# module.net
KiCad netlist of a schematic drawn in Altium Designer
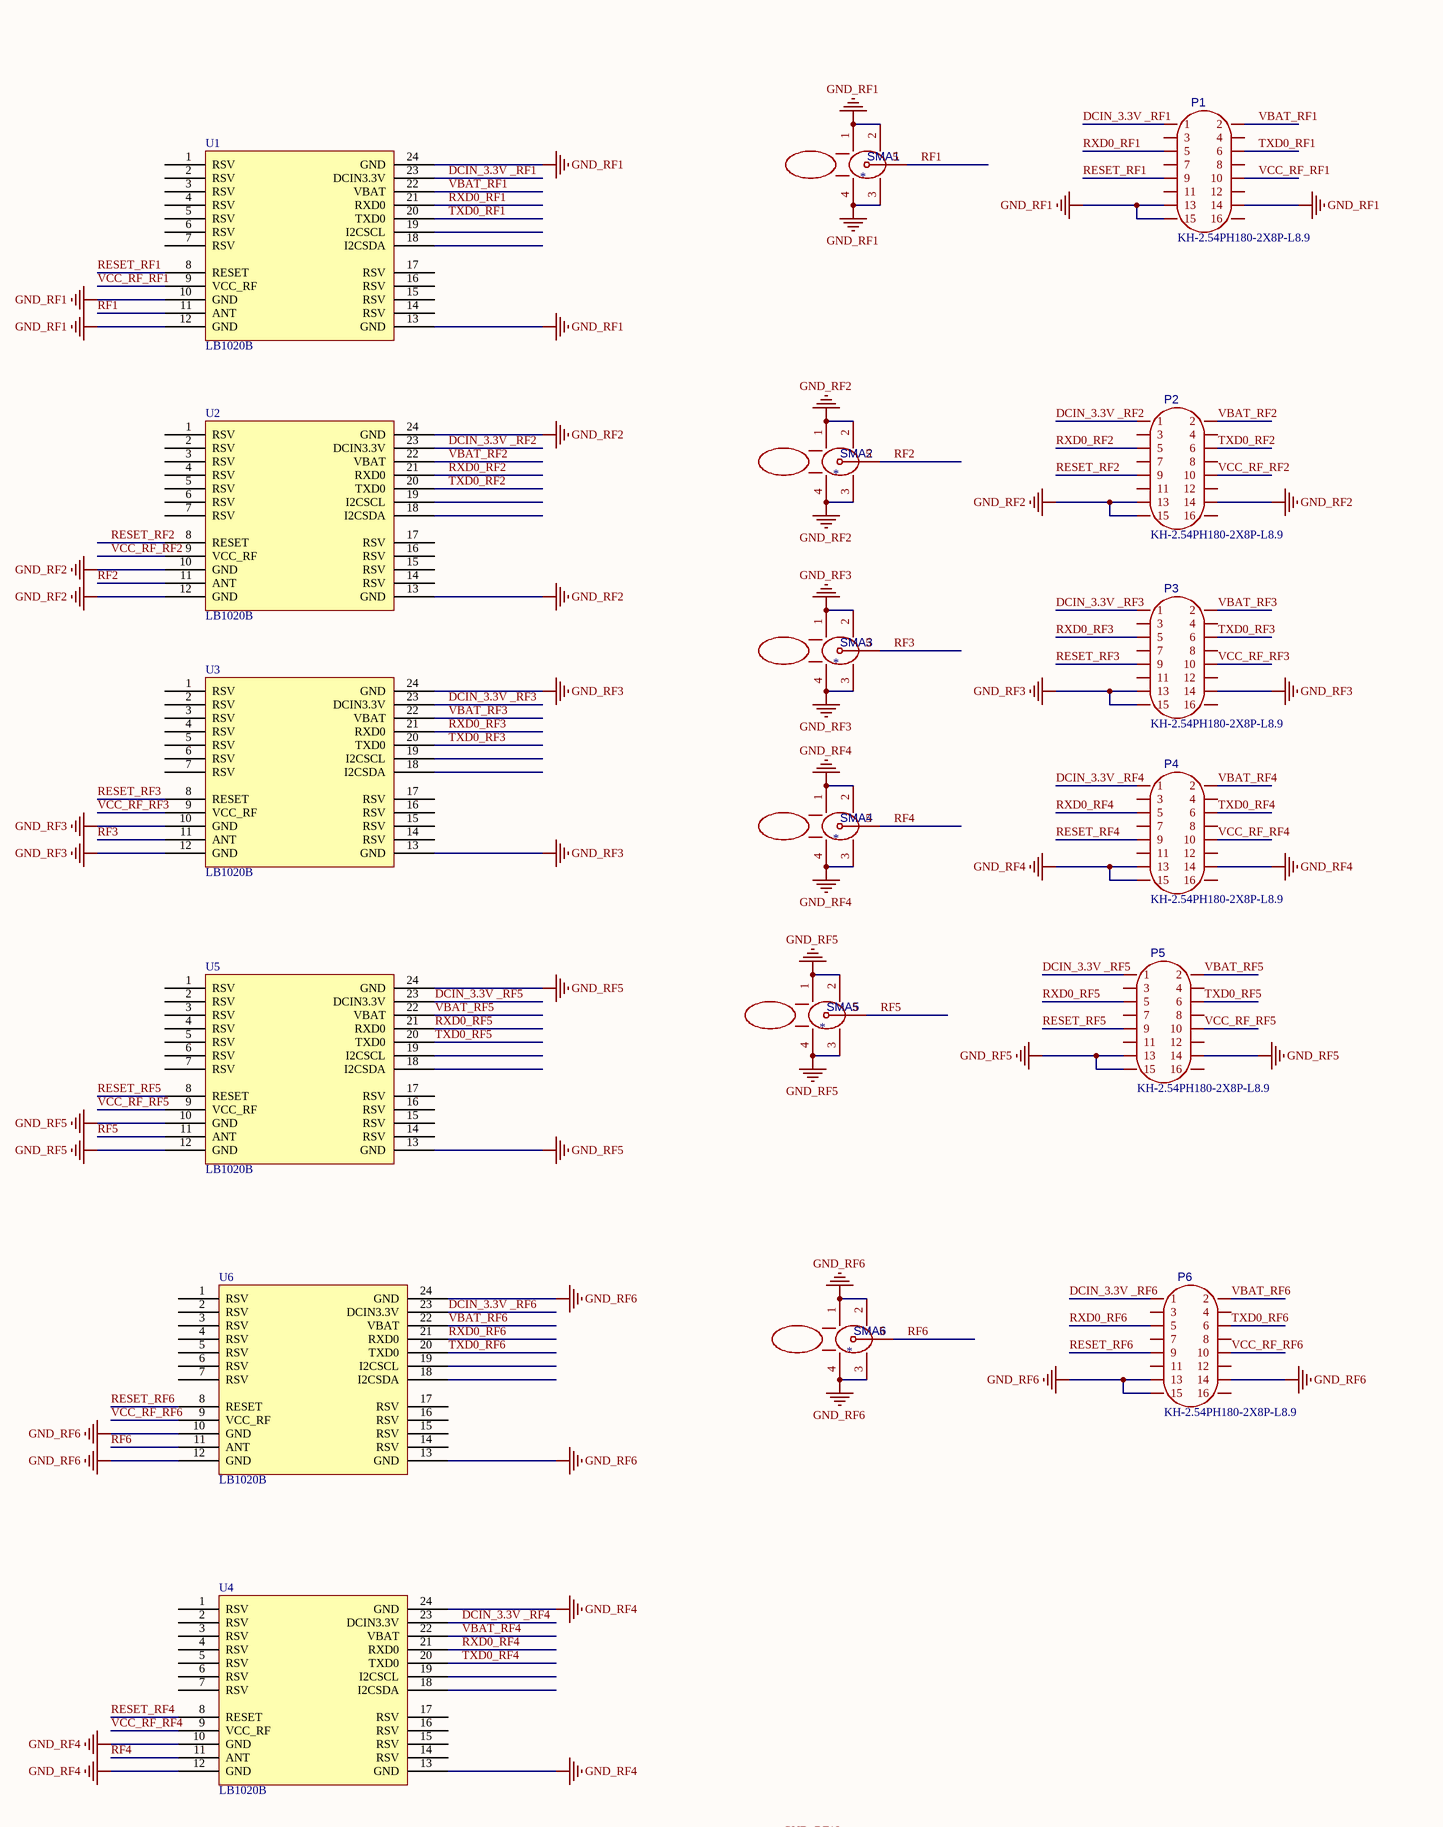
[diagram p0: module.SchDoc, top left]
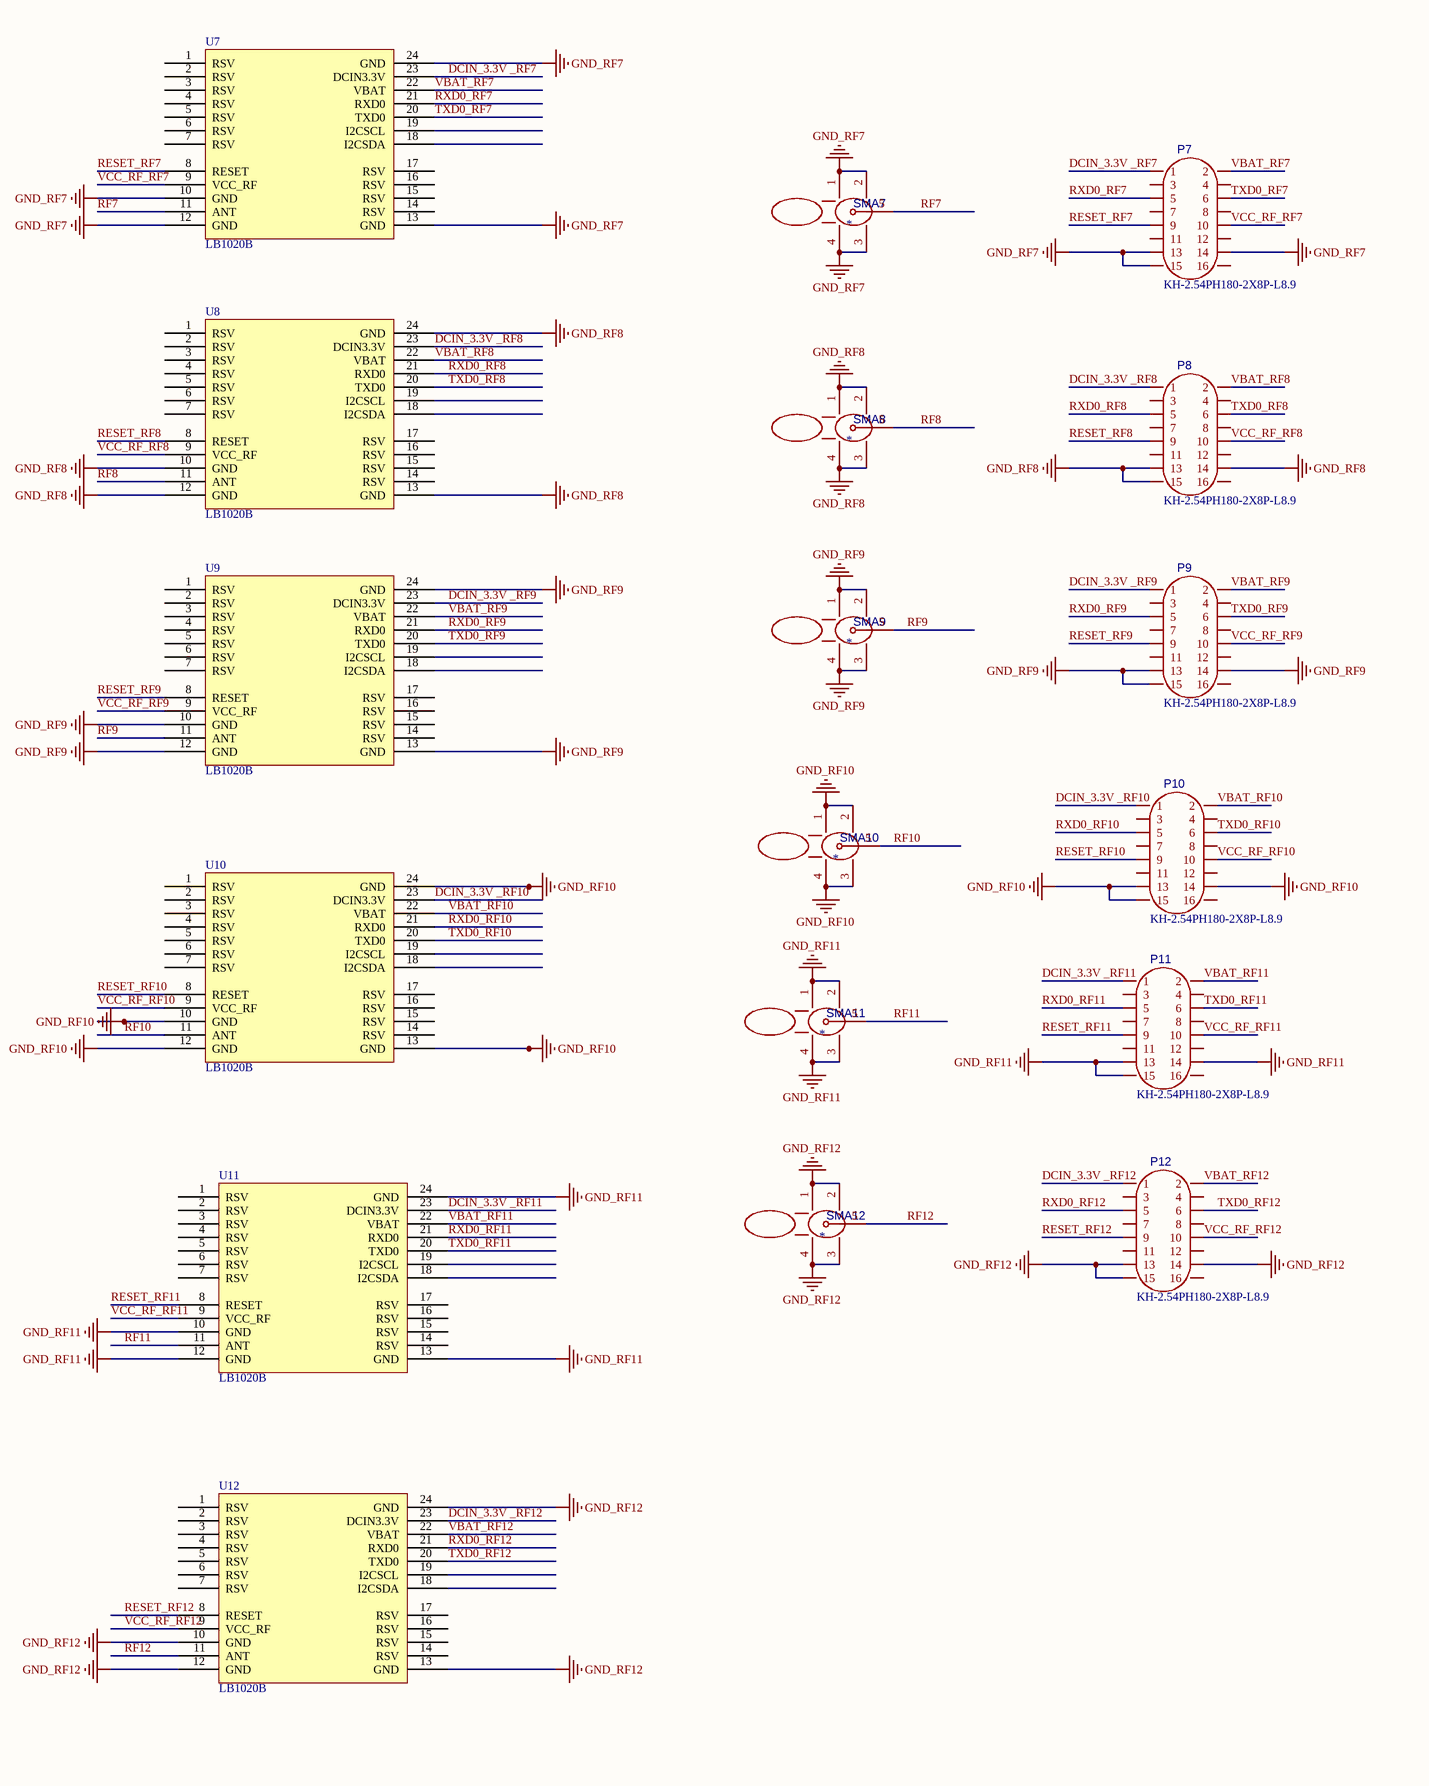
[diagram p1: module.SchDoc, top right]
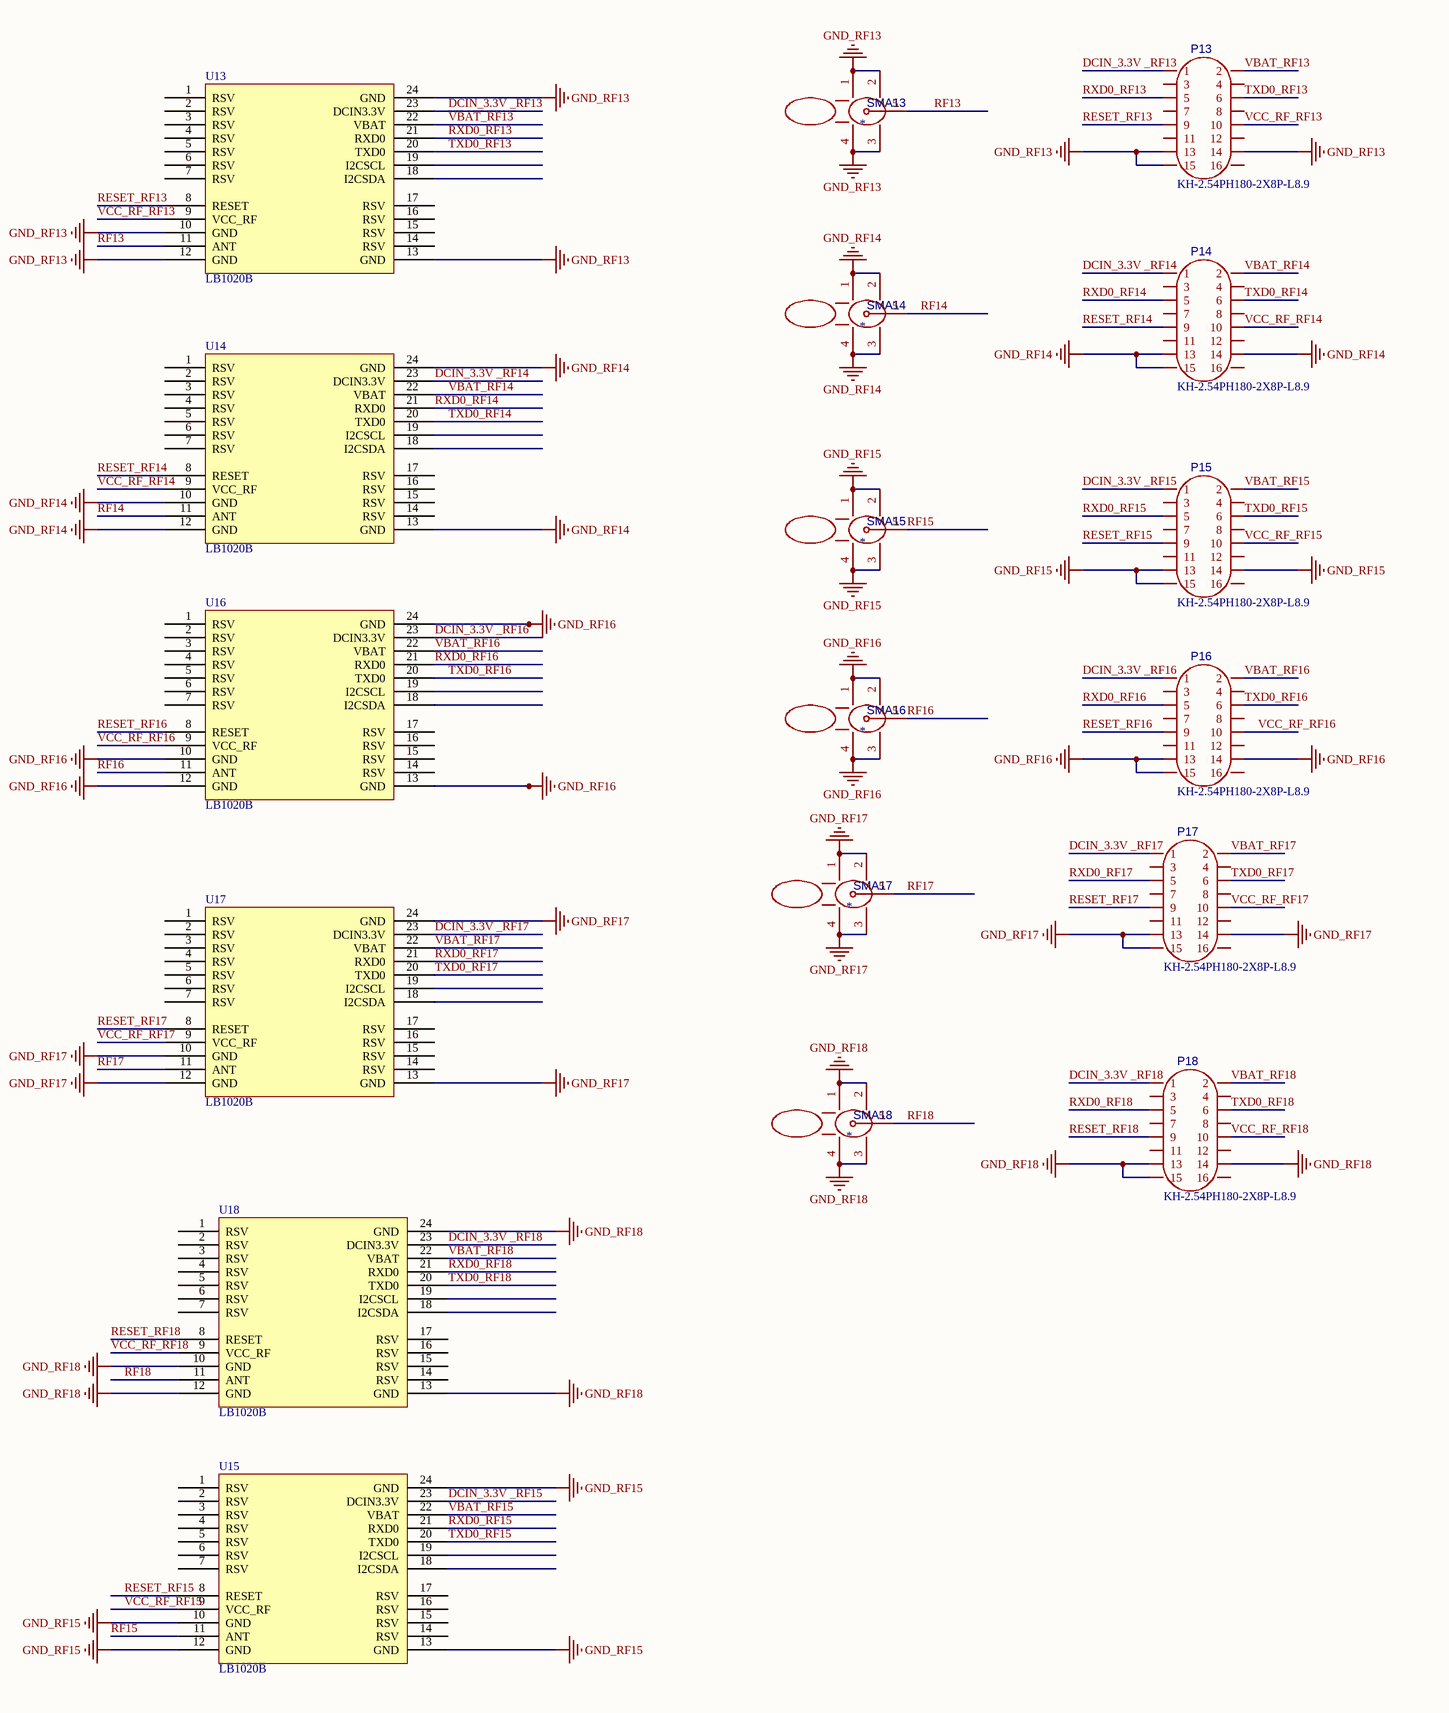
[diagram p2: module.SchDoc, bottom left]
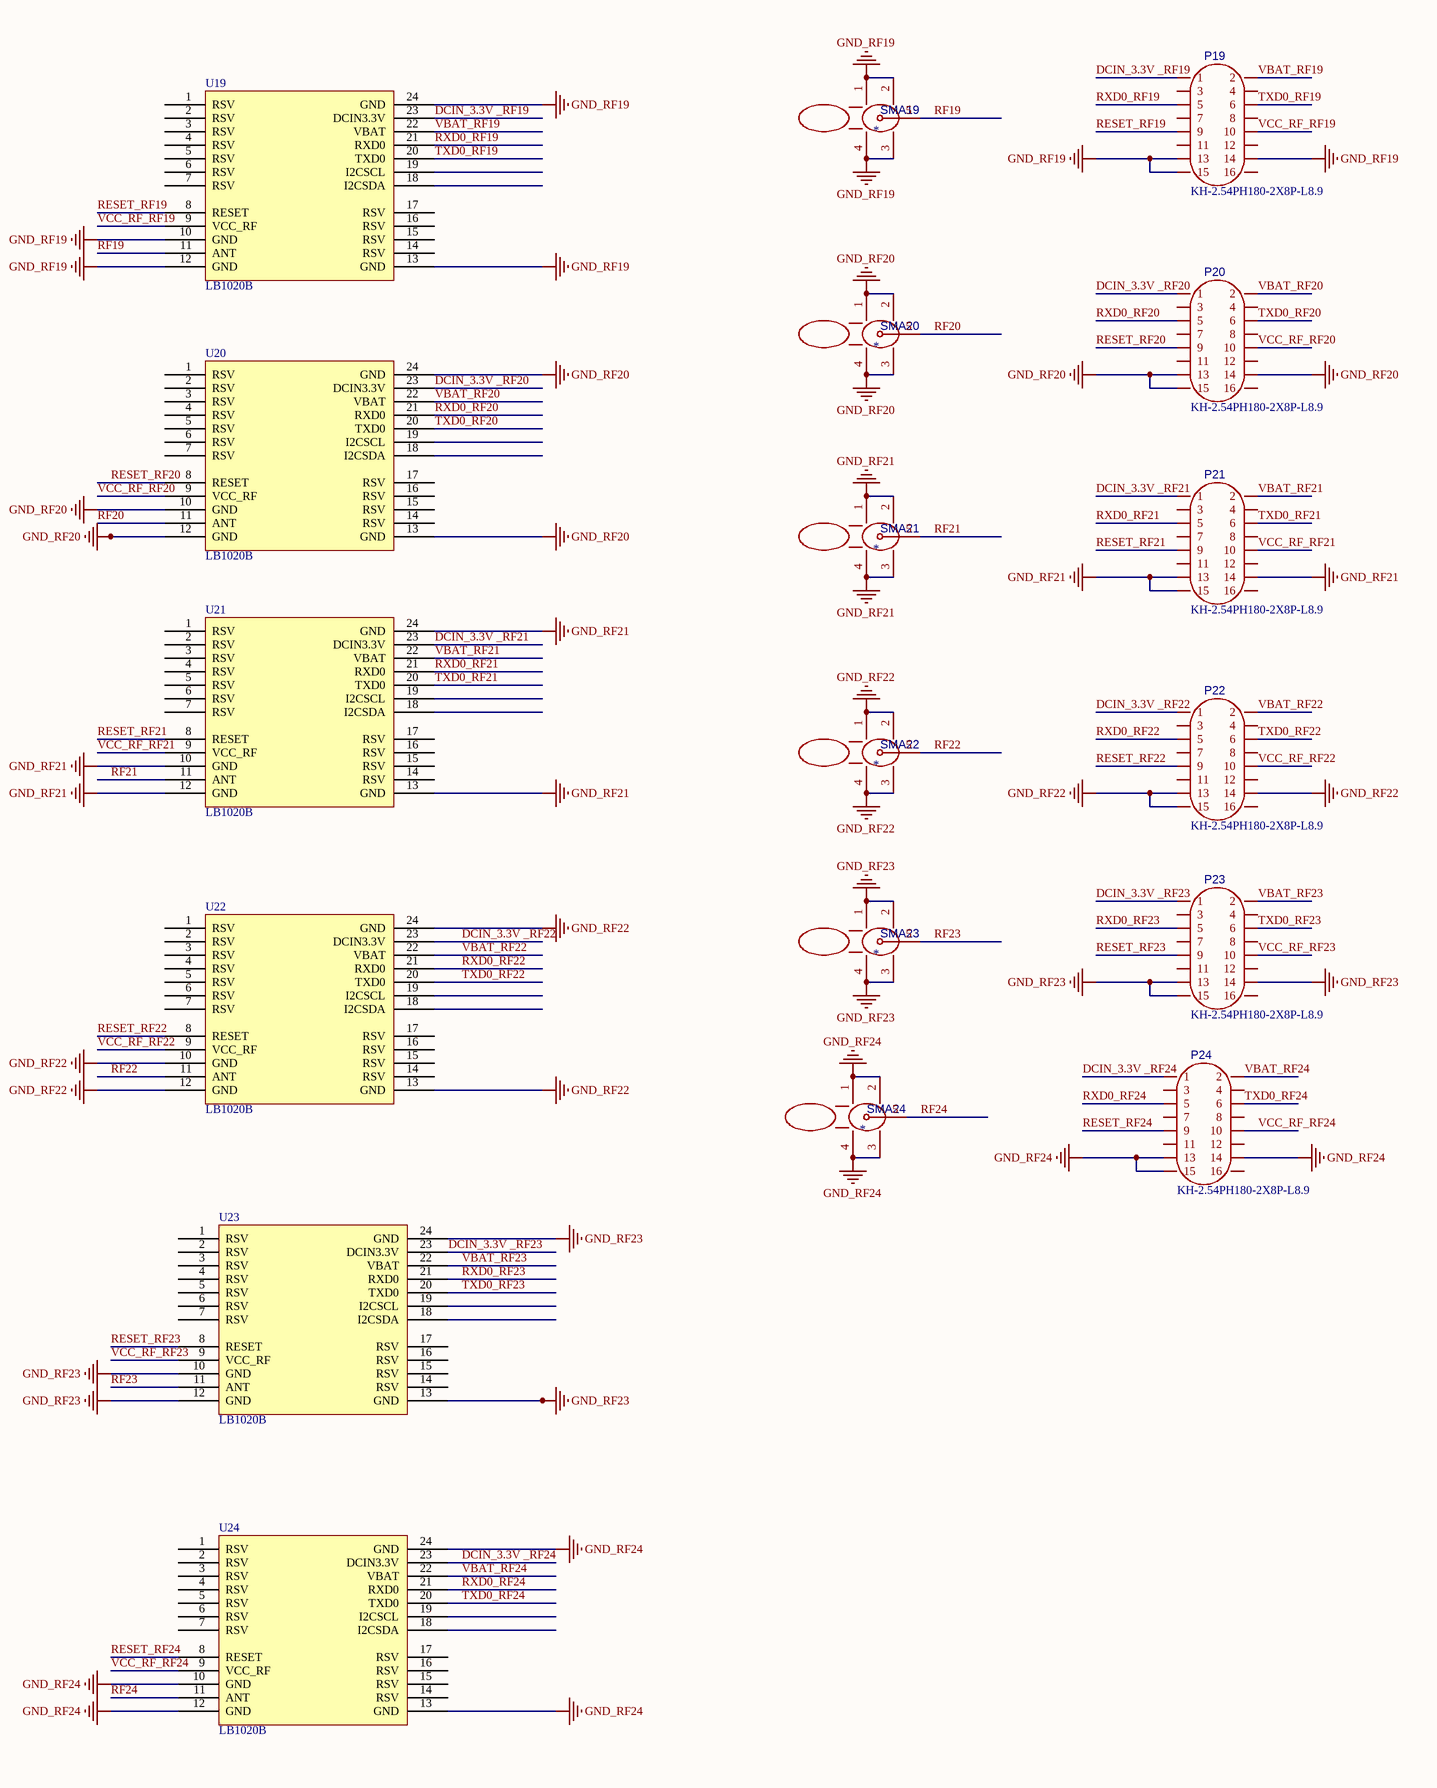
[diagram p3: module.SchDoc, bottom right]

(export (version "E")
  (design (tool "Eeschema 10.0.6"))
  (components
    (comp (ref "P1")
      (value "KH-2.54PH180-2X8P-L8.9")
      (footprint "IDC-TH_16P-P2.54_C3406:IDC-TH_16P-P2.54_C3406")
      (libsource (lib "altium-import") (part "root_0_HDR-IDC-2.54-2X8P_"))
    )
    (comp (ref "P2")
      (value "KH-2.54PH180-2X8P-L8.9")
      (footprint "IDC-TH_16P-P2.54_C3406:IDC-TH_16P-P2.54_C3406")
      (libsource (lib "altium-import") (part "root_0_HDR-IDC-2.54-2X8P_"))
    )
    (comp (ref "P3")
      (value "KH-2.54PH180-2X8P-L8.9")
      (footprint "IDC-TH_16P-P2.54_C3406:IDC-TH_16P-P2.54_C3406")
      (libsource (lib "altium-import") (part "root_0_HDR-IDC-2.54-2X8P_"))
    )
    (comp (ref "P4")
      (value "KH-2.54PH180-2X8P-L8.9")
      (footprint "IDC-TH_16P-P2.54_C3406:IDC-TH_16P-P2.54_C3406")
      (libsource (lib "altium-import") (part "root_0_HDR-IDC-2.54-2X8P_"))
    )
    (comp (ref "P5")
      (value "KH-2.54PH180-2X8P-L8.9")
      (footprint "IDC-TH_16P-P2.54_C3406:IDC-TH_16P-P2.54_C3406")
      (libsource (lib "altium-import") (part "root_0_HDR-IDC-2.54-2X8P_"))
    )
    (comp (ref "P6")
      (value "KH-2.54PH180-2X8P-L8.9")
      (footprint "IDC-TH_16P-P2.54_C3406:IDC-TH_16P-P2.54_C3406")
      (libsource (lib "altium-import") (part "root_0_HDR-IDC-2.54-2X8P_"))
    )
    (comp (ref "P7")
      (value "KH-2.54PH180-2X8P-L8.9")
      (footprint "IDC-TH_16P-P2.54_C3406:IDC-TH_16P-P2.54_C3406")
      (libsource (lib "altium-import") (part "root_0_HDR-IDC-2.54-2X8P_"))
    )
    (comp (ref "P8")
      (value "KH-2.54PH180-2X8P-L8.9")
      (footprint "IDC-TH_16P-P2.54_C3406:IDC-TH_16P-P2.54_C3406")
      (libsource (lib "altium-import") (part "root_0_HDR-IDC-2.54-2X8P_"))
    )
    (comp (ref "P9")
      (value "KH-2.54PH180-2X8P-L8.9")
      (footprint "IDC-TH_16P-P2.54_C3406:IDC-TH_16P-P2.54_C3406")
      (libsource (lib "altium-import") (part "root_0_HDR-IDC-2.54-2X8P_"))
    )
    (comp (ref "P10")
      (value "KH-2.54PH180-2X8P-L8.9")
      (footprint "IDC-TH_16P-P2.54_C3406:IDC-TH_16P-P2.54_C3406")
      (libsource (lib "altium-import") (part "root_0_HDR-IDC-2.54-2X8P_"))
    )
    (comp (ref "P11")
      (value "KH-2.54PH180-2X8P-L8.9")
      (footprint "IDC-TH_16P-P2.54_C3406:IDC-TH_16P-P2.54_C3406")
      (libsource (lib "altium-import") (part "root_0_HDR-IDC-2.54-2X8P_"))
    )
    (comp (ref "P12")
      (value "KH-2.54PH180-2X8P-L8.9")
      (footprint "IDC-TH_16P-P2.54_C3406:IDC-TH_16P-P2.54_C3406")
      (libsource (lib "altium-import") (part "root_0_HDR-IDC-2.54-2X8P_"))
    )
    (comp (ref "P13")
      (value "KH-2.54PH180-2X8P-L8.9")
      (footprint "IDC-TH_16P-P2.54_C3406:IDC-TH_16P-P2.54_C3406")
      (libsource (lib "altium-import") (part "root_0_HDR-IDC-2.54-2X8P_"))
    )
    (comp (ref "P14")
      (value "KH-2.54PH180-2X8P-L8.9")
      (footprint "IDC-TH_16P-P2.54_C3406:IDC-TH_16P-P2.54_C3406")
      (libsource (lib "altium-import") (part "root_0_HDR-IDC-2.54-2X8P_"))
    )
    (comp (ref "P15")
      (value "KH-2.54PH180-2X8P-L8.9")
      (footprint "IDC-TH_16P-P2.54_C3406:IDC-TH_16P-P2.54_C3406")
      (libsource (lib "altium-import") (part "root_0_HDR-IDC-2.54-2X8P_"))
    )
    (comp (ref "P16")
      (value "KH-2.54PH180-2X8P-L8.9")
      (footprint "IDC-TH_16P-P2.54_C3406:IDC-TH_16P-P2.54_C3406")
      (libsource (lib "altium-import") (part "root_0_HDR-IDC-2.54-2X8P_"))
    )
    (comp (ref "P17")
      (value "KH-2.54PH180-2X8P-L8.9")
      (footprint "IDC-TH_16P-P2.54_C3406:IDC-TH_16P-P2.54_C3406")
      (libsource (lib "altium-import") (part "root_0_HDR-IDC-2.54-2X8P_"))
    )
    (comp (ref "P18")
      (value "KH-2.54PH180-2X8P-L8.9")
      (footprint "IDC-TH_16P-P2.54_C3406:IDC-TH_16P-P2.54_C3406")
      (libsource (lib "altium-import") (part "root_0_HDR-IDC-2.54-2X8P_"))
    )
    (comp (ref "P19")
      (value "KH-2.54PH180-2X8P-L8.9")
      (footprint "IDC-TH_16P-P2.54_C3406:IDC-TH_16P-P2.54_C3406")
      (libsource (lib "altium-import") (part "root_0_HDR-IDC-2.54-2X8P_"))
    )
    (comp (ref "P20")
      (value "KH-2.54PH180-2X8P-L8.9")
      (footprint "IDC-TH_16P-P2.54_C3406:IDC-TH_16P-P2.54_C3406")
      (libsource (lib "altium-import") (part "root_0_HDR-IDC-2.54-2X8P_"))
    )
    (comp (ref "P21")
      (value "KH-2.54PH180-2X8P-L8.9")
      (footprint "IDC-TH_16P-P2.54_C3406:IDC-TH_16P-P2.54_C3406")
      (libsource (lib "altium-import") (part "root_0_HDR-IDC-2.54-2X8P_"))
    )
    (comp (ref "P22")
      (value "KH-2.54PH180-2X8P-L8.9")
      (footprint "IDC-TH_16P-P2.54_C3406:IDC-TH_16P-P2.54_C3406")
      (libsource (lib "altium-import") (part "root_0_HDR-IDC-2.54-2X8P_"))
    )
    (comp (ref "P23")
      (value "KH-2.54PH180-2X8P-L8.9")
      (footprint "IDC-TH_16P-P2.54_C3406:IDC-TH_16P-P2.54_C3406")
      (libsource (lib "altium-import") (part "root_0_HDR-IDC-2.54-2X8P_"))
    )
    (comp (ref "P24")
      (value "KH-2.54PH180-2X8P-L8.9")
      (footprint "IDC-TH_16P-P2.54_C3406:IDC-TH_16P-P2.54_C3406")
      (libsource (lib "altium-import") (part "root_0_HDR-IDC-2.54-2X8P_"))
    )
    (comp (ref "SMA1")
      (value "*")
      (footprint "SMA-TH_HL-SMA-KHD4:SMA-TH_HL-SMA-KHD4")
      (libsource (lib "altium-import") (part "root_0_HL-SMA-KHD4_"))
    )
    (comp (ref "SMA2")
      (value "*")
      (footprint "SMA-TH_HL-SMA-KHD4:SMA-TH_HL-SMA-KHD4")
      (libsource (lib "altium-import") (part "root_0_HL-SMA-KHD4_"))
    )
    (comp (ref "SMA3")
      (value "*")
      (footprint "SMA-TH_HL-SMA-KHD4:SMA-TH_HL-SMA-KHD4")
      (libsource (lib "altium-import") (part "root_0_HL-SMA-KHD4_"))
    )
    (comp (ref "SMA4")
      (value "*")
      (footprint "SMA-TH_HL-SMA-KHD4:SMA-TH_HL-SMA-KHD4")
      (libsource (lib "altium-import") (part "root_0_HL-SMA-KHD4_"))
    )
    (comp (ref "SMA5")
      (value "*")
      (footprint "SMA-TH_HL-SMA-KHD4:SMA-TH_HL-SMA-KHD4")
      (libsource (lib "altium-import") (part "root_0_HL-SMA-KHD4_"))
    )
    (comp (ref "SMA6")
      (value "*")
      (footprint "SMA-TH_HL-SMA-KHD4:SMA-TH_HL-SMA-KHD4")
      (libsource (lib "altium-import") (part "root_0_HL-SMA-KHD4_"))
    )
    (comp (ref "SMA7")
      (value "*")
      (footprint "SMA-TH_HL-SMA-KHD4:SMA-TH_HL-SMA-KHD4")
      (libsource (lib "altium-import") (part "root_0_HL-SMA-KHD4_"))
    )
    (comp (ref "SMA8")
      (value "*")
      (footprint "SMA-TH_HL-SMA-KHD4:SMA-TH_HL-SMA-KHD4")
      (libsource (lib "altium-import") (part "root_0_HL-SMA-KHD4_"))
    )
    (comp (ref "SMA9")
      (value "*")
      (footprint "SMA-TH_HL-SMA-KHD4:SMA-TH_HL-SMA-KHD4")
      (libsource (lib "altium-import") (part "root_0_HL-SMA-KHD4_"))
    )
    (comp (ref "SMA10")
      (value "*")
      (footprint "SMA-TH_HL-SMA-KHD4:SMA-TH_HL-SMA-KHD4")
      (libsource (lib "altium-import") (part "root_0_HL-SMA-KHD4_"))
    )
    (comp (ref "SMA11")
      (value "*")
      (footprint "SMA-TH_HL-SMA-KHD4:SMA-TH_HL-SMA-KHD4")
      (libsource (lib "altium-import") (part "root_0_HL-SMA-KHD4_"))
    )
    (comp (ref "SMA12")
      (value "*")
      (footprint "SMA-TH_HL-SMA-KHD4:SMA-TH_HL-SMA-KHD4")
      (libsource (lib "altium-import") (part "root_0_HL-SMA-KHD4_"))
    )
    (comp (ref "SMA13")
      (value "*")
      (footprint "SMA-TH_HL-SMA-KHD4:SMA-TH_HL-SMA-KHD4")
      (libsource (lib "altium-import") (part "root_0_HL-SMA-KHD4_"))
    )
    (comp (ref "SMA14")
      (value "*")
      (footprint "SMA-TH_HL-SMA-KHD4:SMA-TH_HL-SMA-KHD4")
      (libsource (lib "altium-import") (part "root_0_HL-SMA-KHD4_"))
    )
    (comp (ref "SMA15")
      (value "*")
      (footprint "SMA-TH_HL-SMA-KHD4:SMA-TH_HL-SMA-KHD4")
      (libsource (lib "altium-import") (part "root_0_HL-SMA-KHD4_"))
    )
    (comp (ref "SMA16")
      (value "*")
      (footprint "SMA-TH_HL-SMA-KHD4:SMA-TH_HL-SMA-KHD4")
      (libsource (lib "altium-import") (part "root_0_HL-SMA-KHD4_"))
    )
    (comp (ref "SMA17")
      (value "*")
      (footprint "SMA-TH_HL-SMA-KHD4:SMA-TH_HL-SMA-KHD4")
      (libsource (lib "altium-import") (part "root_0_HL-SMA-KHD4_"))
    )
    (comp (ref "SMA18")
      (value "*")
      (footprint "SMA-TH_HL-SMA-KHD4:SMA-TH_HL-SMA-KHD4")
      (libsource (lib "altium-import") (part "root_0_HL-SMA-KHD4_"))
    )
    (comp (ref "SMA19")
      (value "*")
      (footprint "SMA-TH_HL-SMA-KHD4:SMA-TH_HL-SMA-KHD4")
      (libsource (lib "altium-import") (part "root_0_HL-SMA-KHD4_"))
    )
    (comp (ref "SMA20")
      (value "*")
      (footprint "SMA-TH_HL-SMA-KHD4:SMA-TH_HL-SMA-KHD4")
      (libsource (lib "altium-import") (part "root_0_HL-SMA-KHD4_"))
    )
    (comp (ref "SMA21")
      (value "*")
      (footprint "SMA-TH_HL-SMA-KHD4:SMA-TH_HL-SMA-KHD4")
      (libsource (lib "altium-import") (part "root_0_HL-SMA-KHD4_"))
    )
    (comp (ref "SMA22")
      (value "*")
      (footprint "SMA-TH_HL-SMA-KHD4:SMA-TH_HL-SMA-KHD4")
      (libsource (lib "altium-import") (part "root_0_HL-SMA-KHD4_"))
    )
    (comp (ref "SMA23")
      (value "*")
      (footprint "SMA-TH_HL-SMA-KHD4:SMA-TH_HL-SMA-KHD4")
      (libsource (lib "altium-import") (part "root_0_HL-SMA-KHD4_"))
    )
    (comp (ref "SMA24")
      (value "*")
      (footprint "SMA-TH_HL-SMA-KHD4:SMA-TH_HL-SMA-KHD4")
      (libsource (lib "altium-import") (part "root_0_HL-SMA-KHD4_"))
    )
    (comp (ref "U1")
      (value "LB1020B")
      (footprint "LB1020B")
      (libsource (lib "Schlib_20110825") (part "LB1020B"))
    )
    (comp (ref "U2")
      (value "LB1020B")
      (footprint "LB1020B")
      (libsource (lib "Schlib_20110825") (part "LB1020B"))
    )
    (comp (ref "U3")
      (value "LB1020B")
      (footprint "LB1020B")
      (libsource (lib "Schlib_20110825") (part "LB1020B"))
    )
    (comp (ref "U4")
      (value "LB1020B")
      (footprint "LB1020B")
      (libsource (lib "Schlib_20110825") (part "LB1020B"))
    )
    (comp (ref "U5")
      (value "LB1020B")
      (footprint "LB1020B")
      (libsource (lib "Schlib_20110825") (part "LB1020B"))
    )
    (comp (ref "U6")
      (value "LB1020B")
      (footprint "LB1020B")
      (libsource (lib "Schlib_20110825") (part "LB1020B"))
    )
    (comp (ref "U7")
      (value "LB1020B")
      (footprint "LB1020B")
      (libsource (lib "Schlib_20110825") (part "LB1020B"))
    )
    (comp (ref "U8")
      (value "LB1020B")
      (footprint "LB1020B")
      (libsource (lib "Schlib_20110825") (part "LB1020B"))
    )
    (comp (ref "U9")
      (value "LB1020B")
      (footprint "LB1020B")
      (libsource (lib "Schlib_20110825") (part "LB1020B"))
    )
    (comp (ref "U10")
      (value "LB1020B")
      (footprint "LB1020B")
      (libsource (lib "Schlib_20110825") (part "LB1020B"))
    )
    (comp (ref "U11")
      (value "LB1020B")
      (footprint "LB1020B")
      (libsource (lib "Schlib_20110825") (part "LB1020B"))
    )
    (comp (ref "U12")
      (value "LB1020B")
      (footprint "LB1020B")
      (libsource (lib "Schlib_20110825") (part "LB1020B"))
    )
    (comp (ref "U13")
      (value "LB1020B")
      (footprint "LB1020B")
      (libsource (lib "Schlib_20110825") (part "LB1020B"))
    )
    (comp (ref "U14")
      (value "LB1020B")
      (footprint "LB1020B")
      (libsource (lib "Schlib_20110825") (part "LB1020B"))
    )
    (comp (ref "U15")
      (value "LB1020B")
      (footprint "LB1020B")
      (libsource (lib "Schlib_20110825") (part "LB1020B"))
    )
    (comp (ref "U16")
      (value "LB1020B")
      (footprint "LB1020B")
      (libsource (lib "Schlib_20110825") (part "LB1020B"))
    )
    (comp (ref "U17")
      (value "LB1020B")
      (footprint "LB1020B")
      (libsource (lib "Schlib_20110825") (part "LB1020B"))
    )
    (comp (ref "U18")
      (value "LB1020B")
      (footprint "LB1020B")
      (libsource (lib "Schlib_20110825") (part "LB1020B"))
    )
    (comp (ref "U19")
      (value "LB1020B")
      (footprint "LB1020B")
      (libsource (lib "Schlib_20110825") (part "LB1020B"))
    )
    (comp (ref "U20")
      (value "LB1020B")
      (footprint "LB1020B")
      (libsource (lib "Schlib_20110825") (part "LB1020B"))
    )
    (comp (ref "U21")
      (value "LB1020B")
      (footprint "LB1020B")
      (libsource (lib "Schlib_20110825") (part "LB1020B"))
    )
    (comp (ref "U22")
      (value "LB1020B")
      (footprint "LB1020B")
      (libsource (lib "Schlib_20110825") (part "LB1020B"))
    )
    (comp (ref "U23")
      (value "LB1020B")
      (footprint "LB1020B")
      (libsource (lib "Schlib_20110825") (part "LB1020B"))
    )
    (comp (ref "U24")
      (value "LB1020B")
      (footprint "LB1020B")
      (libsource (lib "Schlib_20110825") (part "LB1020B"))
    )
  )
  (nets
    (net (code "1") (name "/DCIN_3.3V _RF1") (class "Default")
      (node (ref "P1") (pin "1") (pinfunction "1_1") (pintype "passive"))
      (node (ref "U1") (pin "23") (pinfunction "DCIN3.3V_23") (pintype "passive"))
    )
    (net (code "2") (name "/DCIN_3.3V _RF2") (class "Default")
      (node (ref "P2") (pin "1") (pinfunction "1_1") (pintype "passive"))
      (node (ref "U2") (pin "23") (pinfunction "DCIN3.3V_23") (pintype "passive"))
    )
    (net (code "3") (name "/DCIN_3.3V _RF3") (class "Default")
      (node (ref "P3") (pin "1") (pinfunction "1_1") (pintype "passive"))
      (node (ref "U3") (pin "23") (pinfunction "DCIN3.3V_23") (pintype "passive"))
    )
    (net (code "4") (name "/DCIN_3.3V _RF4") (class "Default")
      (node (ref "P4") (pin "1") (pinfunction "1_1") (pintype "passive"))
      (node (ref "U4") (pin "23") (pinfunction "DCIN3.3V_23") (pintype "passive"))
    )
    (net (code "5") (name "/DCIN_3.3V _RF5") (class "Default")
      (node (ref "P5") (pin "1") (pinfunction "1_1") (pintype "passive"))
      (node (ref "U5") (pin "23") (pinfunction "DCIN3.3V_23") (pintype "passive"))
    )
    (net (code "6") (name "/DCIN_3.3V _RF6") (class "Default")
      (node (ref "P6") (pin "1") (pinfunction "1_1") (pintype "passive"))
      (node (ref "U6") (pin "23") (pinfunction "DCIN3.3V_23") (pintype "passive"))
    )
    (net (code "7") (name "/DCIN_3.3V _RF7") (class "Default")
      (node (ref "P7") (pin "1") (pinfunction "1_1") (pintype "passive"))
      (node (ref "U7") (pin "23") (pinfunction "DCIN3.3V_23") (pintype "passive"))
    )
    (net (code "8") (name "/DCIN_3.3V _RF8") (class "Default")
      (node (ref "P8") (pin "1") (pinfunction "1_1") (pintype "passive"))
      (node (ref "U8") (pin "23") (pinfunction "DCIN3.3V_23") (pintype "passive"))
    )
    (net (code "9") (name "/DCIN_3.3V _RF9") (class "Default")
      (node (ref "P9") (pin "1") (pinfunction "1_1") (pintype "passive"))
      (node (ref "U9") (pin "23") (pinfunction "DCIN3.3V_23") (pintype "passive"))
    )
    (net (code "10") (name "/DCIN_3.3V _RF10") (class "Default")
      (node (ref "P10") (pin "1") (pinfunction "1_1") (pintype "passive"))
      (node (ref "U10") (pin "23") (pinfunction "DCIN3.3V_23") (pintype "passive"))
    )
    (net (code "11") (name "/DCIN_3.3V _RF11") (class "Default")
      (node (ref "P11") (pin "1") (pinfunction "1_1") (pintype "passive"))
      (node (ref "U11") (pin "23") (pinfunction "DCIN3.3V_23") (pintype "passive"))
    )
    (net (code "12") (name "/DCIN_3.3V _RF12") (class "Default")
      (node (ref "P12") (pin "1") (pinfunction "1_1") (pintype "passive"))
      (node (ref "U12") (pin "23") (pinfunction "DCIN3.3V_23") (pintype "passive"))
    )
    (net (code "13") (name "/DCIN_3.3V _RF13") (class "Default")
      (node (ref "P13") (pin "1") (pinfunction "1_1") (pintype "passive"))
      (node (ref "U13") (pin "23") (pinfunction "DCIN3.3V_23") (pintype "passive"))
    )
    (net (code "14") (name "/DCIN_3.3V _RF14") (class "Default")
      (node (ref "P14") (pin "1") (pinfunction "1_1") (pintype "passive"))
      (node (ref "U14") (pin "23") (pinfunction "DCIN3.3V_23") (pintype "passive"))
    )
    (net (code "15") (name "/DCIN_3.3V _RF15") (class "Default")
      (node (ref "P15") (pin "1") (pinfunction "1_1") (pintype "passive"))
      (node (ref "U15") (pin "23") (pinfunction "DCIN3.3V_23") (pintype "passive"))
    )
    (net (code "16") (name "/DCIN_3.3V _RF16") (class "Default")
      (node (ref "P16") (pin "1") (pinfunction "1_1") (pintype "passive"))
      (node (ref "U16") (pin "23") (pinfunction "DCIN3.3V_23") (pintype "passive"))
    )
    (net (code "17") (name "/DCIN_3.3V _RF17") (class "Default")
      (node (ref "P17") (pin "1") (pinfunction "1_1") (pintype "passive"))
      (node (ref "U17") (pin "23") (pinfunction "DCIN3.3V_23") (pintype "passive"))
    )
    (net (code "18") (name "/DCIN_3.3V _RF18") (class "Default")
      (node (ref "P18") (pin "1") (pinfunction "1_1") (pintype "passive"))
      (node (ref "U18") (pin "23") (pinfunction "DCIN3.3V_23") (pintype "passive"))
    )
    (net (code "19") (name "/DCIN_3.3V _RF19") (class "Default")
      (node (ref "P19") (pin "1") (pinfunction "1_1") (pintype "passive"))
      (node (ref "U19") (pin "23") (pinfunction "DCIN3.3V_23") (pintype "passive"))
    )
    (net (code "20") (name "/DCIN_3.3V _RF20") (class "Default")
      (node (ref "P20") (pin "1") (pinfunction "1_1") (pintype "passive"))
      (node (ref "U20") (pin "23") (pinfunction "DCIN3.3V_23") (pintype "passive"))
    )
    (net (code "21") (name "/DCIN_3.3V _RF21") (class "Default")
      (node (ref "P21") (pin "1") (pinfunction "1_1") (pintype "passive"))
      (node (ref "U21") (pin "23") (pinfunction "DCIN3.3V_23") (pintype "passive"))
    )
    (net (code "22") (name "/DCIN_3.3V _RF22") (class "Default")
      (node (ref "P22") (pin "1") (pinfunction "1_1") (pintype "passive"))
      (node (ref "U22") (pin "23") (pinfunction "DCIN3.3V_23") (pintype "passive"))
    )
    (net (code "23") (name "/DCIN_3.3V _RF23") (class "Default")
      (node (ref "P23") (pin "1") (pinfunction "1_1") (pintype "passive"))
      (node (ref "U23") (pin "23") (pinfunction "DCIN3.3V_23") (pintype "passive"))
    )
    (net (code "24") (name "/DCIN_3.3V _RF24") (class "Default")
      (node (ref "P24") (pin "1") (pinfunction "1_1") (pintype "passive"))
      (node (ref "U24") (pin "23") (pinfunction "DCIN3.3V_23") (pintype "passive"))
    )
    (net (code "25") (name "/RESET_RF1") (class "Default")
      (node (ref "P1") (pin "9") (pinfunction "9_9") (pintype "passive"))
      (node (ref "U1") (pin "8") (pinfunction "RESET_8") (pintype "passive"))
    )
    (net (code "26") (name "/RESET_RF2") (class "Default")
      (node (ref "P2") (pin "9") (pinfunction "9_9") (pintype "passive"))
      (node (ref "U2") (pin "8") (pinfunction "RESET_8") (pintype "passive"))
    )
    (net (code "27") (name "/RESET_RF3") (class "Default")
      (node (ref "P3") (pin "9") (pinfunction "9_9") (pintype "passive"))
      (node (ref "U3") (pin "8") (pinfunction "RESET_8") (pintype "passive"))
    )
    (net (code "28") (name "/RESET_RF4") (class "Default")
      (node (ref "P4") (pin "9") (pinfunction "9_9") (pintype "passive"))
      (node (ref "U4") (pin "8") (pinfunction "RESET_8") (pintype "passive"))
    )
    (net (code "29") (name "/RESET_RF5") (class "Default")
      (node (ref "P5") (pin "9") (pinfunction "9_9") (pintype "passive"))
      (node (ref "U5") (pin "8") (pinfunction "RESET_8") (pintype "passive"))
    )
    (net (code "30") (name "/RESET_RF6") (class "Default")
      (node (ref "P6") (pin "9") (pinfunction "9_9") (pintype "passive"))
      (node (ref "U6") (pin "8") (pinfunction "RESET_8") (pintype "passive"))
    )
    (net (code "31") (name "/RESET_RF7") (class "Default")
      (node (ref "P7") (pin "9") (pinfunction "9_9") (pintype "passive"))
      (node (ref "U7") (pin "8") (pinfunction "RESET_8") (pintype "passive"))
    )
    (net (code "32") (name "/RESET_RF8") (class "Default")
      (node (ref "P8") (pin "9") (pinfunction "9_9") (pintype "passive"))
      (node (ref "U8") (pin "8") (pinfunction "RESET_8") (pintype "passive"))
    )
    (net (code "33") (name "/RESET_RF9") (class "Default")
      (node (ref "P9") (pin "9") (pinfunction "9_9") (pintype "passive"))
      (node (ref "U9") (pin "8") (pinfunction "RESET_8") (pintype "passive"))
    )
    (net (code "34") (name "/RESET_RF10") (class "Default")
      (node (ref "P10") (pin "9") (pinfunction "9_9") (pintype "passive"))
      (node (ref "U10") (pin "8") (pinfunction "RESET_8") (pintype "passive"))
    )
    (net (code "35") (name "/RESET_RF11") (class "Default")
      (node (ref "P11") (pin "9") (pinfunction "9_9") (pintype "passive"))
      (node (ref "U11") (pin "8") (pinfunction "RESET_8") (pintype "passive"))
    )
    (net (code "36") (name "/RESET_RF12") (class "Default")
      (node (ref "P12") (pin "9") (pinfunction "9_9") (pintype "passive"))
      (node (ref "U12") (pin "8") (pinfunction "RESET_8") (pintype "passive"))
    )
    (net (code "37") (name "/RESET_RF13") (class "Default")
      (node (ref "P13") (pin "9") (pinfunction "9_9") (pintype "passive"))
      (node (ref "U13") (pin "8") (pinfunction "RESET_8") (pintype "passive"))
    )
    (net (code "38") (name "/RESET_RF14") (class "Default")
      (node (ref "P14") (pin "9") (pinfunction "9_9") (pintype "passive"))
      (node (ref "U14") (pin "8") (pinfunction "RESET_8") (pintype "passive"))
    )
    (net (code "39") (name "/RESET_RF15") (class "Default")
      (node (ref "P15") (pin "9") (pinfunction "9_9") (pintype "passive"))
      (node (ref "U15") (pin "8") (pinfunction "RESET_8") (pintype "passive"))
    )
    (net (code "40") (name "/RESET_RF16") (class "Default")
      (node (ref "P16") (pin "9") (pinfunction "9_9") (pintype "passive"))
      (node (ref "U16") (pin "8") (pinfunction "RESET_8") (pintype "passive"))
    )
    (net (code "41") (name "/RESET_RF17") (class "Default")
      (node (ref "P17") (pin "9") (pinfunction "9_9") (pintype "passive"))
      (node (ref "U17") (pin "8") (pinfunction "RESET_8") (pintype "passive"))
    )
    (net (code "42") (name "/RESET_RF18") (class "Default")
      (node (ref "P18") (pin "9") (pinfunction "9_9") (pintype "passive"))
      (node (ref "U18") (pin "8") (pinfunction "RESET_8") (pintype "passive"))
    )
    (net (code "43") (name "/RESET_RF19") (class "Default")
      (node (ref "P19") (pin "9") (pinfunction "9_9") (pintype "passive"))
      (node (ref "U19") (pin "8") (pinfunction "RESET_8") (pintype "passive"))
    )
    (net (code "44") (name "/RESET_RF20") (class "Default")
      (node (ref "P20") (pin "9") (pinfunction "9_9") (pintype "passive"))
      (node (ref "U20") (pin "8") (pinfunction "RESET_8") (pintype "passive"))
    )
    (net (code "45") (name "/RESET_RF21") (class "Default")
      (node (ref "P21") (pin "9") (pinfunction "9_9") (pintype "passive"))
      (node (ref "U21") (pin "8") (pinfunction "RESET_8") (pintype "passive"))
    )
    (net (code "46") (name "/RESET_RF22") (class "Default")
      (node (ref "P22") (pin "9") (pinfunction "9_9") (pintype "passive"))
      (node (ref "U22") (pin "8") (pinfunction "RESET_8") (pintype "passive"))
    )
    (net (code "47") (name "/RESET_RF23") (class "Default")
      (node (ref "P23") (pin "9") (pinfunction "9_9") (pintype "passive"))
      (node (ref "U23") (pin "8") (pinfunction "RESET_8") (pintype "passive"))
    )
    (net (code "48") (name "/RESET_RF24") (class "Default")
      (node (ref "P24") (pin "9") (pinfunction "9_9") (pintype "passive"))
      (node (ref "U24") (pin "8") (pinfunction "RESET_8") (pintype "passive"))
    )
    (net (code "49") (name "/RF1") (class "Default")
      (node (ref "SMA1") (pin "5") (pinfunction "5_5") (pintype "passive"))
      (node (ref "U1") (pin "11") (pinfunction "ANT_11") (pintype "passive"))
    )
    (net (code "50") (name "/RF2") (class "Default")
      (node (ref "SMA2") (pin "5") (pinfunction "5_5") (pintype "passive"))
      (node (ref "U2") (pin "11") (pinfunction "ANT_11") (pintype "passive"))
    )
    (net (code "51") (name "/RF3") (class "Default")
      (node (ref "SMA3") (pin "5") (pinfunction "5_5") (pintype "passive"))
      (node (ref "U3") (pin "11") (pinfunction "ANT_11") (pintype "passive"))
    )
    (net (code "52") (name "/RF4") (class "Default")
      (node (ref "SMA4") (pin "5") (pinfunction "5_5") (pintype "passive"))
      (node (ref "U4") (pin "11") (pinfunction "ANT_11") (pintype "passive"))
    )
    (net (code "53") (name "/RF5") (class "Default")
      (node (ref "SMA5") (pin "5") (pinfunction "5_5") (pintype "passive"))
      (node (ref "U5") (pin "11") (pinfunction "ANT_11") (pintype "passive"))
    )
    (net (code "54") (name "/RF6") (class "Default")
      (node (ref "SMA6") (pin "5") (pinfunction "5_5") (pintype "passive"))
      (node (ref "U6") (pin "11") (pinfunction "ANT_11") (pintype "passive"))
    )
    (net (code "55") (name "/RF7") (class "Default")
      (node (ref "SMA7") (pin "5") (pinfunction "5_5") (pintype "passive"))
      (node (ref "U7") (pin "11") (pinfunction "ANT_11") (pintype "passive"))
    )
    (net (code "56") (name "/RF8") (class "Default")
      (node (ref "SMA8") (pin "5") (pinfunction "5_5") (pintype "passive"))
      (node (ref "U8") (pin "11") (pinfunction "ANT_11") (pintype "passive"))
    )
    (net (code "57") (name "/RF9") (class "Default")
      (node (ref "SMA9") (pin "5") (pinfunction "5_5") (pintype "passive"))
      (node (ref "U9") (pin "11") (pinfunction "ANT_11") (pintype "passive"))
    )
    (net (code "58") (name "/RF10") (class "Default")
      (node (ref "SMA10") (pin "5") (pinfunction "5_5") (pintype "passive"))
      (node (ref "U10") (pin "11") (pinfunction "ANT_11") (pintype "passive"))
    )
    (net (code "59") (name "/RF11") (class "Default")
      (node (ref "SMA11") (pin "5") (pinfunction "5_5") (pintype "passive"))
      (node (ref "U11") (pin "11") (pinfunction "ANT_11") (pintype "passive"))
    )
    (net (code "60") (name "/RF12") (class "Default")
      (node (ref "SMA12") (pin "5") (pinfunction "5_5") (pintype "passive"))
      (node (ref "U12") (pin "11") (pinfunction "ANT_11") (pintype "passive"))
    )
    (net (code "61") (name "/RF13") (class "Default")
      (node (ref "SMA13") (pin "5") (pinfunction "5_5") (pintype "passive"))
      (node (ref "U13") (pin "11") (pinfunction "ANT_11") (pintype "passive"))
    )
    (net (code "62") (name "/RF14") (class "Default")
      (node (ref "SMA14") (pin "5") (pinfunction "5_5") (pintype "passive"))
      (node (ref "U14") (pin "11") (pinfunction "ANT_11") (pintype "passive"))
    )
    (net (code "63") (name "/RF15") (class "Default")
      (node (ref "SMA15") (pin "5") (pinfunction "5_5") (pintype "passive"))
      (node (ref "U15") (pin "11") (pinfunction "ANT_11") (pintype "passive"))
    )
    (net (code "64") (name "/RF16") (class "Default")
      (node (ref "SMA16") (pin "5") (pinfunction "5_5") (pintype "passive"))
      (node (ref "U16") (pin "11") (pinfunction "ANT_11") (pintype "passive"))
    )
    (net (code "65") (name "/RF17") (class "Default")
      (node (ref "SMA17") (pin "5") (pinfunction "5_5") (pintype "passive"))
      (node (ref "U17") (pin "11") (pinfunction "ANT_11") (pintype "passive"))
    )
    (net (code "66") (name "/RF18") (class "Default")
      (node (ref "SMA18") (pin "5") (pinfunction "5_5") (pintype "passive"))
      (node (ref "U18") (pin "11") (pinfunction "ANT_11") (pintype "passive"))
    )
    (net (code "67") (name "/RF19") (class "Default")
      (node (ref "SMA19") (pin "5") (pinfunction "5_5") (pintype "passive"))
      (node (ref "U19") (pin "11") (pinfunction "ANT_11") (pintype "passive"))
    )
    (net (code "68") (name "/RF20") (class "Default")
      (node (ref "SMA20") (pin "5") (pinfunction "5_5") (pintype "passive"))
      (node (ref "U20") (pin "11") (pinfunction "ANT_11") (pintype "passive"))
    )
    (net (code "69") (name "/RF21") (class "Default")
      (node (ref "SMA21") (pin "5") (pinfunction "5_5") (pintype "passive"))
      (node (ref "U21") (pin "11") (pinfunction "ANT_11") (pintype "passive"))
    )
    (net (code "70") (name "/RF22") (class "Default")
      (node (ref "SMA22") (pin "5") (pinfunction "5_5") (pintype "passive"))
      (node (ref "U22") (pin "11") (pinfunction "ANT_11") (pintype "passive"))
    )
    (net (code "71") (name "/RF23") (class "Default")
      (node (ref "SMA23") (pin "5") (pinfunction "5_5") (pintype "passive"))
      (node (ref "U23") (pin "11") (pinfunction "ANT_11") (pintype "passive"))
    )
    (net (code "72") (name "/RF24") (class "Default")
      (node (ref "SMA24") (pin "5") (pinfunction "5_5") (pintype "passive"))
      (node (ref "U24") (pin "11") (pinfunction "ANT_11") (pintype "passive"))
    )
    (net (code "73") (name "/RXD0_RF1") (class "Default")
      (node (ref "P1") (pin "5") (pinfunction "5_5") (pintype "passive"))
      (node (ref "U1") (pin "21") (pinfunction "RXD0_21") (pintype "passive"))
    )
    (net (code "74") (name "/RXD0_RF2") (class "Default")
      (node (ref "P2") (pin "5") (pinfunction "5_5") (pintype "passive"))
      (node (ref "U2") (pin "21") (pinfunction "RXD0_21") (pintype "passive"))
    )
    (net (code "75") (name "/RXD0_RF3") (class "Default")
      (node (ref "P3") (pin "5") (pinfunction "5_5") (pintype "passive"))
      (node (ref "U3") (pin "21") (pinfunction "RXD0_21") (pintype "passive"))
    )
    (net (code "76") (name "/RXD0_RF4") (class "Default")
      (node (ref "P4") (pin "5") (pinfunction "5_5") (pintype "passive"))
      (node (ref "U4") (pin "21") (pinfunction "RXD0_21") (pintype "passive"))
    )
    (net (code "77") (name "/RXD0_RF5") (class "Default")
      (node (ref "P5") (pin "5") (pinfunction "5_5") (pintype "passive"))
      (node (ref "U5") (pin "21") (pinfunction "RXD0_21") (pintype "passive"))
    )
    (net (code "78") (name "/RXD0_RF6") (class "Default")
      (node (ref "P6") (pin "5") (pinfunction "5_5") (pintype "passive"))
      (node (ref "U6") (pin "21") (pinfunction "RXD0_21") (pintype "passive"))
    )
    (net (code "79") (name "/RXD0_RF7") (class "Default")
      (node (ref "P7") (pin "5") (pinfunction "5_5") (pintype "passive"))
      (node (ref "U7") (pin "21") (pinfunction "RXD0_21") (pintype "passive"))
    )
    (net (code "80") (name "/RXD0_RF8") (class "Default")
      (node (ref "P8") (pin "5") (pinfunction "5_5") (pintype "passive"))
      (node (ref "U8") (pin "21") (pinfunction "RXD0_21") (pintype "passive"))
    )
    (net (code "81") (name "/RXD0_RF9") (class "Default")
      (node (ref "P9") (pin "5") (pinfunction "5_5") (pintype "passive"))
      (node (ref "U9") (pin "21") (pinfunction "RXD0_21") (pintype "passive"))
    )
    (net (code "82") (name "/RXD0_RF10") (class "Default")
      (node (ref "P10") (pin "5") (pinfunction "5_5") (pintype "passive"))
      (node (ref "U10") (pin "21") (pinfunction "RXD0_21") (pintype "passive"))
    )
    (net (code "83") (name "/RXD0_RF11") (class "Default")
      (node (ref "P11") (pin "5") (pinfunction "5_5") (pintype "passive"))
      (node (ref "U11") (pin "21") (pinfunction "RXD0_21") (pintype "passive"))
    )
    (net (code "84") (name "/RXD0_RF12") (class "Default")
      (node (ref "P12") (pin "5") (pinfunction "5_5") (pintype "passive"))
      (node (ref "U12") (pin "21") (pinfunction "RXD0_21") (pintype "passive"))
    )
    (net (code "85") (name "/RXD0_RF13") (class "Default")
      (node (ref "P13") (pin "5") (pinfunction "5_5") (pintype "passive"))
      (node (ref "U13") (pin "21") (pinfunction "RXD0_21") (pintype "passive"))
    )
    (net (code "86") (name "/RXD0_RF14") (class "Default")
      (node (ref "P14") (pin "5") (pinfunction "5_5") (pintype "passive"))
      (node (ref "U14") (pin "21") (pinfunction "RXD0_21") (pintype "passive"))
    )
    (net (code "87") (name "/RXD0_RF15") (class "Default")
      (node (ref "P15") (pin "5") (pinfunction "5_5") (pintype "passive"))
      (node (ref "U15") (pin "21") (pinfunction "RXD0_21") (pintype "passive"))
    )
    (net (code "88") (name "/RXD0_RF16") (class "Default")
      (node (ref "P16") (pin "5") (pinfunction "5_5") (pintype "passive"))
      (node (ref "U16") (pin "21") (pinfunction "RXD0_21") (pintype "passive"))
    )
    (net (code "89") (name "/RXD0_RF17") (class "Default")
      (node (ref "P17") (pin "5") (pinfunction "5_5") (pintype "passive"))
      (node (ref "U17") (pin "21") (pinfunction "RXD0_21") (pintype "passive"))
    )
    (net (code "90") (name "/RXD0_RF18") (class "Default")
      (node (ref "P18") (pin "5") (pinfunction "5_5") (pintype "passive"))
      (node (ref "U18") (pin "21") (pinfunction "RXD0_21") (pintype "passive"))
    )
    (net (code "91") (name "/RXD0_RF19") (class "Default")
      (node (ref "P19") (pin "5") (pinfunction "5_5") (pintype "passive"))
      (node (ref "U19") (pin "21") (pinfunction "RXD0_21") (pintype "passive"))
    )
    (net (code "92") (name "/RXD0_RF20") (class "Default")
      (node (ref "P20") (pin "5") (pinfunction "5_5") (pintype "passive"))
      (node (ref "U20") (pin "21") (pinfunction "RXD0_21") (pintype "passive"))
    )
    (net (code "93") (name "/RXD0_RF21") (class "Default")
      (node (ref "P21") (pin "5") (pinfunction "5_5") (pintype "passive"))
      (node (ref "U21") (pin "21") (pinfunction "RXD0_21") (pintype "passive"))
    )
    (net (code "94") (name "/RXD0_RF22") (class "Default")
      (node (ref "P22") (pin "5") (pinfunction "5_5") (pintype "passive"))
      (node (ref "U22") (pin "21") (pinfunction "RXD0_21") (pintype "passive"))
    )
    (net (code "95") (name "/RXD0_RF23") (class "Default")
      (node (ref "P23") (pin "5") (pinfunction "5_5") (pintype "passive"))
      (node (ref "U23") (pin "21") (pinfunction "RXD0_21") (pintype "passive"))
    )
    (net (code "96") (name "/RXD0_RF24") (class "Default")
      (node (ref "P24") (pin "5") (pinfunction "5_5") (pintype "passive"))
      (node (ref "U24") (pin "21") (pinfunction "RXD0_21") (pintype "passive"))
    )
    (net (code "97") (name "/TXD0_RF1") (class "Default")
      (node (ref "P1") (pin "6") (pinfunction "6_6") (pintype "passive"))
      (node (ref "U1") (pin "20") (pinfunction "TXD0_20") (pintype "passive"))
    )
    (net (code "98") (name "/TXD0_RF2") (class "Default")
      (node (ref "P2") (pin "6") (pinfunction "6_6") (pintype "passive"))
      (node (ref "U2") (pin "20") (pinfunction "TXD0_20") (pintype "passive"))
    )
    (net (code "99") (name "/TXD0_RF3") (class "Default")
      (node (ref "P3") (pin "6") (pinfunction "6_6") (pintype "passive"))
      (node (ref "U3") (pin "20") (pinfunction "TXD0_20") (pintype "passive"))
    )
    (net (code "100") (name "/TXD0_RF4") (class "Default")
      (node (ref "P4") (pin "6") (pinfunction "6_6") (pintype "passive"))
      (node (ref "U4") (pin "20") (pinfunction "TXD0_20") (pintype "passive"))
    )
    (net (code "101") (name "/TXD0_RF5") (class "Default")
      (node (ref "P5") (pin "6") (pinfunction "6_6") (pintype "passive"))
      (node (ref "U5") (pin "20") (pinfunction "TXD0_20") (pintype "passive"))
    )
    (net (code "102") (name "/TXD0_RF6") (class "Default")
      (node (ref "P6") (pin "6") (pinfunction "6_6") (pintype "passive"))
      (node (ref "U6") (pin "20") (pinfunction "TXD0_20") (pintype "passive"))
    )
    (net (code "103") (name "/TXD0_RF7") (class "Default")
      (node (ref "P7") (pin "6") (pinfunction "6_6") (pintype "passive"))
      (node (ref "U7") (pin "20") (pinfunction "TXD0_20") (pintype "passive"))
    )
    (net (code "104") (name "/TXD0_RF8") (class "Default")
      (node (ref "P8") (pin "6") (pinfunction "6_6") (pintype "passive"))
      (node (ref "U8") (pin "20") (pinfunction "TXD0_20") (pintype "passive"))
    )
    (net (code "105") (name "/TXD0_RF9") (class "Default")
      (node (ref "P9") (pin "6") (pinfunction "6_6") (pintype "passive"))
      (node (ref "U9") (pin "20") (pinfunction "TXD0_20") (pintype "passive"))
    )
    (net (code "106") (name "/TXD0_RF10") (class "Default")
      (node (ref "P10") (pin "6") (pinfunction "6_6") (pintype "passive"))
      (node (ref "U10") (pin "20") (pinfunction "TXD0_20") (pintype "passive"))
    )
    (net (code "107") (name "/TXD0_RF11") (class "Default")
      (node (ref "P11") (pin "6") (pinfunction "6_6") (pintype "passive"))
      (node (ref "U11") (pin "20") (pinfunction "TXD0_20") (pintype "passive"))
    )
    (net (code "108") (name "/TXD0_RF12") (class "Default")
      (node (ref "P12") (pin "6") (pinfunction "6_6") (pintype "passive"))
      (node (ref "U12") (pin "20") (pinfunction "TXD0_20") (pintype "passive"))
    )
    (net (code "109") (name "/TXD0_RF13") (class "Default")
      (node (ref "P13") (pin "6") (pinfunction "6_6") (pintype "passive"))
      (node (ref "U13") (pin "20") (pinfunction "TXD0_20") (pintype "passive"))
    )
    (net (code "110") (name "/TXD0_RF14") (class "Default")
      (node (ref "P14") (pin "6") (pinfunction "6_6") (pintype "passive"))
      (node (ref "U14") (pin "20") (pinfunction "TXD0_20") (pintype "passive"))
    )
    (net (code "111") (name "/TXD0_RF15") (class "Default")
      (node (ref "P15") (pin "6") (pinfunction "6_6") (pintype "passive"))
      (node (ref "U15") (pin "20") (pinfunction "TXD0_20") (pintype "passive"))
    )
    (net (code "112") (name "/TXD0_RF16") (class "Default")
      (node (ref "P16") (pin "6") (pinfunction "6_6") (pintype "passive"))
      (node (ref "U16") (pin "20") (pinfunction "TXD0_20") (pintype "passive"))
    )
    (net (code "113") (name "/TXD0_RF17") (class "Default")
      (node (ref "P17") (pin "6") (pinfunction "6_6") (pintype "passive"))
      (node (ref "U17") (pin "20") (pinfunction "TXD0_20") (pintype "passive"))
    )
    (net (code "114") (name "/TXD0_RF18") (class "Default")
      (node (ref "P18") (pin "6") (pinfunction "6_6") (pintype "passive"))
      (node (ref "U18") (pin "20") (pinfunction "TXD0_20") (pintype "passive"))
    )
    (net (code "115") (name "/TXD0_RF19") (class "Default")
      (node (ref "P19") (pin "6") (pinfunction "6_6") (pintype "passive"))
      (node (ref "U19") (pin "20") (pinfunction "TXD0_20") (pintype "passive"))
    )
    (net (code "116") (name "/TXD0_RF20") (class "Default")
      (node (ref "P20") (pin "6") (pinfunction "6_6") (pintype "passive"))
      (node (ref "U20") (pin "20") (pinfunction "TXD0_20") (pintype "passive"))
    )
    (net (code "117") (name "/TXD0_RF21") (class "Default")
      (node (ref "P21") (pin "6") (pinfunction "6_6") (pintype "passive"))
      (node (ref "U21") (pin "20") (pinfunction "TXD0_20") (pintype "passive"))
    )
    (net (code "118") (name "/TXD0_RF22") (class "Default")
      (node (ref "P22") (pin "6") (pinfunction "6_6") (pintype "passive"))
      (node (ref "U22") (pin "20") (pinfunction "TXD0_20") (pintype "passive"))
    )
    (net (code "119") (name "/TXD0_RF23") (class "Default")
      (node (ref "P23") (pin "6") (pinfunction "6_6") (pintype "passive"))
      (node (ref "U23") (pin "20") (pinfunction "TXD0_20") (pintype "passive"))
    )
    (net (code "120") (name "/TXD0_RF24") (class "Default")
      (node (ref "P24") (pin "6") (pinfunction "6_6") (pintype "passive"))
      (node (ref "U24") (pin "20") (pinfunction "TXD0_20") (pintype "passive"))
    )
    (net (code "121") (name "/VBAT_RF1") (class "Default")
      (node (ref "P1") (pin "2") (pinfunction "2_2") (pintype "passive"))
      (node (ref "U1") (pin "22") (pinfunction "VBAT_22") (pintype "passive"))
    )
    (net (code "122") (name "/VBAT_RF2") (class "Default")
      (node (ref "P2") (pin "2") (pinfunction "2_2") (pintype "passive"))
      (node (ref "U2") (pin "22") (pinfunction "VBAT_22") (pintype "passive"))
    )
    (net (code "123") (name "/VBAT_RF3") (class "Default")
      (node (ref "P3") (pin "2") (pinfunction "2_2") (pintype "passive"))
      (node (ref "U3") (pin "22") (pinfunction "VBAT_22") (pintype "passive"))
    )
    (net (code "124") (name "/VBAT_RF4") (class "Default")
      (node (ref "P4") (pin "2") (pinfunction "2_2") (pintype "passive"))
      (node (ref "U4") (pin "22") (pinfunction "VBAT_22") (pintype "passive"))
    )
    (net (code "125") (name "/VBAT_RF5") (class "Default")
      (node (ref "P5") (pin "2") (pinfunction "2_2") (pintype "passive"))
      (node (ref "U5") (pin "22") (pinfunction "VBAT_22") (pintype "passive"))
    )
    (net (code "126") (name "/VBAT_RF6") (class "Default")
      (node (ref "P6") (pin "2") (pinfunction "2_2") (pintype "passive"))
      (node (ref "U6") (pin "22") (pinfunction "VBAT_22") (pintype "passive"))
    )
    (net (code "127") (name "/VBAT_RF7") (class "Default")
      (node (ref "P7") (pin "2") (pinfunction "2_2") (pintype "passive"))
      (node (ref "U7") (pin "22") (pinfunction "VBAT_22") (pintype "passive"))
    )
    (net (code "128") (name "/VBAT_RF8") (class "Default")
      (node (ref "P8") (pin "2") (pinfunction "2_2") (pintype "passive"))
      (node (ref "U8") (pin "22") (pinfunction "VBAT_22") (pintype "passive"))
    )
    (net (code "129") (name "/VBAT_RF9") (class "Default")
      (node (ref "P9") (pin "2") (pinfunction "2_2") (pintype "passive"))
      (node (ref "U9") (pin "22") (pinfunction "VBAT_22") (pintype "passive"))
    )
    (net (code "130") (name "/VBAT_RF10") (class "Default")
      (node (ref "P10") (pin "2") (pinfunction "2_2") (pintype "passive"))
      (node (ref "U10") (pin "22") (pinfunction "VBAT_22") (pintype "passive"))
    )
    (net (code "131") (name "/VBAT_RF11") (class "Default")
      (node (ref "P11") (pin "2") (pinfunction "2_2") (pintype "passive"))
      (node (ref "U11") (pin "22") (pinfunction "VBAT_22") (pintype "passive"))
    )
    (net (code "132") (name "/VBAT_RF12") (class "Default")
      (node (ref "P12") (pin "2") (pinfunction "2_2") (pintype "passive"))
      (node (ref "U12") (pin "22") (pinfunction "VBAT_22") (pintype "passive"))
    )
    (net (code "133") (name "/VBAT_RF13") (class "Default")
      (node (ref "P13") (pin "2") (pinfunction "2_2") (pintype "passive"))
      (node (ref "U13") (pin "22") (pinfunction "VBAT_22") (pintype "passive"))
    )
    (net (code "134") (name "/VBAT_RF14") (class "Default")
      (node (ref "P14") (pin "2") (pinfunction "2_2") (pintype "passive"))
      (node (ref "U14") (pin "22") (pinfunction "VBAT_22") (pintype "passive"))
    )
    (net (code "135") (name "/VBAT_RF15") (class "Default")
      (node (ref "P15") (pin "2") (pinfunction "2_2") (pintype "passive"))
      (node (ref "U15") (pin "22") (pinfunction "VBAT_22") (pintype "passive"))
    )
    (net (code "136") (name "/VBAT_RF16") (class "Default")
      (node (ref "P16") (pin "2") (pinfunction "2_2") (pintype "passive"))
      (node (ref "U16") (pin "22") (pinfunction "VBAT_22") (pintype "passive"))
    )
    (net (code "137") (name "/VBAT_RF17") (class "Default")
      (node (ref "P17") (pin "2") (pinfunction "2_2") (pintype "passive"))
      (node (ref "U17") (pin "22") (pinfunction "VBAT_22") (pintype "passive"))
    )
    (net (code "138") (name "/VBAT_RF18") (class "Default")
      (node (ref "P18") (pin "2") (pinfunction "2_2") (pintype "passive"))
      (node (ref "U18") (pin "22") (pinfunction "VBAT_22") (pintype "passive"))
    )
    (net (code "139") (name "/VBAT_RF19") (class "Default")
      (node (ref "P19") (pin "2") (pinfunction "2_2") (pintype "passive"))
      (node (ref "U19") (pin "22") (pinfunction "VBAT_22") (pintype "passive"))
    )
    (net (code "140") (name "/VBAT_RF20") (class "Default")
      (node (ref "P20") (pin "2") (pinfunction "2_2") (pintype "passive"))
      (node (ref "U20") (pin "22") (pinfunction "VBAT_22") (pintype "passive"))
    )
    (net (code "141") (name "/VBAT_RF21") (class "Default")
      (node (ref "P21") (pin "2") (pinfunction "2_2") (pintype "passive"))
      (node (ref "U21") (pin "22") (pinfunction "VBAT_22") (pintype "passive"))
    )
    (net (code "142") (name "/VBAT_RF22") (class "Default")
      (node (ref "P22") (pin "2") (pinfunction "2_2") (pintype "passive"))
      (node (ref "U22") (pin "22") (pinfunction "VBAT_22") (pintype "passive"))
    )
    (net (code "143") (name "/VBAT_RF23") (class "Default")
      (node (ref "P23") (pin "2") (pinfunction "2_2") (pintype "passive"))
      (node (ref "U23") (pin "22") (pinfunction "VBAT_22") (pintype "passive"))
    )
    (net (code "144") (name "/VBAT_RF24") (class "Default")
      (node (ref "P24") (pin "2") (pinfunction "2_2") (pintype "passive"))
      (node (ref "U24") (pin "22") (pinfunction "VBAT_22") (pintype "passive"))
    )
    (net (code "145") (name "/VCC_RF_RF1") (class "Default")
      (node (ref "P1") (pin "10") (pinfunction "10_10") (pintype "passive"))
      (node (ref "U1") (pin "9") (pinfunction "VCC_RF_9") (pintype "passive"))
    )
    (net (code "146") (name "/VCC_RF_RF2") (class "Default")
      (node (ref "P2") (pin "10") (pinfunction "10_10") (pintype "passive"))
      (node (ref "U2") (pin "9") (pinfunction "VCC_RF_9") (pintype "passive"))
    )
    (net (code "147") (name "/VCC_RF_RF3") (class "Default")
      (node (ref "P3") (pin "10") (pinfunction "10_10") (pintype "passive"))
      (node (ref "U3") (pin "9") (pinfunction "VCC_RF_9") (pintype "passive"))
    )
    (net (code "148") (name "/VCC_RF_RF4") (class "Default")
      (node (ref "P4") (pin "10") (pinfunction "10_10") (pintype "passive"))
      (node (ref "U4") (pin "9") (pinfunction "VCC_RF_9") (pintype "passive"))
    )
    (net (code "149") (name "/VCC_RF_RF5") (class "Default")
      (node (ref "P5") (pin "10") (pinfunction "10_10") (pintype "passive"))
      (node (ref "U5") (pin "9") (pinfunction "VCC_RF_9") (pintype "passive"))
    )
    (net (code "150") (name "/VCC_RF_RF6") (class "Default")
      (node (ref "P6") (pin "10") (pinfunction "10_10") (pintype "passive"))
      (node (ref "U6") (pin "9") (pinfunction "VCC_RF_9") (pintype "passive"))
    )
    (net (code "151") (name "/VCC_RF_RF7") (class "Default")
      (node (ref "P7") (pin "10") (pinfunction "10_10") (pintype "passive"))
      (node (ref "U7") (pin "9") (pinfunction "VCC_RF_9") (pintype "passive"))
    )
    (net (code "152") (name "/VCC_RF_RF8") (class "Default")
      (node (ref "P8") (pin "10") (pinfunction "10_10") (pintype "passive"))
      (node (ref "U8") (pin "9") (pinfunction "VCC_RF_9") (pintype "passive"))
    )
    (net (code "153") (name "/VCC_RF_RF9") (class "Default")
      (node (ref "P9") (pin "10") (pinfunction "10_10") (pintype "passive"))
      (node (ref "U9") (pin "9") (pinfunction "VCC_RF_9") (pintype "passive"))
    )
    (net (code "154") (name "/VCC_RF_RF10") (class "Default")
      (node (ref "P10") (pin "10") (pinfunction "10_10") (pintype "passive"))
      (node (ref "U10") (pin "9") (pinfunction "VCC_RF_9") (pintype "passive"))
    )
    (net (code "155") (name "/VCC_RF_RF11") (class "Default")
      (node (ref "P11") (pin "10") (pinfunction "10_10") (pintype "passive"))
      (node (ref "U11") (pin "9") (pinfunction "VCC_RF_9") (pintype "passive"))
    )
    (net (code "156") (name "/VCC_RF_RF12") (class "Default")
      (node (ref "P12") (pin "10") (pinfunction "10_10") (pintype "passive"))
      (node (ref "U12") (pin "9") (pinfunction "VCC_RF_9") (pintype "passive"))
    )
    (net (code "157") (name "/VCC_RF_RF13") (class "Default")
      (node (ref "P13") (pin "10") (pinfunction "10_10") (pintype "passive"))
      (node (ref "U13") (pin "9") (pinfunction "VCC_RF_9") (pintype "passive"))
    )
    (net (code "158") (name "/VCC_RF_RF14") (class "Default")
      (node (ref "P14") (pin "10") (pinfunction "10_10") (pintype "passive"))
      (node (ref "U14") (pin "9") (pinfunction "VCC_RF_9") (pintype "passive"))
    )
    (net (code "159") (name "/VCC_RF_RF15") (class "Default")
      (node (ref "P15") (pin "10") (pinfunction "10_10") (pintype "passive"))
      (node (ref "U15") (pin "9") (pinfunction "VCC_RF_9") (pintype "passive"))
    )
    (net (code "160") (name "/VCC_RF_RF16") (class "Default")
      (node (ref "P16") (pin "10") (pinfunction "10_10") (pintype "passive"))
      (node (ref "U16") (pin "9") (pinfunction "VCC_RF_9") (pintype "passive"))
    )
    (net (code "161") (name "/VCC_RF_RF17") (class "Default")
      (node (ref "P17") (pin "10") (pinfunction "10_10") (pintype "passive"))
      (node (ref "U17") (pin "9") (pinfunction "VCC_RF_9") (pintype "passive"))
    )
    (net (code "162") (name "/VCC_RF_RF18") (class "Default")
      (node (ref "P18") (pin "10") (pinfunction "10_10") (pintype "passive"))
      (node (ref "U18") (pin "9") (pinfunction "VCC_RF_9") (pintype "passive"))
    )
    (net (code "163") (name "/VCC_RF_RF19") (class "Default")
      (node (ref "P19") (pin "10") (pinfunction "10_10") (pintype "passive"))
      (node (ref "U19") (pin "9") (pinfunction "VCC_RF_9") (pintype "passive"))
    )
    (net (code "164") (name "/VCC_RF_RF20") (class "Default")
      (node (ref "P20") (pin "10") (pinfunction "10_10") (pintype "passive"))
      (node (ref "U20") (pin "9") (pinfunction "VCC_RF_9") (pintype "passive"))
    )
    (net (code "165") (name "/VCC_RF_RF21") (class "Default")
      (node (ref "P21") (pin "10") (pinfunction "10_10") (pintype "passive"))
      (node (ref "U21") (pin "9") (pinfunction "VCC_RF_9") (pintype "passive"))
    )
    (net (code "166") (name "/VCC_RF_RF22") (class "Default")
      (node (ref "P22") (pin "10") (pinfunction "10_10") (pintype "passive"))
      (node (ref "U22") (pin "9") (pinfunction "VCC_RF_9") (pintype "passive"))
    )
    (net (code "167") (name "/VCC_RF_RF23") (class "Default")
      (node (ref "P23") (pin "10") (pinfunction "10_10") (pintype "passive"))
      (node (ref "U23") (pin "9") (pinfunction "VCC_RF_9") (pintype "passive"))
    )
    (net (code "168") (name "/VCC_RF_RF24") (class "Default")
      (node (ref "P24") (pin "10") (pinfunction "10_10") (pintype "passive"))
      (node (ref "U24") (pin "9") (pinfunction "VCC_RF_9") (pintype "passive"))
    )
    (net (code "169") (name "GND_RF1") (class "Default")
      (node (ref "P1") (pin "13") (pinfunction "13_13") (pintype "passive"))
      (node (ref "P1") (pin "14") (pinfunction "14_14") (pintype "passive"))
      (node (ref "P1") (pin "15") (pinfunction "15_15") (pintype "passive"))
      (node (ref "SMA1") (pin "1") (pinfunction "1_1") (pintype "passive"))
      (node (ref "SMA1") (pin "2") (pinfunction "2_2") (pintype "passive"))
      (node (ref "SMA1") (pin "3") (pinfunction "3_3") (pintype "passive"))
      (node (ref "SMA1") (pin "4") (pinfunction "4_4") (pintype "passive"))
      (node (ref "U1") (pin "10") (pinfunction "GND_10") (pintype "passive"))
      (node (ref "U1") (pin "12") (pinfunction "GND_12") (pintype "passive"))
      (node (ref "U1") (pin "13") (pinfunction "GND_13") (pintype "passive"))
      (node (ref "U1") (pin "24") (pinfunction "GND_24") (pintype "passive"))
    )
    (net (code "170") (name "GND_RF2") (class "Default")
      (node (ref "P2") (pin "13") (pinfunction "13_13") (pintype "passive"))
      (node (ref "P2") (pin "14") (pinfunction "14_14") (pintype "passive"))
      (node (ref "P2") (pin "15") (pinfunction "15_15") (pintype "passive"))
      (node (ref "SMA2") (pin "1") (pinfunction "1_1") (pintype "passive"))
      (node (ref "SMA2") (pin "2") (pinfunction "2_2") (pintype "passive"))
      (node (ref "SMA2") (pin "3") (pinfunction "3_3") (pintype "passive"))
      (node (ref "SMA2") (pin "4") (pinfunction "4_4") (pintype "passive"))
      (node (ref "U2") (pin "10") (pinfunction "GND_10") (pintype "passive"))
      (node (ref "U2") (pin "12") (pinfunction "GND_12") (pintype "passive"))
      (node (ref "U2") (pin "13") (pinfunction "GND_13") (pintype "passive"))
      (node (ref "U2") (pin "24") (pinfunction "GND_24") (pintype "passive"))
    )
    (net (code "171") (name "GND_RF3") (class "Default")
      (node (ref "P3") (pin "13") (pinfunction "13_13") (pintype "passive"))
      (node (ref "P3") (pin "14") (pinfunction "14_14") (pintype "passive"))
      (node (ref "P3") (pin "15") (pinfunction "15_15") (pintype "passive"))
      (node (ref "SMA3") (pin "1") (pinfunction "1_1") (pintype "passive"))
      (node (ref "SMA3") (pin "2") (pinfunction "2_2") (pintype "passive"))
      (node (ref "SMA3") (pin "3") (pinfunction "3_3") (pintype "passive"))
      (node (ref "SMA3") (pin "4") (pinfunction "4_4") (pintype "passive"))
      (node (ref "U3") (pin "10") (pinfunction "GND_10") (pintype "passive"))
      (node (ref "U3") (pin "12") (pinfunction "GND_12") (pintype "passive"))
      (node (ref "U3") (pin "13") (pinfunction "GND_13") (pintype "passive"))
      (node (ref "U3") (pin "24") (pinfunction "GND_24") (pintype "passive"))
    )
    (net (code "172") (name "GND_RF4") (class "Default")
      (node (ref "P4") (pin "13") (pinfunction "13_13") (pintype "passive"))
      (node (ref "P4") (pin "14") (pinfunction "14_14") (pintype "passive"))
      (node (ref "P4") (pin "15") (pinfunction "15_15") (pintype "passive"))
      (node (ref "SMA4") (pin "1") (pinfunction "1_1") (pintype "passive"))
      (node (ref "SMA4") (pin "2") (pinfunction "2_2") (pintype "passive"))
      (node (ref "SMA4") (pin "3") (pinfunction "3_3") (pintype "passive"))
      (node (ref "SMA4") (pin "4") (pinfunction "4_4") (pintype "passive"))
      (node (ref "U4") (pin "10") (pinfunction "GND_10") (pintype "passive"))
      (node (ref "U4") (pin "12") (pinfunction "GND_12") (pintype "passive"))
      (node (ref "U4") (pin "13") (pinfunction "GND_13") (pintype "passive"))
      (node (ref "U4") (pin "24") (pinfunction "GND_24") (pintype "passive"))
    )
    (net (code "173") (name "GND_RF5") (class "Default")
      (node (ref "P5") (pin "13") (pinfunction "13_13") (pintype "passive"))
      (node (ref "P5") (pin "14") (pinfunction "14_14") (pintype "passive"))
      (node (ref "P5") (pin "15") (pinfunction "15_15") (pintype "passive"))
      (node (ref "SMA5") (pin "1") (pinfunction "1_1") (pintype "passive"))
      (node (ref "SMA5") (pin "2") (pinfunction "2_2") (pintype "passive"))
      (node (ref "SMA5") (pin "3") (pinfunction "3_3") (pintype "passive"))
      (node (ref "SMA5") (pin "4") (pinfunction "4_4") (pintype "passive"))
      (node (ref "U5") (pin "10") (pinfunction "GND_10") (pintype "passive"))
      (node (ref "U5") (pin "12") (pinfunction "GND_12") (pintype "passive"))
      (node (ref "U5") (pin "13") (pinfunction "GND_13") (pintype "passive"))
      (node (ref "U5") (pin "24") (pinfunction "GND_24") (pintype "passive"))
    )
    (net (code "174") (name "GND_RF6") (class "Default")
      (node (ref "P6") (pin "13") (pinfunction "13_13") (pintype "passive"))
      (node (ref "P6") (pin "14") (pinfunction "14_14") (pintype "passive"))
      (node (ref "P6") (pin "15") (pinfunction "15_15") (pintype "passive"))
      (node (ref "SMA6") (pin "1") (pinfunction "1_1") (pintype "passive"))
      (node (ref "SMA6") (pin "2") (pinfunction "2_2") (pintype "passive"))
      (node (ref "SMA6") (pin "3") (pinfunction "3_3") (pintype "passive"))
      (node (ref "SMA6") (pin "4") (pinfunction "4_4") (pintype "passive"))
      (node (ref "U6") (pin "10") (pinfunction "GND_10") (pintype "passive"))
      (node (ref "U6") (pin "12") (pinfunction "GND_12") (pintype "passive"))
      (node (ref "U6") (pin "13") (pinfunction "GND_13") (pintype "passive"))
      (node (ref "U6") (pin "24") (pinfunction "GND_24") (pintype "passive"))
    )
    (net (code "175") (name "GND_RF7") (class "Default")
      (node (ref "P7") (pin "13") (pinfunction "13_13") (pintype "passive"))
      (node (ref "P7") (pin "14") (pinfunction "14_14") (pintype "passive"))
      (node (ref "P7") (pin "15") (pinfunction "15_15") (pintype "passive"))
      (node (ref "SMA7") (pin "1") (pinfunction "1_1") (pintype "passive"))
      (node (ref "SMA7") (pin "2") (pinfunction "2_2") (pintype "passive"))
      (node (ref "SMA7") (pin "3") (pinfunction "3_3") (pintype "passive"))
      (node (ref "SMA7") (pin "4") (pinfunction "4_4") (pintype "passive"))
      (node (ref "U7") (pin "10") (pinfunction "GND_10") (pintype "passive"))
      (node (ref "U7") (pin "12") (pinfunction "GND_12") (pintype "passive"))
      (node (ref "U7") (pin "13") (pinfunction "GND_13") (pintype "passive"))
      (node (ref "U7") (pin "24") (pinfunction "GND_24") (pintype "passive"))
    )
    (net (code "176") (name "GND_RF8") (class "Default")
      (node (ref "P8") (pin "13") (pinfunction "13_13") (pintype "passive"))
      (node (ref "P8") (pin "14") (pinfunction "14_14") (pintype "passive"))
      (node (ref "P8") (pin "15") (pinfunction "15_15") (pintype "passive"))
      (node (ref "SMA8") (pin "1") (pinfunction "1_1") (pintype "passive"))
      (node (ref "SMA8") (pin "2") (pinfunction "2_2") (pintype "passive"))
      (node (ref "SMA8") (pin "3") (pinfunction "3_3") (pintype "passive"))
      (node (ref "SMA8") (pin "4") (pinfunction "4_4") (pintype "passive"))
      (node (ref "U8") (pin "10") (pinfunction "GND_10") (pintype "passive"))
      (node (ref "U8") (pin "12") (pinfunction "GND_12") (pintype "passive"))
      (node (ref "U8") (pin "13") (pinfunction "GND_13") (pintype "passive"))
      (node (ref "U8") (pin "24") (pinfunction "GND_24") (pintype "passive"))
    )
    (net (code "177") (name "GND_RF9") (class "Default")
      (node (ref "P9") (pin "13") (pinfunction "13_13") (pintype "passive"))
      (node (ref "P9") (pin "14") (pinfunction "14_14") (pintype "passive"))
      (node (ref "P9") (pin "15") (pinfunction "15_15") (pintype "passive"))
      (node (ref "SMA9") (pin "1") (pinfunction "1_1") (pintype "passive"))
      (node (ref "SMA9") (pin "2") (pinfunction "2_2") (pintype "passive"))
      (node (ref "SMA9") (pin "3") (pinfunction "3_3") (pintype "passive"))
      (node (ref "SMA9") (pin "4") (pinfunction "4_4") (pintype "passive"))
      (node (ref "U9") (pin "10") (pinfunction "GND_10") (pintype "passive"))
      (node (ref "U9") (pin "12") (pinfunction "GND_12") (pintype "passive"))
      (node (ref "U9") (pin "13") (pinfunction "GND_13") (pintype "passive"))
      (node (ref "U9") (pin "24") (pinfunction "GND_24") (pintype "passive"))
    )
    (net (code "178") (name "GND_RF10") (class "Default")
      (node (ref "P10") (pin "13") (pinfunction "13_13") (pintype "passive"))
      (node (ref "P10") (pin "14") (pinfunction "14_14") (pintype "passive"))
      (node (ref "P10") (pin "15") (pinfunction "15_15") (pintype "passive"))
      (node (ref "SMA10") (pin "1") (pinfunction "1_1") (pintype "passive"))
      (node (ref "SMA10") (pin "2") (pinfunction "2_2") (pintype "passive"))
      (node (ref "SMA10") (pin "3") (pinfunction "3_3") (pintype "passive"))
      (node (ref "SMA10") (pin "4") (pinfunction "4_4") (pintype "passive"))
      (node (ref "U10") (pin "10") (pinfunction "GND_10") (pintype "passive"))
      (node (ref "U10") (pin "12") (pinfunction "GND_12") (pintype "passive"))
      (node (ref "U10") (pin "13") (pinfunction "GND_13") (pintype "passive"))
      (node (ref "U10") (pin "24") (pinfunction "GND_24") (pintype "passive"))
    )
    (net (code "179") (name "GND_RF11") (class "Default")
      (node (ref "P11") (pin "13") (pinfunction "13_13") (pintype "passive"))
      (node (ref "P11") (pin "14") (pinfunction "14_14") (pintype "passive"))
      (node (ref "P11") (pin "15") (pinfunction "15_15") (pintype "passive"))
      (node (ref "SMA11") (pin "1") (pinfunction "1_1") (pintype "passive"))
      (node (ref "SMA11") (pin "2") (pinfunction "2_2") (pintype "passive"))
      (node (ref "SMA11") (pin "3") (pinfunction "3_3") (pintype "passive"))
      (node (ref "SMA11") (pin "4") (pinfunction "4_4") (pintype "passive"))
      (node (ref "U11") (pin "10") (pinfunction "GND_10") (pintype "passive"))
      (node (ref "U11") (pin "12") (pinfunction "GND_12") (pintype "passive"))
      (node (ref "U11") (pin "13") (pinfunction "GND_13") (pintype "passive"))
      (node (ref "U11") (pin "24") (pinfunction "GND_24") (pintype "passive"))
    )
    (net (code "180") (name "GND_RF12") (class "Default")
      (node (ref "P12") (pin "13") (pinfunction "13_13") (pintype "passive"))
      (node (ref "P12") (pin "14") (pinfunction "14_14") (pintype "passive"))
      (node (ref "P12") (pin "15") (pinfunction "15_15") (pintype "passive"))
      (node (ref "SMA12") (pin "1") (pinfunction "1_1") (pintype "passive"))
      (node (ref "SMA12") (pin "2") (pinfunction "2_2") (pintype "passive"))
      (node (ref "SMA12") (pin "3") (pinfunction "3_3") (pintype "passive"))
      (node (ref "SMA12") (pin "4") (pinfunction "4_4") (pintype "passive"))
      (node (ref "U12") (pin "10") (pinfunction "GND_10") (pintype "passive"))
      (node (ref "U12") (pin "12") (pinfunction "GND_12") (pintype "passive"))
      (node (ref "U12") (pin "13") (pinfunction "GND_13") (pintype "passive"))
      (node (ref "U12") (pin "24") (pinfunction "GND_24") (pintype "passive"))
    )
    (net (code "181") (name "GND_RF13") (class "Default")
      (node (ref "P13") (pin "13") (pinfunction "13_13") (pintype "passive"))
      (node (ref "P13") (pin "14") (pinfunction "14_14") (pintype "passive"))
      (node (ref "P13") (pin "15") (pinfunction "15_15") (pintype "passive"))
      (node (ref "SMA13") (pin "1") (pinfunction "1_1") (pintype "passive"))
      (node (ref "SMA13") (pin "2") (pinfunction "2_2") (pintype "passive"))
      (node (ref "SMA13") (pin "3") (pinfunction "3_3") (pintype "passive"))
      (node (ref "SMA13") (pin "4") (pinfunction "4_4") (pintype "passive"))
      (node (ref "U13") (pin "10") (pinfunction "GND_10") (pintype "passive"))
      (node (ref "U13") (pin "12") (pinfunction "GND_12") (pintype "passive"))
      (node (ref "U13") (pin "13") (pinfunction "GND_13") (pintype "passive"))
      (node (ref "U13") (pin "24") (pinfunction "GND_24") (pintype "passive"))
    )
    (net (code "182") (name "GND_RF14") (class "Default")
      (node (ref "P14") (pin "13") (pinfunction "13_13") (pintype "passive"))
      (node (ref "P14") (pin "14") (pinfunction "14_14") (pintype "passive"))
      (node (ref "P14") (pin "15") (pinfunction "15_15") (pintype "passive"))
      (node (ref "SMA14") (pin "1") (pinfunction "1_1") (pintype "passive"))
      (node (ref "SMA14") (pin "2") (pinfunction "2_2") (pintype "passive"))
      (node (ref "SMA14") (pin "3") (pinfunction "3_3") (pintype "passive"))
      (node (ref "SMA14") (pin "4") (pinfunction "4_4") (pintype "passive"))
      (node (ref "U14") (pin "10") (pinfunction "GND_10") (pintype "passive"))
      (node (ref "U14") (pin "12") (pinfunction "GND_12") (pintype "passive"))
      (node (ref "U14") (pin "13") (pinfunction "GND_13") (pintype "passive"))
      (node (ref "U14") (pin "24") (pinfunction "GND_24") (pintype "passive"))
    )
    (net (code "183") (name "GND_RF15") (class "Default")
      (node (ref "P15") (pin "13") (pinfunction "13_13") (pintype "passive"))
      (node (ref "P15") (pin "14") (pinfunction "14_14") (pintype "passive"))
      (node (ref "P15") (pin "15") (pinfunction "15_15") (pintype "passive"))
      (node (ref "SMA15") (pin "1") (pinfunction "1_1") (pintype "passive"))
      (node (ref "SMA15") (pin "2") (pinfunction "2_2") (pintype "passive"))
      (node (ref "SMA15") (pin "3") (pinfunction "3_3") (pintype "passive"))
      (node (ref "SMA15") (pin "4") (pinfunction "4_4") (pintype "passive"))
      (node (ref "U15") (pin "10") (pinfunction "GND_10") (pintype "passive"))
      (node (ref "U15") (pin "12") (pinfunction "GND_12") (pintype "passive"))
      (node (ref "U15") (pin "13") (pinfunction "GND_13") (pintype "passive"))
      (node (ref "U15") (pin "24") (pinfunction "GND_24") (pintype "passive"))
    )
    (net (code "184") (name "GND_RF16") (class "Default")
      (node (ref "P16") (pin "13") (pinfunction "13_13") (pintype "passive"))
      (node (ref "P16") (pin "14") (pinfunction "14_14") (pintype "passive"))
      (node (ref "P16") (pin "15") (pinfunction "15_15") (pintype "passive"))
      (node (ref "SMA16") (pin "1") (pinfunction "1_1") (pintype "passive"))
      (node (ref "SMA16") (pin "2") (pinfunction "2_2") (pintype "passive"))
      (node (ref "SMA16") (pin "3") (pinfunction "3_3") (pintype "passive"))
      (node (ref "SMA16") (pin "4") (pinfunction "4_4") (pintype "passive"))
      (node (ref "U16") (pin "10") (pinfunction "GND_10") (pintype "passive"))
      (node (ref "U16") (pin "12") (pinfunction "GND_12") (pintype "passive"))
      (node (ref "U16") (pin "13") (pinfunction "GND_13") (pintype "passive"))
      (node (ref "U16") (pin "24") (pinfunction "GND_24") (pintype "passive"))
    )
    (net (code "185") (name "GND_RF17") (class "Default")
      (node (ref "P17") (pin "13") (pinfunction "13_13") (pintype "passive"))
      (node (ref "P17") (pin "14") (pinfunction "14_14") (pintype "passive"))
      (node (ref "P17") (pin "15") (pinfunction "15_15") (pintype "passive"))
      (node (ref "SMA17") (pin "1") (pinfunction "1_1") (pintype "passive"))
      (node (ref "SMA17") (pin "2") (pinfunction "2_2") (pintype "passive"))
      (node (ref "SMA17") (pin "3") (pinfunction "3_3") (pintype "passive"))
      (node (ref "SMA17") (pin "4") (pinfunction "4_4") (pintype "passive"))
      (node (ref "U17") (pin "10") (pinfunction "GND_10") (pintype "passive"))
      (node (ref "U17") (pin "12") (pinfunction "GND_12") (pintype "passive"))
      (node (ref "U17") (pin "13") (pinfunction "GND_13") (pintype "passive"))
      (node (ref "U17") (pin "24") (pinfunction "GND_24") (pintype "passive"))
    )
    (net (code "186") (name "GND_RF18") (class "Default")
      (node (ref "P18") (pin "13") (pinfunction "13_13") (pintype "passive"))
      (node (ref "P18") (pin "14") (pinfunction "14_14") (pintype "passive"))
      (node (ref "P18") (pin "15") (pinfunction "15_15") (pintype "passive"))
      (node (ref "SMA18") (pin "1") (pinfunction "1_1") (pintype "passive"))
      (node (ref "SMA18") (pin "2") (pinfunction "2_2") (pintype "passive"))
      (node (ref "SMA18") (pin "3") (pinfunction "3_3") (pintype "passive"))
      (node (ref "SMA18") (pin "4") (pinfunction "4_4") (pintype "passive"))
      (node (ref "U18") (pin "10") (pinfunction "GND_10") (pintype "passive"))
      (node (ref "U18") (pin "12") (pinfunction "GND_12") (pintype "passive"))
      (node (ref "U18") (pin "13") (pinfunction "GND_13") (pintype "passive"))
      (node (ref "U18") (pin "24") (pinfunction "GND_24") (pintype "passive"))
    )
    (net (code "187") (name "GND_RF19") (class "Default")
      (node (ref "P19") (pin "13") (pinfunction "13_13") (pintype "passive"))
      (node (ref "P19") (pin "14") (pinfunction "14_14") (pintype "passive"))
      (node (ref "P19") (pin "15") (pinfunction "15_15") (pintype "passive"))
      (node (ref "SMA19") (pin "1") (pinfunction "1_1") (pintype "passive"))
      (node (ref "SMA19") (pin "2") (pinfunction "2_2") (pintype "passive"))
      (node (ref "SMA19") (pin "3") (pinfunction "3_3") (pintype "passive"))
      (node (ref "SMA19") (pin "4") (pinfunction "4_4") (pintype "passive"))
      (node (ref "U19") (pin "10") (pinfunction "GND_10") (pintype "passive"))
      (node (ref "U19") (pin "12") (pinfunction "GND_12") (pintype "passive"))
      (node (ref "U19") (pin "13") (pinfunction "GND_13") (pintype "passive"))
      (node (ref "U19") (pin "24") (pinfunction "GND_24") (pintype "passive"))
    )
    (net (code "188") (name "GND_RF20") (class "Default")
      (node (ref "P20") (pin "13") (pinfunction "13_13") (pintype "passive"))
      (node (ref "P20") (pin "14") (pinfunction "14_14") (pintype "passive"))
      (node (ref "P20") (pin "15") (pinfunction "15_15") (pintype "passive"))
      (node (ref "SMA20") (pin "1") (pinfunction "1_1") (pintype "passive"))
      (node (ref "SMA20") (pin "2") (pinfunction "2_2") (pintype "passive"))
      (node (ref "SMA20") (pin "3") (pinfunction "3_3") (pintype "passive"))
      (node (ref "SMA20") (pin "4") (pinfunction "4_4") (pintype "passive"))
      (node (ref "U20") (pin "10") (pinfunction "GND_10") (pintype "passive"))
      (node (ref "U20") (pin "12") (pinfunction "GND_12") (pintype "passive"))
      (node (ref "U20") (pin "13") (pinfunction "GND_13") (pintype "passive"))
      (node (ref "U20") (pin "24") (pinfunction "GND_24") (pintype "passive"))
    )
    (net (code "189") (name "GND_RF21") (class "Default")
      (node (ref "P21") (pin "13") (pinfunction "13_13") (pintype "passive"))
      (node (ref "P21") (pin "14") (pinfunction "14_14") (pintype "passive"))
      (node (ref "P21") (pin "15") (pinfunction "15_15") (pintype "passive"))
      (node (ref "SMA21") (pin "1") (pinfunction "1_1") (pintype "passive"))
      (node (ref "SMA21") (pin "2") (pinfunction "2_2") (pintype "passive"))
      (node (ref "SMA21") (pin "3") (pinfunction "3_3") (pintype "passive"))
      (node (ref "SMA21") (pin "4") (pinfunction "4_4") (pintype "passive"))
      (node (ref "U21") (pin "10") (pinfunction "GND_10") (pintype "passive"))
      (node (ref "U21") (pin "12") (pinfunction "GND_12") (pintype "passive"))
      (node (ref "U21") (pin "13") (pinfunction "GND_13") (pintype "passive"))
      (node (ref "U21") (pin "24") (pinfunction "GND_24") (pintype "passive"))
    )
    (net (code "190") (name "GND_RF22") (class "Default")
      (node (ref "P22") (pin "13") (pinfunction "13_13") (pintype "passive"))
      (node (ref "P22") (pin "14") (pinfunction "14_14") (pintype "passive"))
      (node (ref "P22") (pin "15") (pinfunction "15_15") (pintype "passive"))
      (node (ref "SMA22") (pin "1") (pinfunction "1_1") (pintype "passive"))
      (node (ref "SMA22") (pin "2") (pinfunction "2_2") (pintype "passive"))
      (node (ref "SMA22") (pin "3") (pinfunction "3_3") (pintype "passive"))
      (node (ref "SMA22") (pin "4") (pinfunction "4_4") (pintype "passive"))
      (node (ref "U22") (pin "10") (pinfunction "GND_10") (pintype "passive"))
      (node (ref "U22") (pin "12") (pinfunction "GND_12") (pintype "passive"))
      (node (ref "U22") (pin "13") (pinfunction "GND_13") (pintype "passive"))
      (node (ref "U22") (pin "24") (pinfunction "GND_24") (pintype "passive"))
    )
    (net (code "191") (name "GND_RF23") (class "Default")
      (node (ref "P23") (pin "13") (pinfunction "13_13") (pintype "passive"))
      (node (ref "P23") (pin "14") (pinfunction "14_14") (pintype "passive"))
      (node (ref "P23") (pin "15") (pinfunction "15_15") (pintype "passive"))
      (node (ref "SMA23") (pin "1") (pinfunction "1_1") (pintype "passive"))
      (node (ref "SMA23") (pin "2") (pinfunction "2_2") (pintype "passive"))
      (node (ref "SMA23") (pin "3") (pinfunction "3_3") (pintype "passive"))
      (node (ref "SMA23") (pin "4") (pinfunction "4_4") (pintype "passive"))
      (node (ref "U23") (pin "10") (pinfunction "GND_10") (pintype "passive"))
      (node (ref "U23") (pin "12") (pinfunction "GND_12") (pintype "passive"))
      (node (ref "U23") (pin "13") (pinfunction "GND_13") (pintype "passive"))
      (node (ref "U23") (pin "24") (pinfunction "GND_24") (pintype "passive"))
    )
    (net (code "192") (name "GND_RF24") (class "Default")
      (node (ref "P24") (pin "13") (pinfunction "13_13") (pintype "passive"))
      (node (ref "P24") (pin "14") (pinfunction "14_14") (pintype "passive"))
      (node (ref "P24") (pin "15") (pinfunction "15_15") (pintype "passive"))
      (node (ref "SMA24") (pin "1") (pinfunction "1_1") (pintype "passive"))
      (node (ref "SMA24") (pin "2") (pinfunction "2_2") (pintype "passive"))
      (node (ref "SMA24") (pin "3") (pinfunction "3_3") (pintype "passive"))
      (node (ref "SMA24") (pin "4") (pinfunction "4_4") (pintype "passive"))
      (node (ref "U24") (pin "10") (pinfunction "GND_10") (pintype "passive"))
      (node (ref "U24") (pin "12") (pinfunction "GND_12") (pintype "passive"))
      (node (ref "U24") (pin "13") (pinfunction "GND_13") (pintype "passive"))
      (node (ref "U24") (pin "24") (pinfunction "GND_24") (pintype "passive"))
    )
    (net (code "193") (name "unconnected-(P1-Pad3)") (class "Default")
      (node (ref "P1") (pin "3") (pinfunction "3_3") (pintype "passive"))
    )
    (net (code "194") (name "unconnected-(P1-Pad4)") (class "Default")
      (node (ref "P1") (pin "4") (pinfunction "4_4") (pintype "passive"))
    )
    (net (code "195") (name "unconnected-(P1-Pad7)") (class "Default")
      (node (ref "P1") (pin "7") (pinfunction "7_7") (pintype "passive"))
    )
    (net (code "196") (name "unconnected-(P1-Pad8)") (class "Default")
      (node (ref "P1") (pin "8") (pinfunction "8_8") (pintype "passive"))
    )
    (net (code "197") (name "unconnected-(P1-Pad11)") (class "Default")
      (node (ref "P1") (pin "11") (pinfunction "11_11") (pintype "passive"))
    )
    (net (code "198") (name "unconnected-(P1-Pad12)") (class "Default")
      (node (ref "P1") (pin "12") (pinfunction "12_12") (pintype "passive"))
    )
    (net (code "199") (name "unconnected-(P1-Pad16)") (class "Default")
      (node (ref "P1") (pin "16") (pinfunction "16_16") (pintype "passive"))
    )
    (net (code "200") (name "unconnected-(P2-Pad3)") (class "Default")
      (node (ref "P2") (pin "3") (pinfunction "3_3") (pintype "passive"))
    )
    (net (code "201") (name "unconnected-(P2-Pad4)") (class "Default")
      (node (ref "P2") (pin "4") (pinfunction "4_4") (pintype "passive"))
    )
    (net (code "202") (name "unconnected-(P2-Pad7)") (class "Default")
      (node (ref "P2") (pin "7") (pinfunction "7_7") (pintype "passive"))
    )
    (net (code "203") (name "unconnected-(P2-Pad8)") (class "Default")
      (node (ref "P2") (pin "8") (pinfunction "8_8") (pintype "passive"))
    )
    (net (code "204") (name "unconnected-(P2-Pad11)") (class "Default")
      (node (ref "P2") (pin "11") (pinfunction "11_11") (pintype "passive"))
    )
    (net (code "205") (name "unconnected-(P2-Pad12)") (class "Default")
      (node (ref "P2") (pin "12") (pinfunction "12_12") (pintype "passive"))
    )
    (net (code "206") (name "unconnected-(P2-Pad16)") (class "Default")
      (node (ref "P2") (pin "16") (pinfunction "16_16") (pintype "passive"))
    )
    (net (code "207") (name "unconnected-(P3-Pad3)") (class "Default")
      (node (ref "P3") (pin "3") (pinfunction "3_3") (pintype "passive"))
    )
    (net (code "208") (name "unconnected-(P3-Pad4)") (class "Default")
      (node (ref "P3") (pin "4") (pinfunction "4_4") (pintype "passive"))
    )
    (net (code "209") (name "unconnected-(P3-Pad7)") (class "Default")
      (node (ref "P3") (pin "7") (pinfunction "7_7") (pintype "passive"))
    )
    (net (code "210") (name "unconnected-(P3-Pad8)") (class "Default")
      (node (ref "P3") (pin "8") (pinfunction "8_8") (pintype "passive"))
    )
    (net (code "211") (name "unconnected-(P3-Pad11)") (class "Default")
      (node (ref "P3") (pin "11") (pinfunction "11_11") (pintype "passive"))
    )
    (net (code "212") (name "unconnected-(P3-Pad12)") (class "Default")
      (node (ref "P3") (pin "12") (pinfunction "12_12") (pintype "passive"))
    )
    (net (code "213") (name "unconnected-(P3-Pad16)") (class "Default")
      (node (ref "P3") (pin "16") (pinfunction "16_16") (pintype "passive"))
    )
    (net (code "214") (name "unconnected-(P4-Pad3)") (class "Default")
      (node (ref "P4") (pin "3") (pinfunction "3_3") (pintype "passive"))
    )
    (net (code "215") (name "unconnected-(P4-Pad4)") (class "Default")
      (node (ref "P4") (pin "4") (pinfunction "4_4") (pintype "passive"))
    )
    (net (code "216") (name "unconnected-(P4-Pad7)") (class "Default")
      (node (ref "P4") (pin "7") (pinfunction "7_7") (pintype "passive"))
    )
    (net (code "217") (name "unconnected-(P4-Pad8)") (class "Default")
      (node (ref "P4") (pin "8") (pinfunction "8_8") (pintype "passive"))
    )
    (net (code "218") (name "unconnected-(P4-Pad11)") (class "Default")
      (node (ref "P4") (pin "11") (pinfunction "11_11") (pintype "passive"))
    )
    (net (code "219") (name "unconnected-(P4-Pad12)") (class "Default")
      (node (ref "P4") (pin "12") (pinfunction "12_12") (pintype "passive"))
    )
    (net (code "220") (name "unconnected-(P4-Pad16)") (class "Default")
      (node (ref "P4") (pin "16") (pinfunction "16_16") (pintype "passive"))
    )
    (net (code "221") (name "unconnected-(P5-Pad3)") (class "Default")
      (node (ref "P5") (pin "3") (pinfunction "3_3") (pintype "passive"))
    )
    (net (code "222") (name "unconnected-(P5-Pad4)") (class "Default")
      (node (ref "P5") (pin "4") (pinfunction "4_4") (pintype "passive"))
    )
    (net (code "223") (name "unconnected-(P5-Pad7)") (class "Default")
      (node (ref "P5") (pin "7") (pinfunction "7_7") (pintype "passive"))
    )
    (net (code "224") (name "unconnected-(P5-Pad8)") (class "Default")
      (node (ref "P5") (pin "8") (pinfunction "8_8") (pintype "passive"))
    )
    (net (code "225") (name "unconnected-(P5-Pad11)") (class "Default")
      (node (ref "P5") (pin "11") (pinfunction "11_11") (pintype "passive"))
    )
    (net (code "226") (name "unconnected-(P5-Pad12)") (class "Default")
      (node (ref "P5") (pin "12") (pinfunction "12_12") (pintype "passive"))
    )
    (net (code "227") (name "unconnected-(P5-Pad16)") (class "Default")
      (node (ref "P5") (pin "16") (pinfunction "16_16") (pintype "passive"))
    )
    (net (code "228") (name "unconnected-(P6-Pad3)") (class "Default")
      (node (ref "P6") (pin "3") (pinfunction "3_3") (pintype "passive"))
    )
    (net (code "229") (name "unconnected-(P6-Pad4)") (class "Default")
      (node (ref "P6") (pin "4") (pinfunction "4_4") (pintype "passive"))
    )
    (net (code "230") (name "unconnected-(P6-Pad7)") (class "Default")
      (node (ref "P6") (pin "7") (pinfunction "7_7") (pintype "passive"))
    )
    (net (code "231") (name "unconnected-(P6-Pad8)") (class "Default")
      (node (ref "P6") (pin "8") (pinfunction "8_8") (pintype "passive"))
    )
    (net (code "232") (name "unconnected-(P6-Pad11)") (class "Default")
      (node (ref "P6") (pin "11") (pinfunction "11_11") (pintype "passive"))
    )
    (net (code "233") (name "unconnected-(P6-Pad12)") (class "Default")
      (node (ref "P6") (pin "12") (pinfunction "12_12") (pintype "passive"))
    )
    (net (code "234") (name "unconnected-(P6-Pad16)") (class "Default")
      (node (ref "P6") (pin "16") (pinfunction "16_16") (pintype "passive"))
    )
    (net (code "235") (name "unconnected-(P7-Pad3)") (class "Default")
      (node (ref "P7") (pin "3") (pinfunction "3_3") (pintype "passive"))
    )
    (net (code "236") (name "unconnected-(P7-Pad4)") (class "Default")
      (node (ref "P7") (pin "4") (pinfunction "4_4") (pintype "passive"))
    )
    (net (code "237") (name "unconnected-(P7-Pad7)") (class "Default")
      (node (ref "P7") (pin "7") (pinfunction "7_7") (pintype "passive"))
    )
    (net (code "238") (name "unconnected-(P7-Pad8)") (class "Default")
      (node (ref "P7") (pin "8") (pinfunction "8_8") (pintype "passive"))
    )
    (net (code "239") (name "unconnected-(P7-Pad11)") (class "Default")
      (node (ref "P7") (pin "11") (pinfunction "11_11") (pintype "passive"))
    )
    (net (code "240") (name "unconnected-(P7-Pad12)") (class "Default")
      (node (ref "P7") (pin "12") (pinfunction "12_12") (pintype "passive"))
    )
    (net (code "241") (name "unconnected-(P7-Pad16)") (class "Default")
      (node (ref "P7") (pin "16") (pinfunction "16_16") (pintype "passive"))
    )
    (net (code "242") (name "unconnected-(P8-Pad3)") (class "Default")
      (node (ref "P8") (pin "3") (pinfunction "3_3") (pintype "passive"))
    )
    (net (code "243") (name "unconnected-(P8-Pad4)") (class "Default")
      (node (ref "P8") (pin "4") (pinfunction "4_4") (pintype "passive"))
    )
    (net (code "244") (name "unconnected-(P8-Pad7)") (class "Default")
      (node (ref "P8") (pin "7") (pinfunction "7_7") (pintype "passive"))
    )
    (net (code "245") (name "unconnected-(P8-Pad8)") (class "Default")
      (node (ref "P8") (pin "8") (pinfunction "8_8") (pintype "passive"))
    )
    (net (code "246") (name "unconnected-(P8-Pad11)") (class "Default")
      (node (ref "P8") (pin "11") (pinfunction "11_11") (pintype "passive"))
    )
    (net (code "247") (name "unconnected-(P8-Pad12)") (class "Default")
      (node (ref "P8") (pin "12") (pinfunction "12_12") (pintype "passive"))
    )
    (net (code "248") (name "unconnected-(P8-Pad16)") (class "Default")
      (node (ref "P8") (pin "16") (pinfunction "16_16") (pintype "passive"))
    )
    (net (code "249") (name "unconnected-(P9-Pad3)") (class "Default")
      (node (ref "P9") (pin "3") (pinfunction "3_3") (pintype "passive"))
    )
    (net (code "250") (name "unconnected-(P9-Pad4)") (class "Default")
      (node (ref "P9") (pin "4") (pinfunction "4_4") (pintype "passive"))
    )
    (net (code "251") (name "unconnected-(P9-Pad7)") (class "Default")
      (node (ref "P9") (pin "7") (pinfunction "7_7") (pintype "passive"))
    )
    (net (code "252") (name "unconnected-(P9-Pad8)") (class "Default")
      (node (ref "P9") (pin "8") (pinfunction "8_8") (pintype "passive"))
    )
    (net (code "253") (name "unconnected-(P9-Pad11)") (class "Default")
      (node (ref "P9") (pin "11") (pinfunction "11_11") (pintype "passive"))
    )
    (net (code "254") (name "unconnected-(P9-Pad12)") (class "Default")
      (node (ref "P9") (pin "12") (pinfunction "12_12") (pintype "passive"))
    )
    (net (code "255") (name "unconnected-(P9-Pad16)") (class "Default")
      (node (ref "P9") (pin "16") (pinfunction "16_16") (pintype "passive"))
    )
    (net (code "256") (name "unconnected-(P10-Pad3)") (class "Default")
      (node (ref "P10") (pin "3") (pinfunction "3_3") (pintype "passive"))
    )
    (net (code "257") (name "unconnected-(P10-Pad4)") (class "Default")
      (node (ref "P10") (pin "4") (pinfunction "4_4") (pintype "passive"))
    )
    (net (code "258") (name "unconnected-(P10-Pad7)") (class "Default")
      (node (ref "P10") (pin "7") (pinfunction "7_7") (pintype "passive"))
    )
    (net (code "259") (name "unconnected-(P10-Pad8)") (class "Default")
      (node (ref "P10") (pin "8") (pinfunction "8_8") (pintype "passive"))
    )
    (net (code "260") (name "unconnected-(P10-Pad11)") (class "Default")
      (node (ref "P10") (pin "11") (pinfunction "11_11") (pintype "passive"))
    )
    (net (code "261") (name "unconnected-(P10-Pad12)") (class "Default")
      (node (ref "P10") (pin "12") (pinfunction "12_12") (pintype "passive"))
    )
    (net (code "262") (name "unconnected-(P10-Pad16)") (class "Default")
      (node (ref "P10") (pin "16") (pinfunction "16_16") (pintype "passive"))
    )
    (net (code "263") (name "unconnected-(P11-Pad3)") (class "Default")
      (node (ref "P11") (pin "3") (pinfunction "3_3") (pintype "passive"))
    )
    (net (code "264") (name "unconnected-(P11-Pad4)") (class "Default")
      (node (ref "P11") (pin "4") (pinfunction "4_4") (pintype "passive"))
    )
    (net (code "265") (name "unconnected-(P11-Pad7)") (class "Default")
      (node (ref "P11") (pin "7") (pinfunction "7_7") (pintype "passive"))
    )
    (net (code "266") (name "unconnected-(P11-Pad8)") (class "Default")
      (node (ref "P11") (pin "8") (pinfunction "8_8") (pintype "passive"))
    )
    (net (code "267") (name "unconnected-(P11-Pad11)") (class "Default")
      (node (ref "P11") (pin "11") (pinfunction "11_11") (pintype "passive"))
    )
    (net (code "268") (name "unconnected-(P11-Pad12)") (class "Default")
      (node (ref "P11") (pin "12") (pinfunction "12_12") (pintype "passive"))
    )
    (net (code "269") (name "unconnected-(P11-Pad16)") (class "Default")
      (node (ref "P11") (pin "16") (pinfunction "16_16") (pintype "passive"))
    )
    (net (code "270") (name "unconnected-(P12-Pad3)") (class "Default")
      (node (ref "P12") (pin "3") (pinfunction "3_3") (pintype "passive"))
    )
    (net (code "271") (name "unconnected-(P12-Pad4)") (class "Default")
      (node (ref "P12") (pin "4") (pinfunction "4_4") (pintype "passive"))
    )
    (net (code "272") (name "unconnected-(P12-Pad7)") (class "Default")
      (node (ref "P12") (pin "7") (pinfunction "7_7") (pintype "passive"))
    )
    (net (code "273") (name "unconnected-(P12-Pad8)") (class "Default")
      (node (ref "P12") (pin "8") (pinfunction "8_8") (pintype "passive"))
    )
    (net (code "274") (name "unconnected-(P12-Pad11)") (class "Default")
      (node (ref "P12") (pin "11") (pinfunction "11_11") (pintype "passive"))
    )
    (net (code "275") (name "unconnected-(P12-Pad12)") (class "Default")
      (node (ref "P12") (pin "12") (pinfunction "12_12") (pintype "passive"))
    )
    (net (code "276") (name "unconnected-(P12-Pad16)") (class "Default")
      (node (ref "P12") (pin "16") (pinfunction "16_16") (pintype "passive"))
    )
    (net (code "277") (name "unconnected-(P13-Pad3)") (class "Default")
      (node (ref "P13") (pin "3") (pinfunction "3_3") (pintype "passive"))
    )
    (net (code "278") (name "unconnected-(P13-Pad4)") (class "Default")
      (node (ref "P13") (pin "4") (pinfunction "4_4") (pintype "passive"))
    )
    (net (code "279") (name "unconnected-(P13-Pad7)") (class "Default")
      (node (ref "P13") (pin "7") (pinfunction "7_7") (pintype "passive"))
    )
    (net (code "280") (name "unconnected-(P13-Pad8)") (class "Default")
      (node (ref "P13") (pin "8") (pinfunction "8_8") (pintype "passive"))
    )
    (net (code "281") (name "unconnected-(P13-Pad11)") (class "Default")
      (node (ref "P13") (pin "11") (pinfunction "11_11") (pintype "passive"))
    )
    (net (code "282") (name "unconnected-(P13-Pad12)") (class "Default")
      (node (ref "P13") (pin "12") (pinfunction "12_12") (pintype "passive"))
    )
    (net (code "283") (name "unconnected-(P13-Pad16)") (class "Default")
      (node (ref "P13") (pin "16") (pinfunction "16_16") (pintype "passive"))
    )
    (net (code "284") (name "unconnected-(P14-Pad3)") (class "Default")
      (node (ref "P14") (pin "3") (pinfunction "3_3") (pintype "passive"))
    )
    (net (code "285") (name "unconnected-(P14-Pad4)") (class "Default")
      (node (ref "P14") (pin "4") (pinfunction "4_4") (pintype "passive"))
    )
    (net (code "286") (name "unconnected-(P14-Pad7)") (class "Default")
      (node (ref "P14") (pin "7") (pinfunction "7_7") (pintype "passive"))
    )
    (net (code "287") (name "unconnected-(P14-Pad8)") (class "Default")
      (node (ref "P14") (pin "8") (pinfunction "8_8") (pintype "passive"))
    )
    (net (code "288") (name "unconnected-(P14-Pad11)") (class "Default")
      (node (ref "P14") (pin "11") (pinfunction "11_11") (pintype "passive"))
    )
    (net (code "289") (name "unconnected-(P14-Pad12)") (class "Default")
      (node (ref "P14") (pin "12") (pinfunction "12_12") (pintype "passive"))
    )
    (net (code "290") (name "unconnected-(P14-Pad16)") (class "Default")
      (node (ref "P14") (pin "16") (pinfunction "16_16") (pintype "passive"))
    )
    (net (code "291") (name "unconnected-(P15-Pad3)") (class "Default")
      (node (ref "P15") (pin "3") (pinfunction "3_3") (pintype "passive"))
    )
    (net (code "292") (name "unconnected-(P15-Pad4)") (class "Default")
      (node (ref "P15") (pin "4") (pinfunction "4_4") (pintype "passive"))
    )
    (net (code "293") (name "unconnected-(P15-Pad7)") (class "Default")
      (node (ref "P15") (pin "7") (pinfunction "7_7") (pintype "passive"))
    )
    (net (code "294") (name "unconnected-(P15-Pad8)") (class "Default")
      (node (ref "P15") (pin "8") (pinfunction "8_8") (pintype "passive"))
    )
    (net (code "295") (name "unconnected-(P15-Pad11)") (class "Default")
      (node (ref "P15") (pin "11") (pinfunction "11_11") (pintype "passive"))
    )
    (net (code "296") (name "unconnected-(P15-Pad12)") (class "Default")
      (node (ref "P15") (pin "12") (pinfunction "12_12") (pintype "passive"))
    )
    (net (code "297") (name "unconnected-(P15-Pad16)") (class "Default")
      (node (ref "P15") (pin "16") (pinfunction "16_16") (pintype "passive"))
    )
    (net (code "298") (name "unconnected-(P16-Pad3)") (class "Default")
      (node (ref "P16") (pin "3") (pinfunction "3_3") (pintype "passive"))
    )
    (net (code "299") (name "unconnected-(P16-Pad4)") (class "Default")
      (node (ref "P16") (pin "4") (pinfunction "4_4") (pintype "passive"))
    )
    (net (code "300") (name "unconnected-(P16-Pad7)") (class "Default")
      (node (ref "P16") (pin "7") (pinfunction "7_7") (pintype "passive"))
    )
    (net (code "301") (name "unconnected-(P16-Pad8)") (class "Default")
      (node (ref "P16") (pin "8") (pinfunction "8_8") (pintype "passive"))
    )
    (net (code "302") (name "unconnected-(P16-Pad11)") (class "Default")
      (node (ref "P16") (pin "11") (pinfunction "11_11") (pintype "passive"))
    )
    (net (code "303") (name "unconnected-(P16-Pad12)") (class "Default")
      (node (ref "P16") (pin "12") (pinfunction "12_12") (pintype "passive"))
    )
    (net (code "304") (name "unconnected-(P16-Pad16)") (class "Default")
      (node (ref "P16") (pin "16") (pinfunction "16_16") (pintype "passive"))
    )
    (net (code "305") (name "unconnected-(P17-Pad3)") (class "Default")
      (node (ref "P17") (pin "3") (pinfunction "3_3") (pintype "passive"))
    )
    (net (code "306") (name "unconnected-(P17-Pad4)") (class "Default")
      (node (ref "P17") (pin "4") (pinfunction "4_4") (pintype "passive"))
    )
    (net (code "307") (name "unconnected-(P17-Pad7)") (class "Default")
      (node (ref "P17") (pin "7") (pinfunction "7_7") (pintype "passive"))
    )
    (net (code "308") (name "unconnected-(P17-Pad8)") (class "Default")
      (node (ref "P17") (pin "8") (pinfunction "8_8") (pintype "passive"))
    )
    (net (code "309") (name "unconnected-(P17-Pad11)") (class "Default")
      (node (ref "P17") (pin "11") (pinfunction "11_11") (pintype "passive"))
    )
    (net (code "310") (name "unconnected-(P17-Pad12)") (class "Default")
      (node (ref "P17") (pin "12") (pinfunction "12_12") (pintype "passive"))
    )
    (net (code "311") (name "unconnected-(P17-Pad16)") (class "Default")
      (node (ref "P17") (pin "16") (pinfunction "16_16") (pintype "passive"))
    )
    (net (code "312") (name "unconnected-(P18-Pad3)") (class "Default")
      (node (ref "P18") (pin "3") (pinfunction "3_3") (pintype "passive"))
    )
    (net (code "313") (name "unconnected-(P18-Pad4)") (class "Default")
      (node (ref "P18") (pin "4") (pinfunction "4_4") (pintype "passive"))
    )
    (net (code "314") (name "unconnected-(P18-Pad7)") (class "Default")
      (node (ref "P18") (pin "7") (pinfunction "7_7") (pintype "passive"))
    )
    (net (code "315") (name "unconnected-(P18-Pad8)") (class "Default")
      (node (ref "P18") (pin "8") (pinfunction "8_8") (pintype "passive"))
    )
    (net (code "316") (name "unconnected-(P18-Pad11)") (class "Default")
      (node (ref "P18") (pin "11") (pinfunction "11_11") (pintype "passive"))
    )
    (net (code "317") (name "unconnected-(P18-Pad12)") (class "Default")
      (node (ref "P18") (pin "12") (pinfunction "12_12") (pintype "passive"))
    )
    (net (code "318") (name "unconnected-(P18-Pad16)") (class "Default")
      (node (ref "P18") (pin "16") (pinfunction "16_16") (pintype "passive"))
    )
    (net (code "319") (name "unconnected-(P19-Pad3)") (class "Default")
      (node (ref "P19") (pin "3") (pinfunction "3_3") (pintype "passive"))
    )
    (net (code "320") (name "unconnected-(P19-Pad4)") (class "Default")
      (node (ref "P19") (pin "4") (pinfunction "4_4") (pintype "passive"))
    )
    (net (code "321") (name "unconnected-(P19-Pad7)") (class "Default")
      (node (ref "P19") (pin "7") (pinfunction "7_7") (pintype "passive"))
    )
    (net (code "322") (name "unconnected-(P19-Pad8)") (class "Default")
      (node (ref "P19") (pin "8") (pinfunction "8_8") (pintype "passive"))
    )
    (net (code "323") (name "unconnected-(P19-Pad11)") (class "Default")
      (node (ref "P19") (pin "11") (pinfunction "11_11") (pintype "passive"))
    )
    (net (code "324") (name "unconnected-(P19-Pad12)") (class "Default")
      (node (ref "P19") (pin "12") (pinfunction "12_12") (pintype "passive"))
    )
    (net (code "325") (name "unconnected-(P19-Pad16)") (class "Default")
      (node (ref "P19") (pin "16") (pinfunction "16_16") (pintype "passive"))
    )
    (net (code "326") (name "unconnected-(P20-Pad3)") (class "Default")
      (node (ref "P20") (pin "3") (pinfunction "3_3") (pintype "passive"))
    )
    (net (code "327") (name "unconnected-(P20-Pad4)") (class "Default")
      (node (ref "P20") (pin "4") (pinfunction "4_4") (pintype "passive"))
    )
    (net (code "328") (name "unconnected-(P20-Pad7)") (class "Default")
      (node (ref "P20") (pin "7") (pinfunction "7_7") (pintype "passive"))
    )
    (net (code "329") (name "unconnected-(P20-Pad8)") (class "Default")
      (node (ref "P20") (pin "8") (pinfunction "8_8") (pintype "passive"))
    )
    (net (code "330") (name "unconnected-(P20-Pad11)") (class "Default")
      (node (ref "P20") (pin "11") (pinfunction "11_11") (pintype "passive"))
    )
    (net (code "331") (name "unconnected-(P20-Pad12)") (class "Default")
      (node (ref "P20") (pin "12") (pinfunction "12_12") (pintype "passive"))
    )
    (net (code "332") (name "unconnected-(P20-Pad16)") (class "Default")
      (node (ref "P20") (pin "16") (pinfunction "16_16") (pintype "passive"))
    )
    (net (code "333") (name "unconnected-(P21-Pad3)") (class "Default")
      (node (ref "P21") (pin "3") (pinfunction "3_3") (pintype "passive"))
    )
    (net (code "334") (name "unconnected-(P21-Pad4)") (class "Default")
      (node (ref "P21") (pin "4") (pinfunction "4_4") (pintype "passive"))
    )
    (net (code "335") (name "unconnected-(P21-Pad7)") (class "Default")
      (node (ref "P21") (pin "7") (pinfunction "7_7") (pintype "passive"))
    )
    (net (code "336") (name "unconnected-(P21-Pad8)") (class "Default")
      (node (ref "P21") (pin "8") (pinfunction "8_8") (pintype "passive"))
    )
    (net (code "337") (name "unconnected-(P21-Pad11)") (class "Default")
      (node (ref "P21") (pin "11") (pinfunction "11_11") (pintype "passive"))
    )
    (net (code "338") (name "unconnected-(P21-Pad12)") (class "Default")
      (node (ref "P21") (pin "12") (pinfunction "12_12") (pintype "passive"))
    )
    (net (code "339") (name "unconnected-(P21-Pad16)") (class "Default")
      (node (ref "P21") (pin "16") (pinfunction "16_16") (pintype "passive"))
    )
    (net (code "340") (name "unconnected-(P22-Pad3)") (class "Default")
      (node (ref "P22") (pin "3") (pinfunction "3_3") (pintype "passive"))
    )
    (net (code "341") (name "unconnected-(P22-Pad4)") (class "Default")
      (node (ref "P22") (pin "4") (pinfunction "4_4") (pintype "passive"))
    )
    (net (code "342") (name "unconnected-(P22-Pad7)") (class "Default")
      (node (ref "P22") (pin "7") (pinfunction "7_7") (pintype "passive"))
    )
    (net (code "343") (name "unconnected-(P22-Pad8)") (class "Default")
      (node (ref "P22") (pin "8") (pinfunction "8_8") (pintype "passive"))
    )
    (net (code "344") (name "unconnected-(P22-Pad11)") (class "Default")
      (node (ref "P22") (pin "11") (pinfunction "11_11") (pintype "passive"))
    )
    (net (code "345") (name "unconnected-(P22-Pad12)") (class "Default")
      (node (ref "P22") (pin "12") (pinfunction "12_12") (pintype "passive"))
    )
    (net (code "346") (name "unconnected-(P22-Pad16)") (class "Default")
      (node (ref "P22") (pin "16") (pinfunction "16_16") (pintype "passive"))
    )
    (net (code "347") (name "unconnected-(P23-Pad3)") (class "Default")
      (node (ref "P23") (pin "3") (pinfunction "3_3") (pintype "passive"))
    )
    (net (code "348") (name "unconnected-(P23-Pad4)") (class "Default")
      (node (ref "P23") (pin "4") (pinfunction "4_4") (pintype "passive"))
    )
    (net (code "349") (name "unconnected-(P23-Pad7)") (class "Default")
      (node (ref "P23") (pin "7") (pinfunction "7_7") (pintype "passive"))
    )
    (net (code "350") (name "unconnected-(P23-Pad8)") (class "Default")
      (node (ref "P23") (pin "8") (pinfunction "8_8") (pintype "passive"))
    )
    (net (code "351") (name "unconnected-(P23-Pad11)") (class "Default")
      (node (ref "P23") (pin "11") (pinfunction "11_11") (pintype "passive"))
    )
    (net (code "352") (name "unconnected-(P23-Pad12)") (class "Default")
      (node (ref "P23") (pin "12") (pinfunction "12_12") (pintype "passive"))
    )
    (net (code "353") (name "unconnected-(P23-Pad16)") (class "Default")
      (node (ref "P23") (pin "16") (pinfunction "16_16") (pintype "passive"))
    )
    (net (code "354") (name "unconnected-(P24-Pad3)") (class "Default")
      (node (ref "P24") (pin "3") (pinfunction "3_3") (pintype "passive"))
    )
    (net (code "355") (name "unconnected-(P24-Pad4)") (class "Default")
      (node (ref "P24") (pin "4") (pinfunction "4_4") (pintype "passive"))
    )
    (net (code "356") (name "unconnected-(P24-Pad7)") (class "Default")
      (node (ref "P24") (pin "7") (pinfunction "7_7") (pintype "passive"))
    )
    (net (code "357") (name "unconnected-(P24-Pad8)") (class "Default")
      (node (ref "P24") (pin "8") (pinfunction "8_8") (pintype "passive"))
    )
    (net (code "358") (name "unconnected-(P24-Pad11)") (class "Default")
      (node (ref "P24") (pin "11") (pinfunction "11_11") (pintype "passive"))
    )
    (net (code "359") (name "unconnected-(P24-Pad12)") (class "Default")
      (node (ref "P24") (pin "12") (pinfunction "12_12") (pintype "passive"))
    )
    (net (code "360") (name "unconnected-(P24-Pad16)") (class "Default")
      (node (ref "P24") (pin "16") (pinfunction "16_16") (pintype "passive"))
    )
    (net (code "361") (name "unconnected-(U1-I2CSCL-Pad19)") (class "Default")
      (node (ref "U1") (pin "19") (pinfunction "I2CSCL_19") (pintype "passive"))
    )
    (net (code "362") (name "unconnected-(U1-I2CSDA-Pad18)") (class "Default")
      (node (ref "U1") (pin "18") (pinfunction "I2CSDA_18") (pintype "passive"))
    )
    (net (code "363") (name "unconnected-(U1-RSV-Pad1)") (class "Default")
      (node (ref "U1") (pin "1") (pinfunction "RSV_1") (pintype "passive"))
    )
    (net (code "364") (name "unconnected-(U1-RSV-Pad2)") (class "Default")
      (node (ref "U1") (pin "2") (pinfunction "RSV_2") (pintype "passive"))
    )
    (net (code "365") (name "unconnected-(U1-RSV-Pad3)") (class "Default")
      (node (ref "U1") (pin "3") (pinfunction "RSV_3") (pintype "passive"))
    )
    (net (code "366") (name "unconnected-(U1-RSV-Pad4)") (class "Default")
      (node (ref "U1") (pin "4") (pinfunction "RSV_4") (pintype "passive"))
    )
    (net (code "367") (name "unconnected-(U1-RSV-Pad5)") (class "Default")
      (node (ref "U1") (pin "5") (pinfunction "RSV_5") (pintype "passive"))
    )
    (net (code "368") (name "unconnected-(U1-RSV-Pad6)") (class "Default")
      (node (ref "U1") (pin "6") (pinfunction "RSV_6") (pintype "passive"))
    )
    (net (code "369") (name "unconnected-(U1-RSV-Pad7)") (class "Default")
      (node (ref "U1") (pin "7") (pinfunction "RSV_7") (pintype "passive"))
    )
    (net (code "370") (name "unconnected-(U1-RSV-Pad14)") (class "Default")
      (node (ref "U1") (pin "14") (pinfunction "RSV_14") (pintype "passive"))
    )
    (net (code "371") (name "unconnected-(U1-RSV-Pad15)") (class "Default")
      (node (ref "U1") (pin "15") (pinfunction "RSV_15") (pintype "passive"))
    )
    (net (code "372") (name "unconnected-(U1-RSV-Pad16)") (class "Default")
      (node (ref "U1") (pin "16") (pinfunction "RSV_16") (pintype "passive"))
    )
    (net (code "373") (name "unconnected-(U1-RSV-Pad17)") (class "Default")
      (node (ref "U1") (pin "17") (pinfunction "RSV_17") (pintype "passive"))
    )
    (net (code "374") (name "unconnected-(U2-I2CSCL-Pad19)") (class "Default")
      (node (ref "U2") (pin "19") (pinfunction "I2CSCL_19") (pintype "passive"))
    )
    (net (code "375") (name "unconnected-(U2-I2CSDA-Pad18)") (class "Default")
      (node (ref "U2") (pin "18") (pinfunction "I2CSDA_18") (pintype "passive"))
    )
    (net (code "376") (name "unconnected-(U2-RSV-Pad1)") (class "Default")
      (node (ref "U2") (pin "1") (pinfunction "RSV_1") (pintype "passive"))
    )
    (net (code "377") (name "unconnected-(U2-RSV-Pad2)") (class "Default")
      (node (ref "U2") (pin "2") (pinfunction "RSV_2") (pintype "passive"))
    )
    (net (code "378") (name "unconnected-(U2-RSV-Pad3)") (class "Default")
      (node (ref "U2") (pin "3") (pinfunction "RSV_3") (pintype "passive"))
    )
    (net (code "379") (name "unconnected-(U2-RSV-Pad4)") (class "Default")
      (node (ref "U2") (pin "4") (pinfunction "RSV_4") (pintype "passive"))
    )
    (net (code "380") (name "unconnected-(U2-RSV-Pad5)") (class "Default")
      (node (ref "U2") (pin "5") (pinfunction "RSV_5") (pintype "passive"))
    )
    (net (code "381") (name "unconnected-(U2-RSV-Pad6)") (class "Default")
      (node (ref "U2") (pin "6") (pinfunction "RSV_6") (pintype "passive"))
    )
    (net (code "382") (name "unconnected-(U2-RSV-Pad7)") (class "Default")
      (node (ref "U2") (pin "7") (pinfunction "RSV_7") (pintype "passive"))
    )
    (net (code "383") (name "unconnected-(U2-RSV-Pad14)") (class "Default")
      (node (ref "U2") (pin "14") (pinfunction "RSV_14") (pintype "passive"))
    )
    (net (code "384") (name "unconnected-(U2-RSV-Pad15)") (class "Default")
      (node (ref "U2") (pin "15") (pinfunction "RSV_15") (pintype "passive"))
    )
    (net (code "385") (name "unconnected-(U2-RSV-Pad16)") (class "Default")
      (node (ref "U2") (pin "16") (pinfunction "RSV_16") (pintype "passive"))
    )
    (net (code "386") (name "unconnected-(U2-RSV-Pad17)") (class "Default")
      (node (ref "U2") (pin "17") (pinfunction "RSV_17") (pintype "passive"))
    )
    (net (code "387") (name "unconnected-(U3-I2CSCL-Pad19)") (class "Default")
      (node (ref "U3") (pin "19") (pinfunction "I2CSCL_19") (pintype "passive"))
    )
    (net (code "388") (name "unconnected-(U3-I2CSDA-Pad18)") (class "Default")
      (node (ref "U3") (pin "18") (pinfunction "I2CSDA_18") (pintype "passive"))
    )
    (net (code "389") (name "unconnected-(U3-RSV-Pad1)") (class "Default")
      (node (ref "U3") (pin "1") (pinfunction "RSV_1") (pintype "passive"))
    )
    (net (code "390") (name "unconnected-(U3-RSV-Pad2)") (class "Default")
      (node (ref "U3") (pin "2") (pinfunction "RSV_2") (pintype "passive"))
    )
    (net (code "391") (name "unconnected-(U3-RSV-Pad3)") (class "Default")
      (node (ref "U3") (pin "3") (pinfunction "RSV_3") (pintype "passive"))
    )
    (net (code "392") (name "unconnected-(U3-RSV-Pad4)") (class "Default")
      (node (ref "U3") (pin "4") (pinfunction "RSV_4") (pintype "passive"))
    )
    (net (code "393") (name "unconnected-(U3-RSV-Pad5)") (class "Default")
      (node (ref "U3") (pin "5") (pinfunction "RSV_5") (pintype "passive"))
    )
    (net (code "394") (name "unconnected-(U3-RSV-Pad6)") (class "Default")
      (node (ref "U3") (pin "6") (pinfunction "RSV_6") (pintype "passive"))
    )
    (net (code "395") (name "unconnected-(U3-RSV-Pad7)") (class "Default")
      (node (ref "U3") (pin "7") (pinfunction "RSV_7") (pintype "passive"))
    )
    (net (code "396") (name "unconnected-(U3-RSV-Pad14)") (class "Default")
      (node (ref "U3") (pin "14") (pinfunction "RSV_14") (pintype "passive"))
    )
    (net (code "397") (name "unconnected-(U3-RSV-Pad15)") (class "Default")
      (node (ref "U3") (pin "15") (pinfunction "RSV_15") (pintype "passive"))
    )
    (net (code "398") (name "unconnected-(U3-RSV-Pad16)") (class "Default")
      (node (ref "U3") (pin "16") (pinfunction "RSV_16") (pintype "passive"))
    )
    (net (code "399") (name "unconnected-(U3-RSV-Pad17)") (class "Default")
      (node (ref "U3") (pin "17") (pinfunction "RSV_17") (pintype "passive"))
    )
    (net (code "400") (name "unconnected-(U4-I2CSCL-Pad19)") (class "Default")
      (node (ref "U4") (pin "19") (pinfunction "I2CSCL_19") (pintype "passive"))
    )
    (net (code "401") (name "unconnected-(U4-I2CSDA-Pad18)") (class "Default")
      (node (ref "U4") (pin "18") (pinfunction "I2CSDA_18") (pintype "passive"))
    )
    (net (code "402") (name "unconnected-(U4-RSV-Pad1)") (class "Default")
      (node (ref "U4") (pin "1") (pinfunction "RSV_1") (pintype "passive"))
    )
    (net (code "403") (name "unconnected-(U4-RSV-Pad2)") (class "Default")
      (node (ref "U4") (pin "2") (pinfunction "RSV_2") (pintype "passive"))
    )
    (net (code "404") (name "unconnected-(U4-RSV-Pad3)") (class "Default")
      (node (ref "U4") (pin "3") (pinfunction "RSV_3") (pintype "passive"))
    )
    (net (code "405") (name "unconnected-(U4-RSV-Pad4)") (class "Default")
      (node (ref "U4") (pin "4") (pinfunction "RSV_4") (pintype "passive"))
    )
    (net (code "406") (name "unconnected-(U4-RSV-Pad5)") (class "Default")
      (node (ref "U4") (pin "5") (pinfunction "RSV_5") (pintype "passive"))
    )
    (net (code "407") (name "unconnected-(U4-RSV-Pad6)") (class "Default")
      (node (ref "U4") (pin "6") (pinfunction "RSV_6") (pintype "passive"))
    )
    (net (code "408") (name "unconnected-(U4-RSV-Pad7)") (class "Default")
      (node (ref "U4") (pin "7") (pinfunction "RSV_7") (pintype "passive"))
    )
    (net (code "409") (name "unconnected-(U4-RSV-Pad14)") (class "Default")
      (node (ref "U4") (pin "14") (pinfunction "RSV_14") (pintype "passive"))
    )
    (net (code "410") (name "unconnected-(U4-RSV-Pad15)") (class "Default")
      (node (ref "U4") (pin "15") (pinfunction "RSV_15") (pintype "passive"))
    )
    (net (code "411") (name "unconnected-(U4-RSV-Pad16)") (class "Default")
      (node (ref "U4") (pin "16") (pinfunction "RSV_16") (pintype "passive"))
    )
    (net (code "412") (name "unconnected-(U4-RSV-Pad17)") (class "Default")
      (node (ref "U4") (pin "17") (pinfunction "RSV_17") (pintype "passive"))
    )
    (net (code "413") (name "unconnected-(U5-I2CSCL-Pad19)") (class "Default")
      (node (ref "U5") (pin "19") (pinfunction "I2CSCL_19") (pintype "passive"))
    )
    (net (code "414") (name "unconnected-(U5-I2CSDA-Pad18)") (class "Default")
      (node (ref "U5") (pin "18") (pinfunction "I2CSDA_18") (pintype "passive"))
    )
    (net (code "415") (name "unconnected-(U5-RSV-Pad1)") (class "Default")
      (node (ref "U5") (pin "1") (pinfunction "RSV_1") (pintype "passive"))
    )
    (net (code "416") (name "unconnected-(U5-RSV-Pad2)") (class "Default")
      (node (ref "U5") (pin "2") (pinfunction "RSV_2") (pintype "passive"))
    )
    (net (code "417") (name "unconnected-(U5-RSV-Pad3)") (class "Default")
      (node (ref "U5") (pin "3") (pinfunction "RSV_3") (pintype "passive"))
    )
    (net (code "418") (name "unconnected-(U5-RSV-Pad4)") (class "Default")
      (node (ref "U5") (pin "4") (pinfunction "RSV_4") (pintype "passive"))
    )
    (net (code "419") (name "unconnected-(U5-RSV-Pad5)") (class "Default")
      (node (ref "U5") (pin "5") (pinfunction "RSV_5") (pintype "passive"))
    )
    (net (code "420") (name "unconnected-(U5-RSV-Pad6)") (class "Default")
      (node (ref "U5") (pin "6") (pinfunction "RSV_6") (pintype "passive"))
    )
    (net (code "421") (name "unconnected-(U5-RSV-Pad7)") (class "Default")
      (node (ref "U5") (pin "7") (pinfunction "RSV_7") (pintype "passive"))
    )
    (net (code "422") (name "unconnected-(U5-RSV-Pad14)") (class "Default")
      (node (ref "U5") (pin "14") (pinfunction "RSV_14") (pintype "passive"))
    )
    (net (code "423") (name "unconnected-(U5-RSV-Pad15)") (class "Default")
      (node (ref "U5") (pin "15") (pinfunction "RSV_15") (pintype "passive"))
    )
    (net (code "424") (name "unconnected-(U5-RSV-Pad16)") (class "Default")
      (node (ref "U5") (pin "16") (pinfunction "RSV_16") (pintype "passive"))
    )
    (net (code "425") (name "unconnected-(U5-RSV-Pad17)") (class "Default")
      (node (ref "U5") (pin "17") (pinfunction "RSV_17") (pintype "passive"))
    )
    (net (code "426") (name "unconnected-(U6-I2CSCL-Pad19)") (class "Default")
      (node (ref "U6") (pin "19") (pinfunction "I2CSCL_19") (pintype "passive"))
    )
    (net (code "427") (name "unconnected-(U6-I2CSDA-Pad18)") (class "Default")
      (node (ref "U6") (pin "18") (pinfunction "I2CSDA_18") (pintype "passive"))
    )
    (net (code "428") (name "unconnected-(U6-RSV-Pad1)") (class "Default")
      (node (ref "U6") (pin "1") (pinfunction "RSV_1") (pintype "passive"))
    )
    (net (code "429") (name "unconnected-(U6-RSV-Pad2)") (class "Default")
      (node (ref "U6") (pin "2") (pinfunction "RSV_2") (pintype "passive"))
    )
    (net (code "430") (name "unconnected-(U6-RSV-Pad3)") (class "Default")
      (node (ref "U6") (pin "3") (pinfunction "RSV_3") (pintype "passive"))
    )
    (net (code "431") (name "unconnected-(U6-RSV-Pad4)") (class "Default")
      (node (ref "U6") (pin "4") (pinfunction "RSV_4") (pintype "passive"))
    )
    (net (code "432") (name "unconnected-(U6-RSV-Pad5)") (class "Default")
      (node (ref "U6") (pin "5") (pinfunction "RSV_5") (pintype "passive"))
    )
    (net (code "433") (name "unconnected-(U6-RSV-Pad6)") (class "Default")
      (node (ref "U6") (pin "6") (pinfunction "RSV_6") (pintype "passive"))
    )
    (net (code "434") (name "unconnected-(U6-RSV-Pad7)") (class "Default")
      (node (ref "U6") (pin "7") (pinfunction "RSV_7") (pintype "passive"))
    )
    (net (code "435") (name "unconnected-(U6-RSV-Pad14)") (class "Default")
      (node (ref "U6") (pin "14") (pinfunction "RSV_14") (pintype "passive"))
    )
    (net (code "436") (name "unconnected-(U6-RSV-Pad15)") (class "Default")
      (node (ref "U6") (pin "15") (pinfunction "RSV_15") (pintype "passive"))
    )
    (net (code "437") (name "unconnected-(U6-RSV-Pad16)") (class "Default")
      (node (ref "U6") (pin "16") (pinfunction "RSV_16") (pintype "passive"))
    )
    (net (code "438") (name "unconnected-(U6-RSV-Pad17)") (class "Default")
      (node (ref "U6") (pin "17") (pinfunction "RSV_17") (pintype "passive"))
    )
    (net (code "439") (name "unconnected-(U7-I2CSCL-Pad19)") (class "Default")
      (node (ref "U7") (pin "19") (pinfunction "I2CSCL_19") (pintype "passive"))
    )
    (net (code "440") (name "unconnected-(U7-I2CSDA-Pad18)") (class "Default")
      (node (ref "U7") (pin "18") (pinfunction "I2CSDA_18") (pintype "passive"))
    )
    (net (code "441") (name "unconnected-(U7-RSV-Pad1)") (class "Default")
      (node (ref "U7") (pin "1") (pinfunction "RSV_1") (pintype "passive"))
    )
    (net (code "442") (name "unconnected-(U7-RSV-Pad2)") (class "Default")
      (node (ref "U7") (pin "2") (pinfunction "RSV_2") (pintype "passive"))
    )
    (net (code "443") (name "unconnected-(U7-RSV-Pad3)") (class "Default")
      (node (ref "U7") (pin "3") (pinfunction "RSV_3") (pintype "passive"))
    )
    (net (code "444") (name "unconnected-(U7-RSV-Pad4)") (class "Default")
      (node (ref "U7") (pin "4") (pinfunction "RSV_4") (pintype "passive"))
    )
    (net (code "445") (name "unconnected-(U7-RSV-Pad5)") (class "Default")
      (node (ref "U7") (pin "5") (pinfunction "RSV_5") (pintype "passive"))
    )
    (net (code "446") (name "unconnected-(U7-RSV-Pad6)") (class "Default")
      (node (ref "U7") (pin "6") (pinfunction "RSV_6") (pintype "passive"))
    )
    (net (code "447") (name "unconnected-(U7-RSV-Pad7)") (class "Default")
      (node (ref "U7") (pin "7") (pinfunction "RSV_7") (pintype "passive"))
    )
    (net (code "448") (name "unconnected-(U7-RSV-Pad14)") (class "Default")
      (node (ref "U7") (pin "14") (pinfunction "RSV_14") (pintype "passive"))
    )
    (net (code "449") (name "unconnected-(U7-RSV-Pad15)") (class "Default")
      (node (ref "U7") (pin "15") (pinfunction "RSV_15") (pintype "passive"))
    )
    (net (code "450") (name "unconnected-(U7-RSV-Pad16)") (class "Default")
      (node (ref "U7") (pin "16") (pinfunction "RSV_16") (pintype "passive"))
    )
    (net (code "451") (name "unconnected-(U7-RSV-Pad17)") (class "Default")
      (node (ref "U7") (pin "17") (pinfunction "RSV_17") (pintype "passive"))
    )
    (net (code "452") (name "unconnected-(U8-I2CSCL-Pad19)") (class "Default")
      (node (ref "U8") (pin "19") (pinfunction "I2CSCL_19") (pintype "passive"))
    )
    (net (code "453") (name "unconnected-(U8-I2CSDA-Pad18)") (class "Default")
      (node (ref "U8") (pin "18") (pinfunction "I2CSDA_18") (pintype "passive"))
    )
    (net (code "454") (name "unconnected-(U8-RSV-Pad1)") (class "Default")
      (node (ref "U8") (pin "1") (pinfunction "RSV_1") (pintype "passive"))
    )
    (net (code "455") (name "unconnected-(U8-RSV-Pad2)") (class "Default")
      (node (ref "U8") (pin "2") (pinfunction "RSV_2") (pintype "passive"))
    )
    (net (code "456") (name "unconnected-(U8-RSV-Pad3)") (class "Default")
      (node (ref "U8") (pin "3") (pinfunction "RSV_3") (pintype "passive"))
    )
    (net (code "457") (name "unconnected-(U8-RSV-Pad4)") (class "Default")
      (node (ref "U8") (pin "4") (pinfunction "RSV_4") (pintype "passive"))
    )
    (net (code "458") (name "unconnected-(U8-RSV-Pad5)") (class "Default")
      (node (ref "U8") (pin "5") (pinfunction "RSV_5") (pintype "passive"))
    )
    (net (code "459") (name "unconnected-(U8-RSV-Pad6)") (class "Default")
      (node (ref "U8") (pin "6") (pinfunction "RSV_6") (pintype "passive"))
    )
    (net (code "460") (name "unconnected-(U8-RSV-Pad7)") (class "Default")
      (node (ref "U8") (pin "7") (pinfunction "RSV_7") (pintype "passive"))
    )
    (net (code "461") (name "unconnected-(U8-RSV-Pad14)") (class "Default")
      (node (ref "U8") (pin "14") (pinfunction "RSV_14") (pintype "passive"))
    )
    (net (code "462") (name "unconnected-(U8-RSV-Pad15)") (class "Default")
      (node (ref "U8") (pin "15") (pinfunction "RSV_15") (pintype "passive"))
    )
    (net (code "463") (name "unconnected-(U8-RSV-Pad16)") (class "Default")
      (node (ref "U8") (pin "16") (pinfunction "RSV_16") (pintype "passive"))
    )
    (net (code "464") (name "unconnected-(U8-RSV-Pad17)") (class "Default")
      (node (ref "U8") (pin "17") (pinfunction "RSV_17") (pintype "passive"))
    )
    (net (code "465") (name "unconnected-(U9-I2CSCL-Pad19)") (class "Default")
      (node (ref "U9") (pin "19") (pinfunction "I2CSCL_19") (pintype "passive"))
    )
    (net (code "466") (name "unconnected-(U9-I2CSDA-Pad18)") (class "Default")
      (node (ref "U9") (pin "18") (pinfunction "I2CSDA_18") (pintype "passive"))
    )
    (net (code "467") (name "unconnected-(U9-RSV-Pad1)") (class "Default")
      (node (ref "U9") (pin "1") (pinfunction "RSV_1") (pintype "passive"))
    )
    (net (code "468") (name "unconnected-(U9-RSV-Pad2)") (class "Default")
      (node (ref "U9") (pin "2") (pinfunction "RSV_2") (pintype "passive"))
    )
    (net (code "469") (name "unconnected-(U9-RSV-Pad3)") (class "Default")
      (node (ref "U9") (pin "3") (pinfunction "RSV_3") (pintype "passive"))
    )
    (net (code "470") (name "unconnected-(U9-RSV-Pad4)") (class "Default")
      (node (ref "U9") (pin "4") (pinfunction "RSV_4") (pintype "passive"))
    )
    (net (code "471") (name "unconnected-(U9-RSV-Pad5)") (class "Default")
      (node (ref "U9") (pin "5") (pinfunction "RSV_5") (pintype "passive"))
    )
    (net (code "472") (name "unconnected-(U9-RSV-Pad6)") (class "Default")
      (node (ref "U9") (pin "6") (pinfunction "RSV_6") (pintype "passive"))
    )
    (net (code "473") (name "unconnected-(U9-RSV-Pad7)") (class "Default")
      (node (ref "U9") (pin "7") (pinfunction "RSV_7") (pintype "passive"))
    )
    (net (code "474") (name "unconnected-(U9-RSV-Pad14)") (class "Default")
      (node (ref "U9") (pin "14") (pinfunction "RSV_14") (pintype "passive"))
    )
    (net (code "475") (name "unconnected-(U9-RSV-Pad15)") (class "Default")
      (node (ref "U9") (pin "15") (pinfunction "RSV_15") (pintype "passive"))
    )
    (net (code "476") (name "unconnected-(U9-RSV-Pad16)") (class "Default")
      (node (ref "U9") (pin "16") (pinfunction "RSV_16") (pintype "passive"))
    )
    (net (code "477") (name "unconnected-(U9-RSV-Pad17)") (class "Default")
      (node (ref "U9") (pin "17") (pinfunction "RSV_17") (pintype "passive"))
    )
    (net (code "478") (name "unconnected-(U10-I2CSCL-Pad19)") (class "Default")
      (node (ref "U10") (pin "19") (pinfunction "I2CSCL_19") (pintype "passive"))
    )
    (net (code "479") (name "unconnected-(U10-I2CSDA-Pad18)") (class "Default")
      (node (ref "U10") (pin "18") (pinfunction "I2CSDA_18") (pintype "passive"))
    )
    (net (code "480") (name "unconnected-(U10-RSV-Pad1)") (class "Default")
      (node (ref "U10") (pin "1") (pinfunction "RSV_1") (pintype "passive"))
    )
    (net (code "481") (name "unconnected-(U10-RSV-Pad2)") (class "Default")
      (node (ref "U10") (pin "2") (pinfunction "RSV_2") (pintype "passive"))
    )
    (net (code "482") (name "unconnected-(U10-RSV-Pad3)") (class "Default")
      (node (ref "U10") (pin "3") (pinfunction "RSV_3") (pintype "passive"))
    )
    (net (code "483") (name "unconnected-(U10-RSV-Pad4)") (class "Default")
      (node (ref "U10") (pin "4") (pinfunction "RSV_4") (pintype "passive"))
    )
    (net (code "484") (name "unconnected-(U10-RSV-Pad5)") (class "Default")
      (node (ref "U10") (pin "5") (pinfunction "RSV_5") (pintype "passive"))
    )
    (net (code "485") (name "unconnected-(U10-RSV-Pad6)") (class "Default")
      (node (ref "U10") (pin "6") (pinfunction "RSV_6") (pintype "passive"))
    )
    (net (code "486") (name "unconnected-(U10-RSV-Pad7)") (class "Default")
      (node (ref "U10") (pin "7") (pinfunction "RSV_7") (pintype "passive"))
    )
    (net (code "487") (name "unconnected-(U10-RSV-Pad14)") (class "Default")
      (node (ref "U10") (pin "14") (pinfunction "RSV_14") (pintype "passive"))
    )
    (net (code "488") (name "unconnected-(U10-RSV-Pad15)") (class "Default")
      (node (ref "U10") (pin "15") (pinfunction "RSV_15") (pintype "passive"))
    )
    (net (code "489") (name "unconnected-(U10-RSV-Pad16)") (class "Default")
      (node (ref "U10") (pin "16") (pinfunction "RSV_16") (pintype "passive"))
    )
    (net (code "490") (name "unconnected-(U10-RSV-Pad17)") (class "Default")
      (node (ref "U10") (pin "17") (pinfunction "RSV_17") (pintype "passive"))
    )
    (net (code "491") (name "unconnected-(U11-I2CSCL-Pad19)") (class "Default")
      (node (ref "U11") (pin "19") (pinfunction "I2CSCL_19") (pintype "passive"))
    )
    (net (code "492") (name "unconnected-(U11-I2CSDA-Pad18)") (class "Default")
      (node (ref "U11") (pin "18") (pinfunction "I2CSDA_18") (pintype "passive"))
    )
    (net (code "493") (name "unconnected-(U11-RSV-Pad1)") (class "Default")
      (node (ref "U11") (pin "1") (pinfunction "RSV_1") (pintype "passive"))
    )
    (net (code "494") (name "unconnected-(U11-RSV-Pad2)") (class "Default")
      (node (ref "U11") (pin "2") (pinfunction "RSV_2") (pintype "passive"))
    )
    (net (code "495") (name "unconnected-(U11-RSV-Pad3)") (class "Default")
      (node (ref "U11") (pin "3") (pinfunction "RSV_3") (pintype "passive"))
    )
    (net (code "496") (name "unconnected-(U11-RSV-Pad4)") (class "Default")
      (node (ref "U11") (pin "4") (pinfunction "RSV_4") (pintype "passive"))
    )
    (net (code "497") (name "unconnected-(U11-RSV-Pad5)") (class "Default")
      (node (ref "U11") (pin "5") (pinfunction "RSV_5") (pintype "passive"))
    )
    (net (code "498") (name "unconnected-(U11-RSV-Pad6)") (class "Default")
      (node (ref "U11") (pin "6") (pinfunction "RSV_6") (pintype "passive"))
    )
    (net (code "499") (name "unconnected-(U11-RSV-Pad7)") (class "Default")
      (node (ref "U11") (pin "7") (pinfunction "RSV_7") (pintype "passive"))
    )
    (net (code "500") (name "unconnected-(U11-RSV-Pad14)") (class "Default")
      (node (ref "U11") (pin "14") (pinfunction "RSV_14") (pintype "passive"))
    )
    (net (code "501") (name "unconnected-(U11-RSV-Pad15)") (class "Default")
      (node (ref "U11") (pin "15") (pinfunction "RSV_15") (pintype "passive"))
    )
    (net (code "502") (name "unconnected-(U11-RSV-Pad16)") (class "Default")
      (node (ref "U11") (pin "16") (pinfunction "RSV_16") (pintype "passive"))
    )
    (net (code "503") (name "unconnected-(U11-RSV-Pad17)") (class "Default")
      (node (ref "U11") (pin "17") (pinfunction "RSV_17") (pintype "passive"))
    )
    (net (code "504") (name "unconnected-(U12-I2CSCL-Pad19)") (class "Default")
      (node (ref "U12") (pin "19") (pinfunction "I2CSCL_19") (pintype "passive"))
    )
    (net (code "505") (name "unconnected-(U12-I2CSDA-Pad18)") (class "Default")
      (node (ref "U12") (pin "18") (pinfunction "I2CSDA_18") (pintype "passive"))
    )
    (net (code "506") (name "unconnected-(U12-RSV-Pad1)") (class "Default")
      (node (ref "U12") (pin "1") (pinfunction "RSV_1") (pintype "passive"))
    )
    (net (code "507") (name "unconnected-(U12-RSV-Pad2)") (class "Default")
      (node (ref "U12") (pin "2") (pinfunction "RSV_2") (pintype "passive"))
    )
    (net (code "508") (name "unconnected-(U12-RSV-Pad3)") (class "Default")
      (node (ref "U12") (pin "3") (pinfunction "RSV_3") (pintype "passive"))
    )
    (net (code "509") (name "unconnected-(U12-RSV-Pad4)") (class "Default")
      (node (ref "U12") (pin "4") (pinfunction "RSV_4") (pintype "passive"))
    )
    (net (code "510") (name "unconnected-(U12-RSV-Pad5)") (class "Default")
      (node (ref "U12") (pin "5") (pinfunction "RSV_5") (pintype "passive"))
    )
    (net (code "511") (name "unconnected-(U12-RSV-Pad6)") (class "Default")
      (node (ref "U12") (pin "6") (pinfunction "RSV_6") (pintype "passive"))
    )
    (net (code "512") (name "unconnected-(U12-RSV-Pad7)") (class "Default")
      (node (ref "U12") (pin "7") (pinfunction "RSV_7") (pintype "passive"))
    )
    (net (code "513") (name "unconnected-(U12-RSV-Pad14)") (class "Default")
      (node (ref "U12") (pin "14") (pinfunction "RSV_14") (pintype "passive"))
    )
    (net (code "514") (name "unconnected-(U12-RSV-Pad15)") (class "Default")
      (node (ref "U12") (pin "15") (pinfunction "RSV_15") (pintype "passive"))
    )
    (net (code "515") (name "unconnected-(U12-RSV-Pad16)") (class "Default")
      (node (ref "U12") (pin "16") (pinfunction "RSV_16") (pintype "passive"))
    )
    (net (code "516") (name "unconnected-(U12-RSV-Pad17)") (class "Default")
      (node (ref "U12") (pin "17") (pinfunction "RSV_17") (pintype "passive"))
    )
    (net (code "517") (name "unconnected-(U13-I2CSCL-Pad19)") (class "Default")
      (node (ref "U13") (pin "19") (pinfunction "I2CSCL_19") (pintype "passive"))
    )
    (net (code "518") (name "unconnected-(U13-I2CSDA-Pad18)") (class "Default")
      (node (ref "U13") (pin "18") (pinfunction "I2CSDA_18") (pintype "passive"))
    )
    (net (code "519") (name "unconnected-(U13-RSV-Pad1)") (class "Default")
      (node (ref "U13") (pin "1") (pinfunction "RSV_1") (pintype "passive"))
    )
    (net (code "520") (name "unconnected-(U13-RSV-Pad2)") (class "Default")
      (node (ref "U13") (pin "2") (pinfunction "RSV_2") (pintype "passive"))
    )
    (net (code "521") (name "unconnected-(U13-RSV-Pad3)") (class "Default")
      (node (ref "U13") (pin "3") (pinfunction "RSV_3") (pintype "passive"))
    )
    (net (code "522") (name "unconnected-(U13-RSV-Pad4)") (class "Default")
      (node (ref "U13") (pin "4") (pinfunction "RSV_4") (pintype "passive"))
    )
    (net (code "523") (name "unconnected-(U13-RSV-Pad5)") (class "Default")
      (node (ref "U13") (pin "5") (pinfunction "RSV_5") (pintype "passive"))
    )
    (net (code "524") (name "unconnected-(U13-RSV-Pad6)") (class "Default")
      (node (ref "U13") (pin "6") (pinfunction "RSV_6") (pintype "passive"))
    )
    (net (code "525") (name "unconnected-(U13-RSV-Pad7)") (class "Default")
      (node (ref "U13") (pin "7") (pinfunction "RSV_7") (pintype "passive"))
    )
    (net (code "526") (name "unconnected-(U13-RSV-Pad14)") (class "Default")
      (node (ref "U13") (pin "14") (pinfunction "RSV_14") (pintype "passive"))
    )
    (net (code "527") (name "unconnected-(U13-RSV-Pad15)") (class "Default")
      (node (ref "U13") (pin "15") (pinfunction "RSV_15") (pintype "passive"))
    )
    (net (code "528") (name "unconnected-(U13-RSV-Pad16)") (class "Default")
      (node (ref "U13") (pin "16") (pinfunction "RSV_16") (pintype "passive"))
    )
    (net (code "529") (name "unconnected-(U13-RSV-Pad17)") (class "Default")
      (node (ref "U13") (pin "17") (pinfunction "RSV_17") (pintype "passive"))
    )
    (net (code "530") (name "unconnected-(U14-I2CSCL-Pad19)") (class "Default")
      (node (ref "U14") (pin "19") (pinfunction "I2CSCL_19") (pintype "passive"))
    )
    (net (code "531") (name "unconnected-(U14-I2CSDA-Pad18)") (class "Default")
      (node (ref "U14") (pin "18") (pinfunction "I2CSDA_18") (pintype "passive"))
    )
    (net (code "532") (name "unconnected-(U14-RSV-Pad1)") (class "Default")
      (node (ref "U14") (pin "1") (pinfunction "RSV_1") (pintype "passive"))
    )
    (net (code "533") (name "unconnected-(U14-RSV-Pad2)") (class "Default")
      (node (ref "U14") (pin "2") (pinfunction "RSV_2") (pintype "passive"))
    )
    (net (code "534") (name "unconnected-(U14-RSV-Pad3)") (class "Default")
      (node (ref "U14") (pin "3") (pinfunction "RSV_3") (pintype "passive"))
    )
    (net (code "535") (name "unconnected-(U14-RSV-Pad4)") (class "Default")
      (node (ref "U14") (pin "4") (pinfunction "RSV_4") (pintype "passive"))
    )
    (net (code "536") (name "unconnected-(U14-RSV-Pad5)") (class "Default")
      (node (ref "U14") (pin "5") (pinfunction "RSV_5") (pintype "passive"))
    )
    (net (code "537") (name "unconnected-(U14-RSV-Pad6)") (class "Default")
      (node (ref "U14") (pin "6") (pinfunction "RSV_6") (pintype "passive"))
    )
    (net (code "538") (name "unconnected-(U14-RSV-Pad7)") (class "Default")
      (node (ref "U14") (pin "7") (pinfunction "RSV_7") (pintype "passive"))
    )
    (net (code "539") (name "unconnected-(U14-RSV-Pad14)") (class "Default")
      (node (ref "U14") (pin "14") (pinfunction "RSV_14") (pintype "passive"))
    )
    (net (code "540") (name "unconnected-(U14-RSV-Pad15)") (class "Default")
      (node (ref "U14") (pin "15") (pinfunction "RSV_15") (pintype "passive"))
    )
    (net (code "541") (name "unconnected-(U14-RSV-Pad16)") (class "Default")
      (node (ref "U14") (pin "16") (pinfunction "RSV_16") (pintype "passive"))
    )
    (net (code "542") (name "unconnected-(U14-RSV-Pad17)") (class "Default")
      (node (ref "U14") (pin "17") (pinfunction "RSV_17") (pintype "passive"))
    )
    (net (code "543") (name "unconnected-(U15-I2CSCL-Pad19)") (class "Default")
      (node (ref "U15") (pin "19") (pinfunction "I2CSCL_19") (pintype "passive"))
    )
    (net (code "544") (name "unconnected-(U15-I2CSDA-Pad18)") (class "Default")
      (node (ref "U15") (pin "18") (pinfunction "I2CSDA_18") (pintype "passive"))
    )
    (net (code "545") (name "unconnected-(U15-RSV-Pad1)") (class "Default")
      (node (ref "U15") (pin "1") (pinfunction "RSV_1") (pintype "passive"))
    )
    (net (code "546") (name "unconnected-(U15-RSV-Pad2)") (class "Default")
      (node (ref "U15") (pin "2") (pinfunction "RSV_2") (pintype "passive"))
    )
    (net (code "547") (name "unconnected-(U15-RSV-Pad3)") (class "Default")
      (node (ref "U15") (pin "3") (pinfunction "RSV_3") (pintype "passive"))
    )
    (net (code "548") (name "unconnected-(U15-RSV-Pad4)") (class "Default")
      (node (ref "U15") (pin "4") (pinfunction "RSV_4") (pintype "passive"))
    )
    (net (code "549") (name "unconnected-(U15-RSV-Pad5)") (class "Default")
      (node (ref "U15") (pin "5") (pinfunction "RSV_5") (pintype "passive"))
    )
    (net (code "550") (name "unconnected-(U15-RSV-Pad6)") (class "Default")
      (node (ref "U15") (pin "6") (pinfunction "RSV_6") (pintype "passive"))
    )
    (net (code "551") (name "unconnected-(U15-RSV-Pad7)") (class "Default")
      (node (ref "U15") (pin "7") (pinfunction "RSV_7") (pintype "passive"))
    )
    (net (code "552") (name "unconnected-(U15-RSV-Pad14)") (class "Default")
      (node (ref "U15") (pin "14") (pinfunction "RSV_14") (pintype "passive"))
    )
    (net (code "553") (name "unconnected-(U15-RSV-Pad15)") (class "Default")
      (node (ref "U15") (pin "15") (pinfunction "RSV_15") (pintype "passive"))
    )
    (net (code "554") (name "unconnected-(U15-RSV-Pad16)") (class "Default")
      (node (ref "U15") (pin "16") (pinfunction "RSV_16") (pintype "passive"))
    )
    (net (code "555") (name "unconnected-(U15-RSV-Pad17)") (class "Default")
      (node (ref "U15") (pin "17") (pinfunction "RSV_17") (pintype "passive"))
    )
    (net (code "556") (name "unconnected-(U16-I2CSCL-Pad19)") (class "Default")
      (node (ref "U16") (pin "19") (pinfunction "I2CSCL_19") (pintype "passive"))
    )
    (net (code "557") (name "unconnected-(U16-I2CSDA-Pad18)") (class "Default")
      (node (ref "U16") (pin "18") (pinfunction "I2CSDA_18") (pintype "passive"))
    )
    (net (code "558") (name "unconnected-(U16-RSV-Pad1)") (class "Default")
      (node (ref "U16") (pin "1") (pinfunction "RSV_1") (pintype "passive"))
    )
    (net (code "559") (name "unconnected-(U16-RSV-Pad2)") (class "Default")
      (node (ref "U16") (pin "2") (pinfunction "RSV_2") (pintype "passive"))
    )
    (net (code "560") (name "unconnected-(U16-RSV-Pad3)") (class "Default")
      (node (ref "U16") (pin "3") (pinfunction "RSV_3") (pintype "passive"))
    )
    (net (code "561") (name "unconnected-(U16-RSV-Pad4)") (class "Default")
      (node (ref "U16") (pin "4") (pinfunction "RSV_4") (pintype "passive"))
    )
    (net (code "562") (name "unconnected-(U16-RSV-Pad5)") (class "Default")
      (node (ref "U16") (pin "5") (pinfunction "RSV_5") (pintype "passive"))
    )
    (net (code "563") (name "unconnected-(U16-RSV-Pad6)") (class "Default")
      (node (ref "U16") (pin "6") (pinfunction "RSV_6") (pintype "passive"))
    )
    (net (code "564") (name "unconnected-(U16-RSV-Pad7)") (class "Default")
      (node (ref "U16") (pin "7") (pinfunction "RSV_7") (pintype "passive"))
    )
    (net (code "565") (name "unconnected-(U16-RSV-Pad14)") (class "Default")
      (node (ref "U16") (pin "14") (pinfunction "RSV_14") (pintype "passive"))
    )
    (net (code "566") (name "unconnected-(U16-RSV-Pad15)") (class "Default")
      (node (ref "U16") (pin "15") (pinfunction "RSV_15") (pintype "passive"))
    )
    (net (code "567") (name "unconnected-(U16-RSV-Pad16)") (class "Default")
      (node (ref "U16") (pin "16") (pinfunction "RSV_16") (pintype "passive"))
    )
    (net (code "568") (name "unconnected-(U16-RSV-Pad17)") (class "Default")
      (node (ref "U16") (pin "17") (pinfunction "RSV_17") (pintype "passive"))
    )
    (net (code "569") (name "unconnected-(U17-I2CSCL-Pad19)") (class "Default")
      (node (ref "U17") (pin "19") (pinfunction "I2CSCL_19") (pintype "passive"))
    )
    (net (code "570") (name "unconnected-(U17-I2CSDA-Pad18)") (class "Default")
      (node (ref "U17") (pin "18") (pinfunction "I2CSDA_18") (pintype "passive"))
    )
    (net (code "571") (name "unconnected-(U17-RSV-Pad1)") (class "Default")
      (node (ref "U17") (pin "1") (pinfunction "RSV_1") (pintype "passive"))
    )
    (net (code "572") (name "unconnected-(U17-RSV-Pad2)") (class "Default")
      (node (ref "U17") (pin "2") (pinfunction "RSV_2") (pintype "passive"))
    )
    (net (code "573") (name "unconnected-(U17-RSV-Pad3)") (class "Default")
      (node (ref "U17") (pin "3") (pinfunction "RSV_3") (pintype "passive"))
    )
    (net (code "574") (name "unconnected-(U17-RSV-Pad4)") (class "Default")
      (node (ref "U17") (pin "4") (pinfunction "RSV_4") (pintype "passive"))
    )
    (net (code "575") (name "unconnected-(U17-RSV-Pad5)") (class "Default")
      (node (ref "U17") (pin "5") (pinfunction "RSV_5") (pintype "passive"))
    )
    (net (code "576") (name "unconnected-(U17-RSV-Pad6)") (class "Default")
      (node (ref "U17") (pin "6") (pinfunction "RSV_6") (pintype "passive"))
    )
    (net (code "577") (name "unconnected-(U17-RSV-Pad7)") (class "Default")
      (node (ref "U17") (pin "7") (pinfunction "RSV_7") (pintype "passive"))
    )
    (net (code "578") (name "unconnected-(U17-RSV-Pad14)") (class "Default")
      (node (ref "U17") (pin "14") (pinfunction "RSV_14") (pintype "passive"))
    )
    (net (code "579") (name "unconnected-(U17-RSV-Pad15)") (class "Default")
      (node (ref "U17") (pin "15") (pinfunction "RSV_15") (pintype "passive"))
    )
    (net (code "580") (name "unconnected-(U17-RSV-Pad16)") (class "Default")
      (node (ref "U17") (pin "16") (pinfunction "RSV_16") (pintype "passive"))
    )
    (net (code "581") (name "unconnected-(U17-RSV-Pad17)") (class "Default")
      (node (ref "U17") (pin "17") (pinfunction "RSV_17") (pintype "passive"))
    )
    (net (code "582") (name "unconnected-(U18-I2CSCL-Pad19)") (class "Default")
      (node (ref "U18") (pin "19") (pinfunction "I2CSCL_19") (pintype "passive"))
    )
    (net (code "583") (name "unconnected-(U18-I2CSDA-Pad18)") (class "Default")
      (node (ref "U18") (pin "18") (pinfunction "I2CSDA_18") (pintype "passive"))
    )
    (net (code "584") (name "unconnected-(U18-RSV-Pad1)") (class "Default")
      (node (ref "U18") (pin "1") (pinfunction "RSV_1") (pintype "passive"))
    )
    (net (code "585") (name "unconnected-(U18-RSV-Pad2)") (class "Default")
      (node (ref "U18") (pin "2") (pinfunction "RSV_2") (pintype "passive"))
    )
    (net (code "586") (name "unconnected-(U18-RSV-Pad3)") (class "Default")
      (node (ref "U18") (pin "3") (pinfunction "RSV_3") (pintype "passive"))
    )
    (net (code "587") (name "unconnected-(U18-RSV-Pad4)") (class "Default")
      (node (ref "U18") (pin "4") (pinfunction "RSV_4") (pintype "passive"))
    )
    (net (code "588") (name "unconnected-(U18-RSV-Pad5)") (class "Default")
      (node (ref "U18") (pin "5") (pinfunction "RSV_5") (pintype "passive"))
    )
    (net (code "589") (name "unconnected-(U18-RSV-Pad6)") (class "Default")
      (node (ref "U18") (pin "6") (pinfunction "RSV_6") (pintype "passive"))
    )
    (net (code "590") (name "unconnected-(U18-RSV-Pad7)") (class "Default")
      (node (ref "U18") (pin "7") (pinfunction "RSV_7") (pintype "passive"))
    )
    (net (code "591") (name "unconnected-(U18-RSV-Pad14)") (class "Default")
      (node (ref "U18") (pin "14") (pinfunction "RSV_14") (pintype "passive"))
    )
    (net (code "592") (name "unconnected-(U18-RSV-Pad15)") (class "Default")
      (node (ref "U18") (pin "15") (pinfunction "RSV_15") (pintype "passive"))
    )
    (net (code "593") (name "unconnected-(U18-RSV-Pad16)") (class "Default")
      (node (ref "U18") (pin "16") (pinfunction "RSV_16") (pintype "passive"))
    )
    (net (code "594") (name "unconnected-(U18-RSV-Pad17)") (class "Default")
      (node (ref "U18") (pin "17") (pinfunction "RSV_17") (pintype "passive"))
    )
    (net (code "595") (name "unconnected-(U19-I2CSCL-Pad19)") (class "Default")
      (node (ref "U19") (pin "19") (pinfunction "I2CSCL_19") (pintype "passive"))
    )
    (net (code "596") (name "unconnected-(U19-I2CSDA-Pad18)") (class "Default")
      (node (ref "U19") (pin "18") (pinfunction "I2CSDA_18") (pintype "passive"))
    )
    (net (code "597") (name "unconnected-(U19-RSV-Pad1)") (class "Default")
      (node (ref "U19") (pin "1") (pinfunction "RSV_1") (pintype "passive"))
    )
    (net (code "598") (name "unconnected-(U19-RSV-Pad2)") (class "Default")
      (node (ref "U19") (pin "2") (pinfunction "RSV_2") (pintype "passive"))
    )
    (net (code "599") (name "unconnected-(U19-RSV-Pad3)") (class "Default")
      (node (ref "U19") (pin "3") (pinfunction "RSV_3") (pintype "passive"))
    )
    (net (code "600") (name "unconnected-(U19-RSV-Pad4)") (class "Default")
      (node (ref "U19") (pin "4") (pinfunction "RSV_4") (pintype "passive"))
    )
    (net (code "601") (name "unconnected-(U19-RSV-Pad5)") (class "Default")
      (node (ref "U19") (pin "5") (pinfunction "RSV_5") (pintype "passive"))
    )
    (net (code "602") (name "unconnected-(U19-RSV-Pad6)") (class "Default")
      (node (ref "U19") (pin "6") (pinfunction "RSV_6") (pintype "passive"))
    )
    (net (code "603") (name "unconnected-(U19-RSV-Pad7)") (class "Default")
      (node (ref "U19") (pin "7") (pinfunction "RSV_7") (pintype "passive"))
    )
    (net (code "604") (name "unconnected-(U19-RSV-Pad14)") (class "Default")
      (node (ref "U19") (pin "14") (pinfunction "RSV_14") (pintype "passive"))
    )
    (net (code "605") (name "unconnected-(U19-RSV-Pad15)") (class "Default")
      (node (ref "U19") (pin "15") (pinfunction "RSV_15") (pintype "passive"))
    )
    (net (code "606") (name "unconnected-(U19-RSV-Pad16)") (class "Default")
      (node (ref "U19") (pin "16") (pinfunction "RSV_16") (pintype "passive"))
    )
    (net (code "607") (name "unconnected-(U19-RSV-Pad17)") (class "Default")
      (node (ref "U19") (pin "17") (pinfunction "RSV_17") (pintype "passive"))
    )
    (net (code "608") (name "unconnected-(U20-I2CSCL-Pad19)") (class "Default")
      (node (ref "U20") (pin "19") (pinfunction "I2CSCL_19") (pintype "passive"))
    )
    (net (code "609") (name "unconnected-(U20-I2CSDA-Pad18)") (class "Default")
      (node (ref "U20") (pin "18") (pinfunction "I2CSDA_18") (pintype "passive"))
    )
    (net (code "610") (name "unconnected-(U20-RSV-Pad1)") (class "Default")
      (node (ref "U20") (pin "1") (pinfunction "RSV_1") (pintype "passive"))
    )
    (net (code "611") (name "unconnected-(U20-RSV-Pad2)") (class "Default")
      (node (ref "U20") (pin "2") (pinfunction "RSV_2") (pintype "passive"))
    )
    (net (code "612") (name "unconnected-(U20-RSV-Pad3)") (class "Default")
      (node (ref "U20") (pin "3") (pinfunction "RSV_3") (pintype "passive"))
    )
    (net (code "613") (name "unconnected-(U20-RSV-Pad4)") (class "Default")
      (node (ref "U20") (pin "4") (pinfunction "RSV_4") (pintype "passive"))
    )
    (net (code "614") (name "unconnected-(U20-RSV-Pad5)") (class "Default")
      (node (ref "U20") (pin "5") (pinfunction "RSV_5") (pintype "passive"))
    )
    (net (code "615") (name "unconnected-(U20-RSV-Pad6)") (class "Default")
      (node (ref "U20") (pin "6") (pinfunction "RSV_6") (pintype "passive"))
    )
    (net (code "616") (name "unconnected-(U20-RSV-Pad7)") (class "Default")
      (node (ref "U20") (pin "7") (pinfunction "RSV_7") (pintype "passive"))
    )
    (net (code "617") (name "unconnected-(U20-RSV-Pad14)") (class "Default")
      (node (ref "U20") (pin "14") (pinfunction "RSV_14") (pintype "passive"))
    )
    (net (code "618") (name "unconnected-(U20-RSV-Pad15)") (class "Default")
      (node (ref "U20") (pin "15") (pinfunction "RSV_15") (pintype "passive"))
    )
    (net (code "619") (name "unconnected-(U20-RSV-Pad16)") (class "Default")
      (node (ref "U20") (pin "16") (pinfunction "RSV_16") (pintype "passive"))
    )
    (net (code "620") (name "unconnected-(U20-RSV-Pad17)") (class "Default")
      (node (ref "U20") (pin "17") (pinfunction "RSV_17") (pintype "passive"))
    )
    (net (code "621") (name "unconnected-(U21-I2CSCL-Pad19)") (class "Default")
      (node (ref "U21") (pin "19") (pinfunction "I2CSCL_19") (pintype "passive"))
    )
    (net (code "622") (name "unconnected-(U21-I2CSDA-Pad18)") (class "Default")
      (node (ref "U21") (pin "18") (pinfunction "I2CSDA_18") (pintype "passive"))
    )
    (net (code "623") (name "unconnected-(U21-RSV-Pad1)") (class "Default")
      (node (ref "U21") (pin "1") (pinfunction "RSV_1") (pintype "passive"))
    )
    (net (code "624") (name "unconnected-(U21-RSV-Pad2)") (class "Default")
      (node (ref "U21") (pin "2") (pinfunction "RSV_2") (pintype "passive"))
    )
    (net (code "625") (name "unconnected-(U21-RSV-Pad3)") (class "Default")
      (node (ref "U21") (pin "3") (pinfunction "RSV_3") (pintype "passive"))
    )
    (net (code "626") (name "unconnected-(U21-RSV-Pad4)") (class "Default")
      (node (ref "U21") (pin "4") (pinfunction "RSV_4") (pintype "passive"))
    )
    (net (code "627") (name "unconnected-(U21-RSV-Pad5)") (class "Default")
      (node (ref "U21") (pin "5") (pinfunction "RSV_5") (pintype "passive"))
    )
    (net (code "628") (name "unconnected-(U21-RSV-Pad6)") (class "Default")
      (node (ref "U21") (pin "6") (pinfunction "RSV_6") (pintype "passive"))
    )
    (net (code "629") (name "unconnected-(U21-RSV-Pad7)") (class "Default")
      (node (ref "U21") (pin "7") (pinfunction "RSV_7") (pintype "passive"))
    )
    (net (code "630") (name "unconnected-(U21-RSV-Pad14)") (class "Default")
      (node (ref "U21") (pin "14") (pinfunction "RSV_14") (pintype "passive"))
    )
    (net (code "631") (name "unconnected-(U21-RSV-Pad15)") (class "Default")
      (node (ref "U21") (pin "15") (pinfunction "RSV_15") (pintype "passive"))
    )
    (net (code "632") (name "unconnected-(U21-RSV-Pad16)") (class "Default")
      (node (ref "U21") (pin "16") (pinfunction "RSV_16") (pintype "passive"))
    )
    (net (code "633") (name "unconnected-(U21-RSV-Pad17)") (class "Default")
      (node (ref "U21") (pin "17") (pinfunction "RSV_17") (pintype "passive"))
    )
    (net (code "634") (name "unconnected-(U22-I2CSCL-Pad19)") (class "Default")
      (node (ref "U22") (pin "19") (pinfunction "I2CSCL_19") (pintype "passive"))
    )
    (net (code "635") (name "unconnected-(U22-I2CSDA-Pad18)") (class "Default")
      (node (ref "U22") (pin "18") (pinfunction "I2CSDA_18") (pintype "passive"))
    )
    (net (code "636") (name "unconnected-(U22-RSV-Pad1)") (class "Default")
      (node (ref "U22") (pin "1") (pinfunction "RSV_1") (pintype "passive"))
    )
    (net (code "637") (name "unconnected-(U22-RSV-Pad2)") (class "Default")
      (node (ref "U22") (pin "2") (pinfunction "RSV_2") (pintype "passive"))
    )
    (net (code "638") (name "unconnected-(U22-RSV-Pad3)") (class "Default")
      (node (ref "U22") (pin "3") (pinfunction "RSV_3") (pintype "passive"))
    )
    (net (code "639") (name "unconnected-(U22-RSV-Pad4)") (class "Default")
      (node (ref "U22") (pin "4") (pinfunction "RSV_4") (pintype "passive"))
    )
    (net (code "640") (name "unconnected-(U22-RSV-Pad5)") (class "Default")
      (node (ref "U22") (pin "5") (pinfunction "RSV_5") (pintype "passive"))
    )
    (net (code "641") (name "unconnected-(U22-RSV-Pad6)") (class "Default")
      (node (ref "U22") (pin "6") (pinfunction "RSV_6") (pintype "passive"))
    )
    (net (code "642") (name "unconnected-(U22-RSV-Pad7)") (class "Default")
      (node (ref "U22") (pin "7") (pinfunction "RSV_7") (pintype "passive"))
    )
    (net (code "643") (name "unconnected-(U22-RSV-Pad14)") (class "Default")
      (node (ref "U22") (pin "14") (pinfunction "RSV_14") (pintype "passive"))
    )
    (net (code "644") (name "unconnected-(U22-RSV-Pad15)") (class "Default")
      (node (ref "U22") (pin "15") (pinfunction "RSV_15") (pintype "passive"))
    )
    (net (code "645") (name "unconnected-(U22-RSV-Pad16)") (class "Default")
      (node (ref "U22") (pin "16") (pinfunction "RSV_16") (pintype "passive"))
    )
    (net (code "646") (name "unconnected-(U22-RSV-Pad17)") (class "Default")
      (node (ref "U22") (pin "17") (pinfunction "RSV_17") (pintype "passive"))
    )
    (net (code "647") (name "unconnected-(U23-I2CSCL-Pad19)") (class "Default")
      (node (ref "U23") (pin "19") (pinfunction "I2CSCL_19") (pintype "passive"))
    )
    (net (code "648") (name "unconnected-(U23-I2CSDA-Pad18)") (class "Default")
      (node (ref "U23") (pin "18") (pinfunction "I2CSDA_18") (pintype "passive"))
    )
    (net (code "649") (name "unconnected-(U23-RSV-Pad1)") (class "Default")
      (node (ref "U23") (pin "1") (pinfunction "RSV_1") (pintype "passive"))
    )
    (net (code "650") (name "unconnected-(U23-RSV-Pad2)") (class "Default")
      (node (ref "U23") (pin "2") (pinfunction "RSV_2") (pintype "passive"))
    )
    (net (code "651") (name "unconnected-(U23-RSV-Pad3)") (class "Default")
      (node (ref "U23") (pin "3") (pinfunction "RSV_3") (pintype "passive"))
    )
    (net (code "652") (name "unconnected-(U23-RSV-Pad4)") (class "Default")
      (node (ref "U23") (pin "4") (pinfunction "RSV_4") (pintype "passive"))
    )
    (net (code "653") (name "unconnected-(U23-RSV-Pad5)") (class "Default")
      (node (ref "U23") (pin "5") (pinfunction "RSV_5") (pintype "passive"))
    )
    (net (code "654") (name "unconnected-(U23-RSV-Pad6)") (class "Default")
      (node (ref "U23") (pin "6") (pinfunction "RSV_6") (pintype "passive"))
    )
    (net (code "655") (name "unconnected-(U23-RSV-Pad7)") (class "Default")
      (node (ref "U23") (pin "7") (pinfunction "RSV_7") (pintype "passive"))
    )
    (net (code "656") (name "unconnected-(U23-RSV-Pad14)") (class "Default")
      (node (ref "U23") (pin "14") (pinfunction "RSV_14") (pintype "passive"))
    )
    (net (code "657") (name "unconnected-(U23-RSV-Pad15)") (class "Default")
      (node (ref "U23") (pin "15") (pinfunction "RSV_15") (pintype "passive"))
    )
    (net (code "658") (name "unconnected-(U23-RSV-Pad16)") (class "Default")
      (node (ref "U23") (pin "16") (pinfunction "RSV_16") (pintype "passive"))
    )
    (net (code "659") (name "unconnected-(U23-RSV-Pad17)") (class "Default")
      (node (ref "U23") (pin "17") (pinfunction "RSV_17") (pintype "passive"))
    )
    (net (code "660") (name "unconnected-(U24-I2CSCL-Pad19)") (class "Default")
      (node (ref "U24") (pin "19") (pinfunction "I2CSCL_19") (pintype "passive"))
    )
    (net (code "661") (name "unconnected-(U24-I2CSDA-Pad18)") (class "Default")
      (node (ref "U24") (pin "18") (pinfunction "I2CSDA_18") (pintype "passive"))
    )
    (net (code "662") (name "unconnected-(U24-RSV-Pad1)") (class "Default")
      (node (ref "U24") (pin "1") (pinfunction "RSV_1") (pintype "passive"))
    )
    (net (code "663") (name "unconnected-(U24-RSV-Pad2)") (class "Default")
      (node (ref "U24") (pin "2") (pinfunction "RSV_2") (pintype "passive"))
    )
    (net (code "664") (name "unconnected-(U24-RSV-Pad3)") (class "Default")
      (node (ref "U24") (pin "3") (pinfunction "RSV_3") (pintype "passive"))
    )
    (net (code "665") (name "unconnected-(U24-RSV-Pad4)") (class "Default")
      (node (ref "U24") (pin "4") (pinfunction "RSV_4") (pintype "passive"))
    )
    (net (code "666") (name "unconnected-(U24-RSV-Pad5)") (class "Default")
      (node (ref "U24") (pin "5") (pinfunction "RSV_5") (pintype "passive"))
    )
    (net (code "667") (name "unconnected-(U24-RSV-Pad6)") (class "Default")
      (node (ref "U24") (pin "6") (pinfunction "RSV_6") (pintype "passive"))
    )
    (net (code "668") (name "unconnected-(U24-RSV-Pad7)") (class "Default")
      (node (ref "U24") (pin "7") (pinfunction "RSV_7") (pintype "passive"))
    )
    (net (code "669") (name "unconnected-(U24-RSV-Pad14)") (class "Default")
      (node (ref "U24") (pin "14") (pinfunction "RSV_14") (pintype "passive"))
    )
    (net (code "670") (name "unconnected-(U24-RSV-Pad15)") (class "Default")
      (node (ref "U24") (pin "15") (pinfunction "RSV_15") (pintype "passive"))
    )
    (net (code "671") (name "unconnected-(U24-RSV-Pad16)") (class "Default")
      (node (ref "U24") (pin "16") (pinfunction "RSV_16") (pintype "passive"))
    )
    (net (code "672") (name "unconnected-(U24-RSV-Pad17)") (class "Default")
      (node (ref "U24") (pin "17") (pinfunction "RSV_17") (pintype "passive"))
    )
  )
)
